# PDB_Mother_v1_1_Sheet.net
KiCad netlist of a schematic drawn in Altium Designer
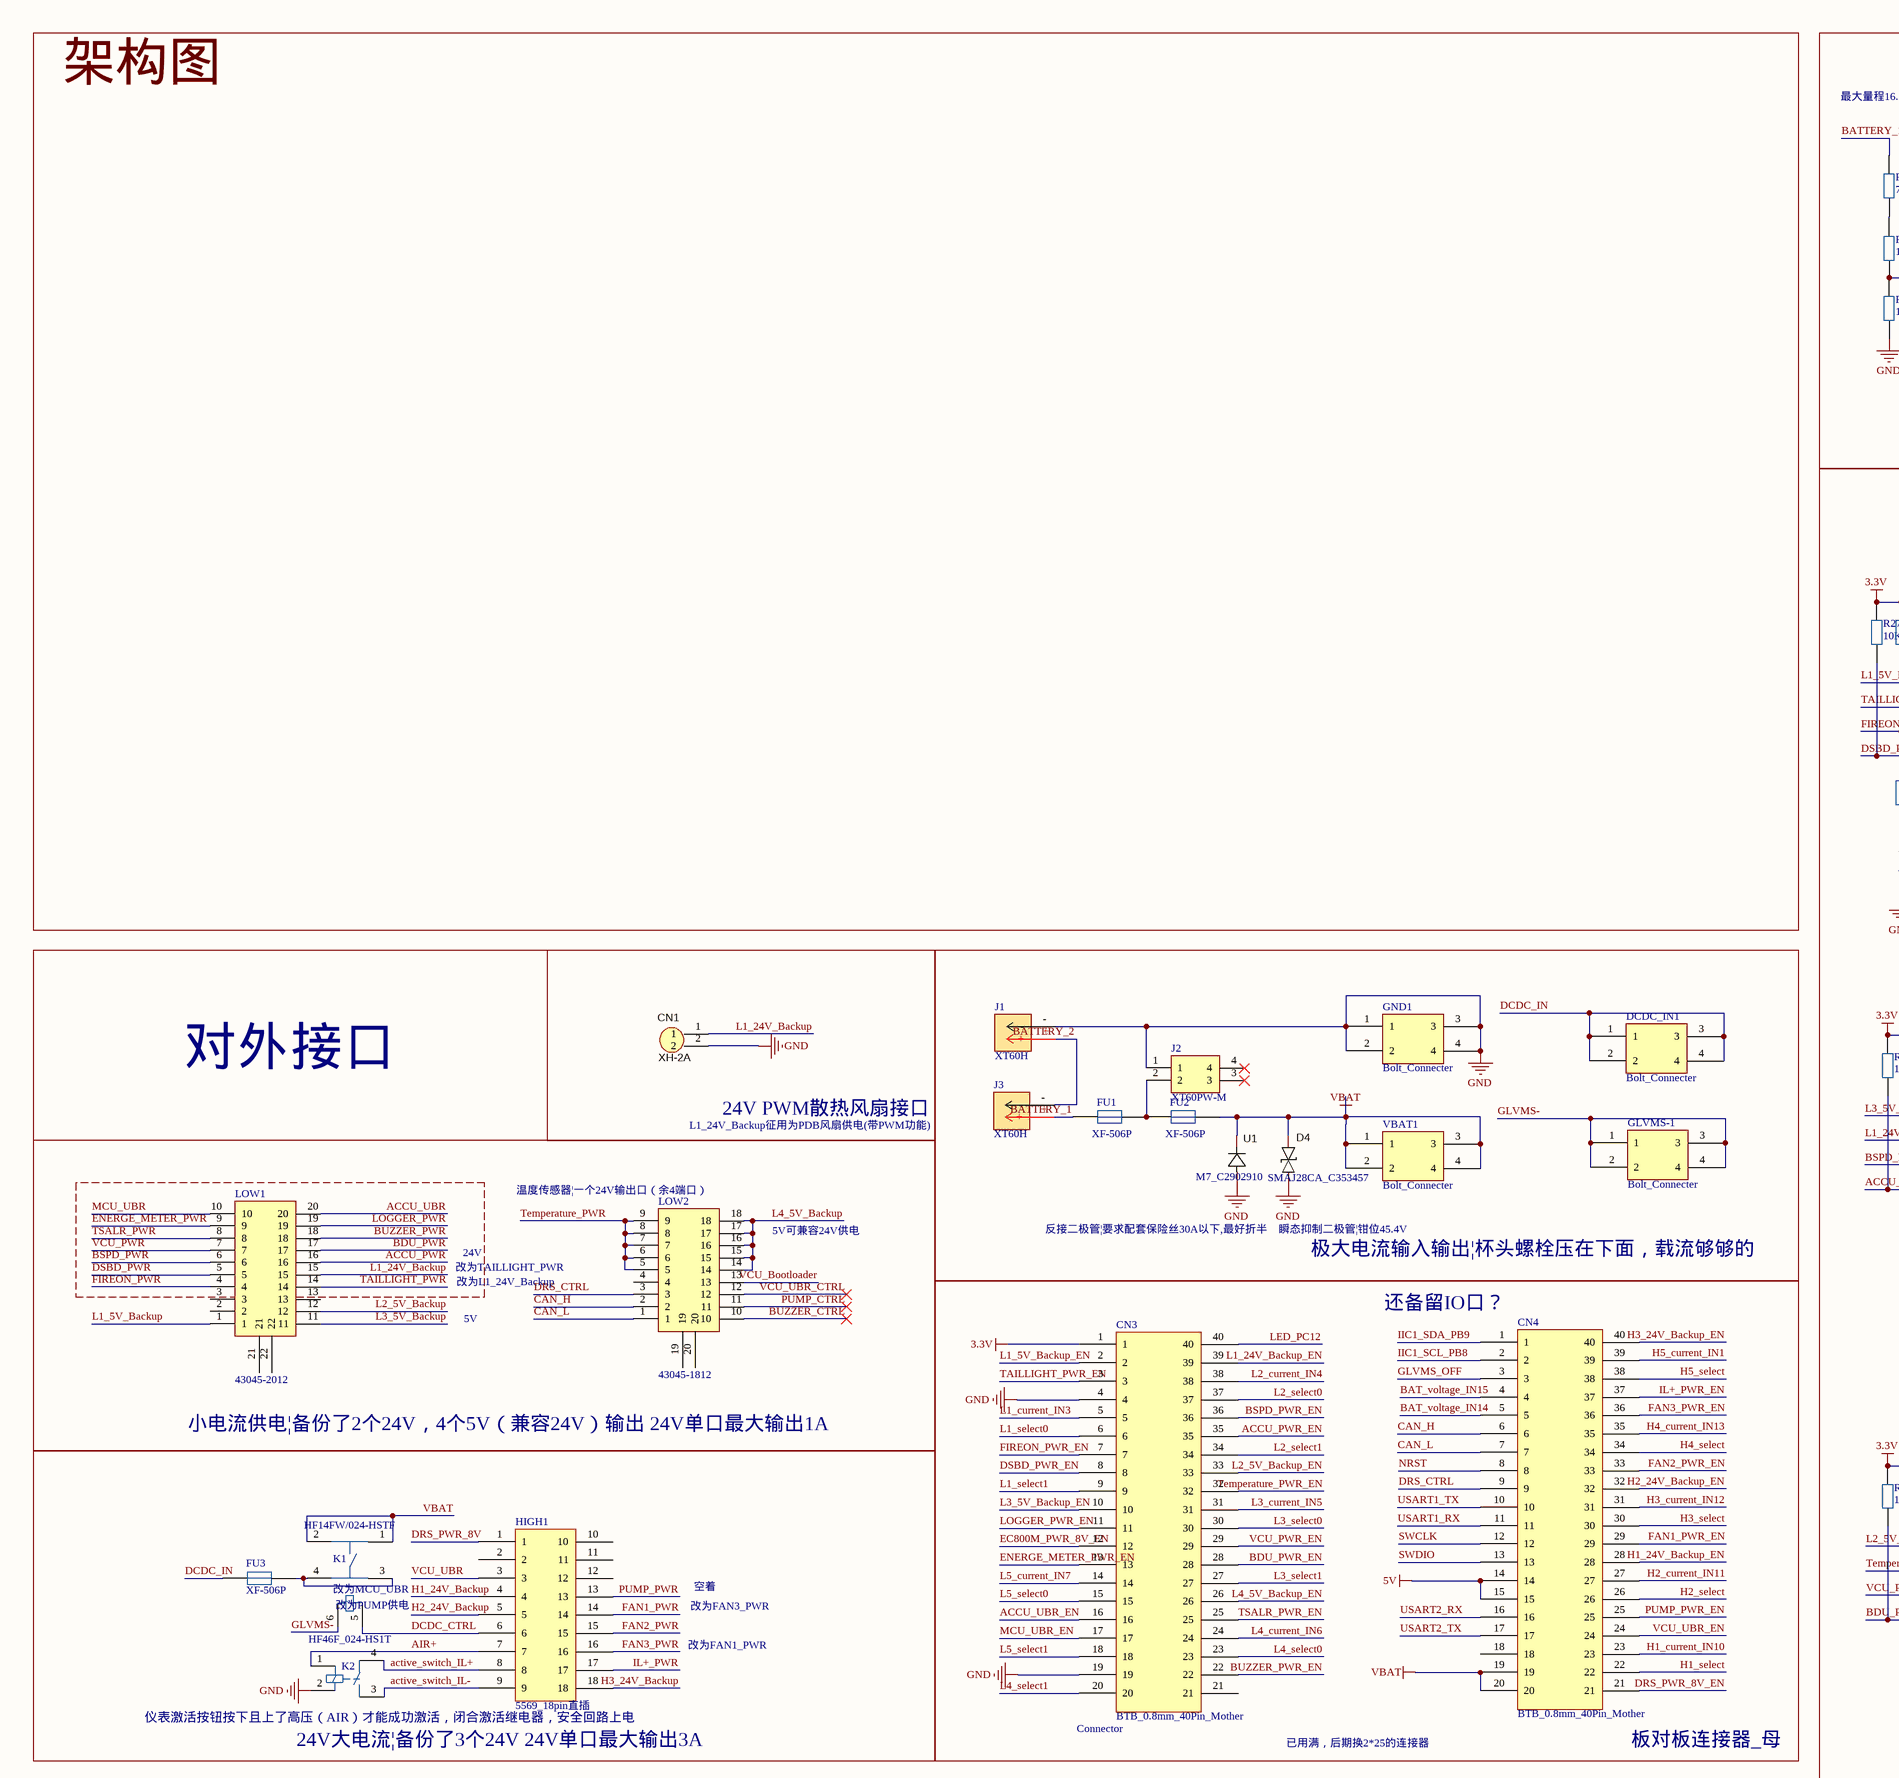
[diagram p0: PDB_Mother_v1.1_Sheet.SchDoc, top left]
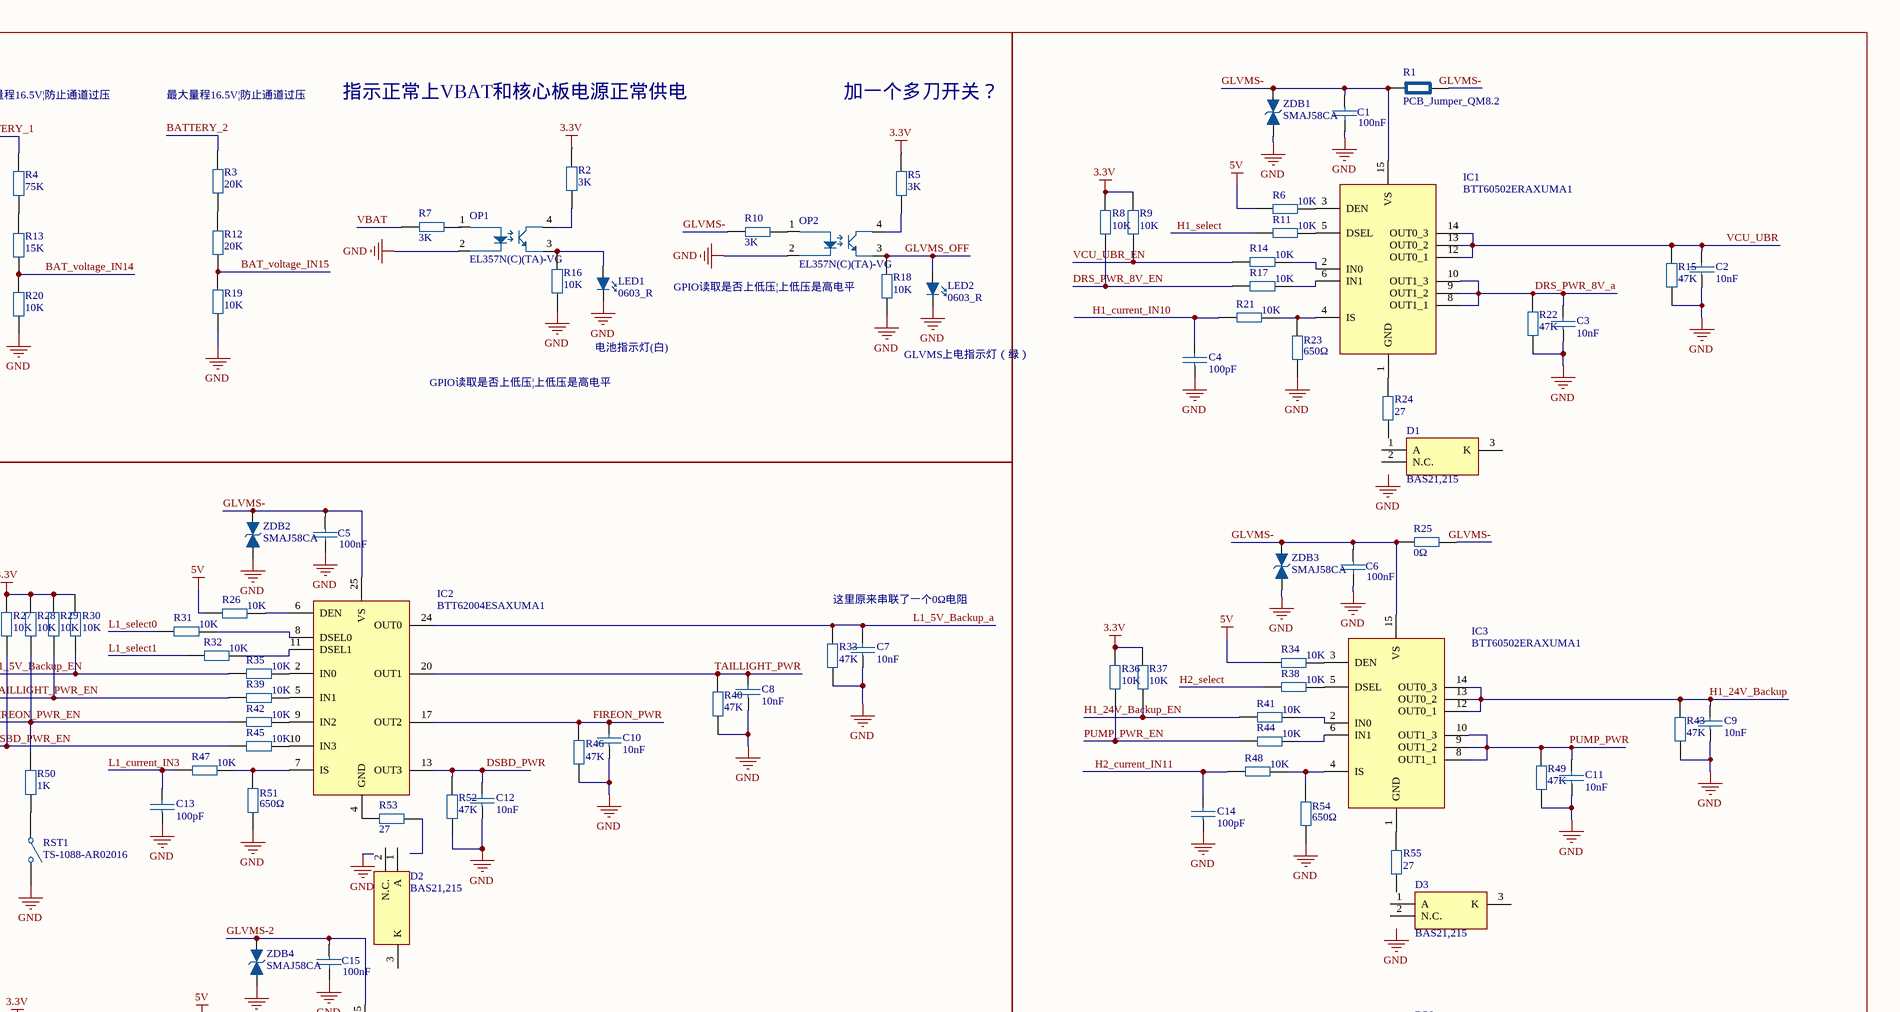
[diagram p1: PDB_Mother_v1.1_Sheet.SchDoc, top right]
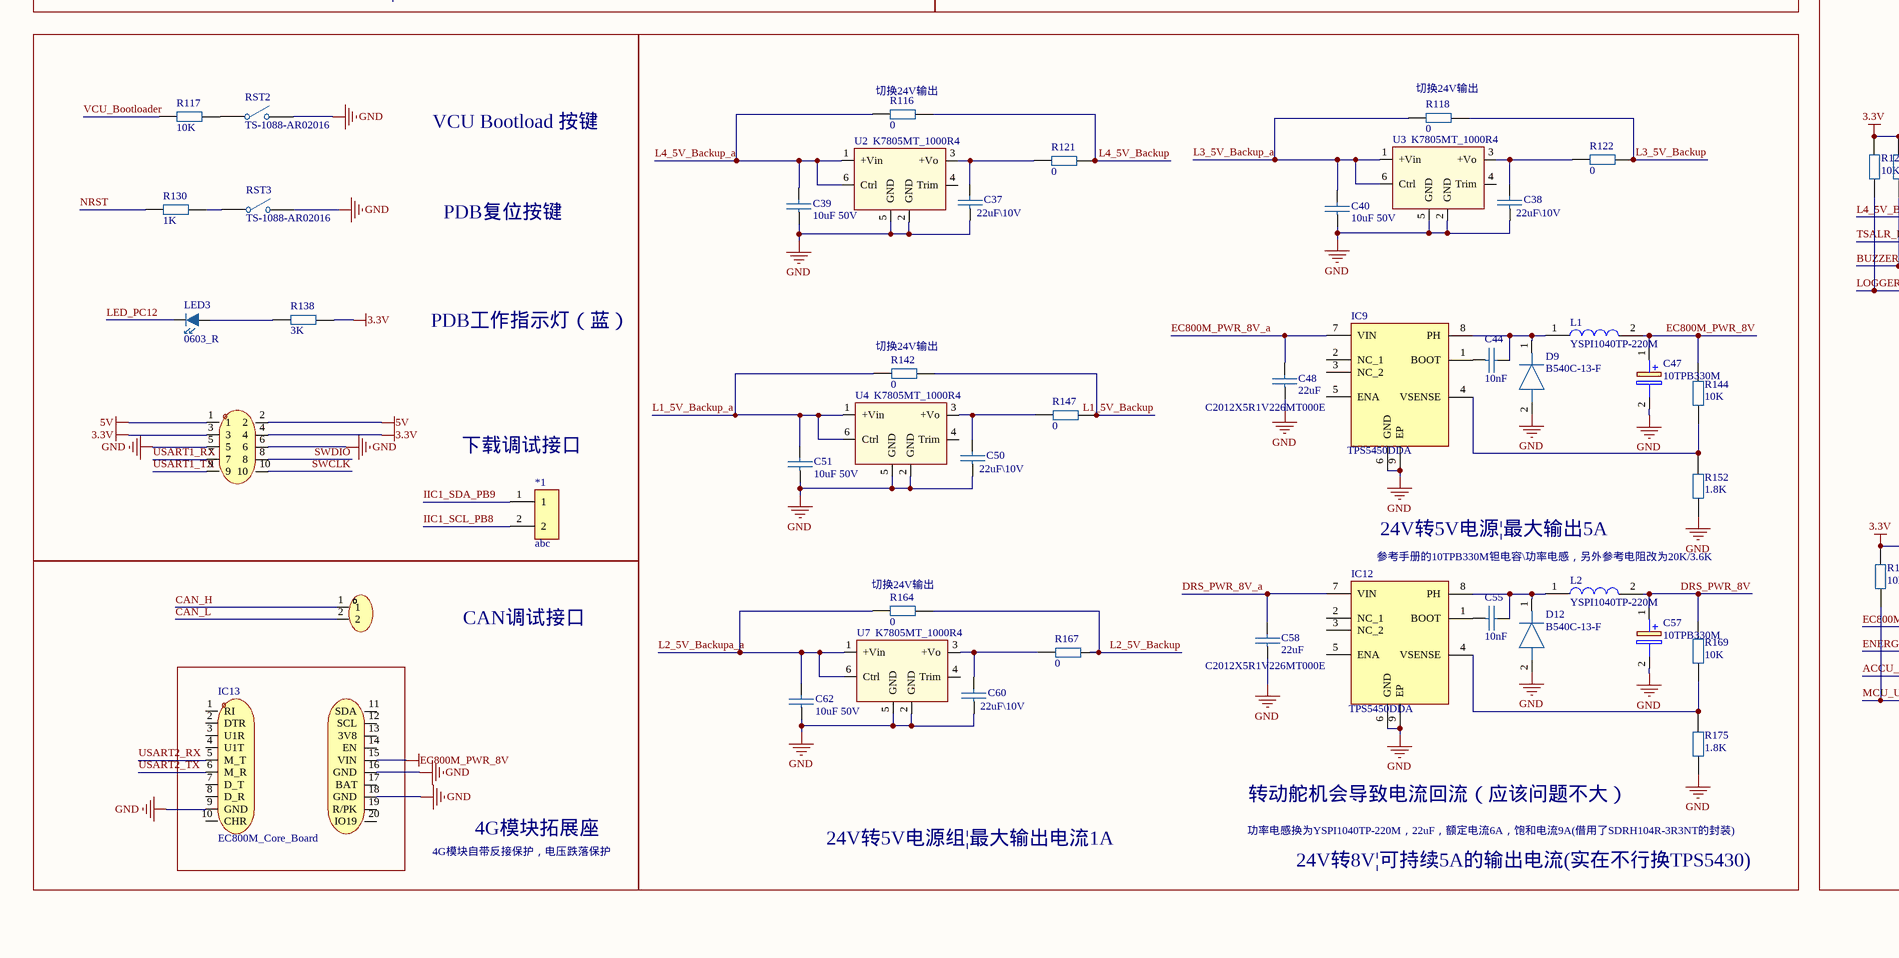
[diagram p2: PDB_Mother_v1.1_Sheet.SchDoc, bottom left]
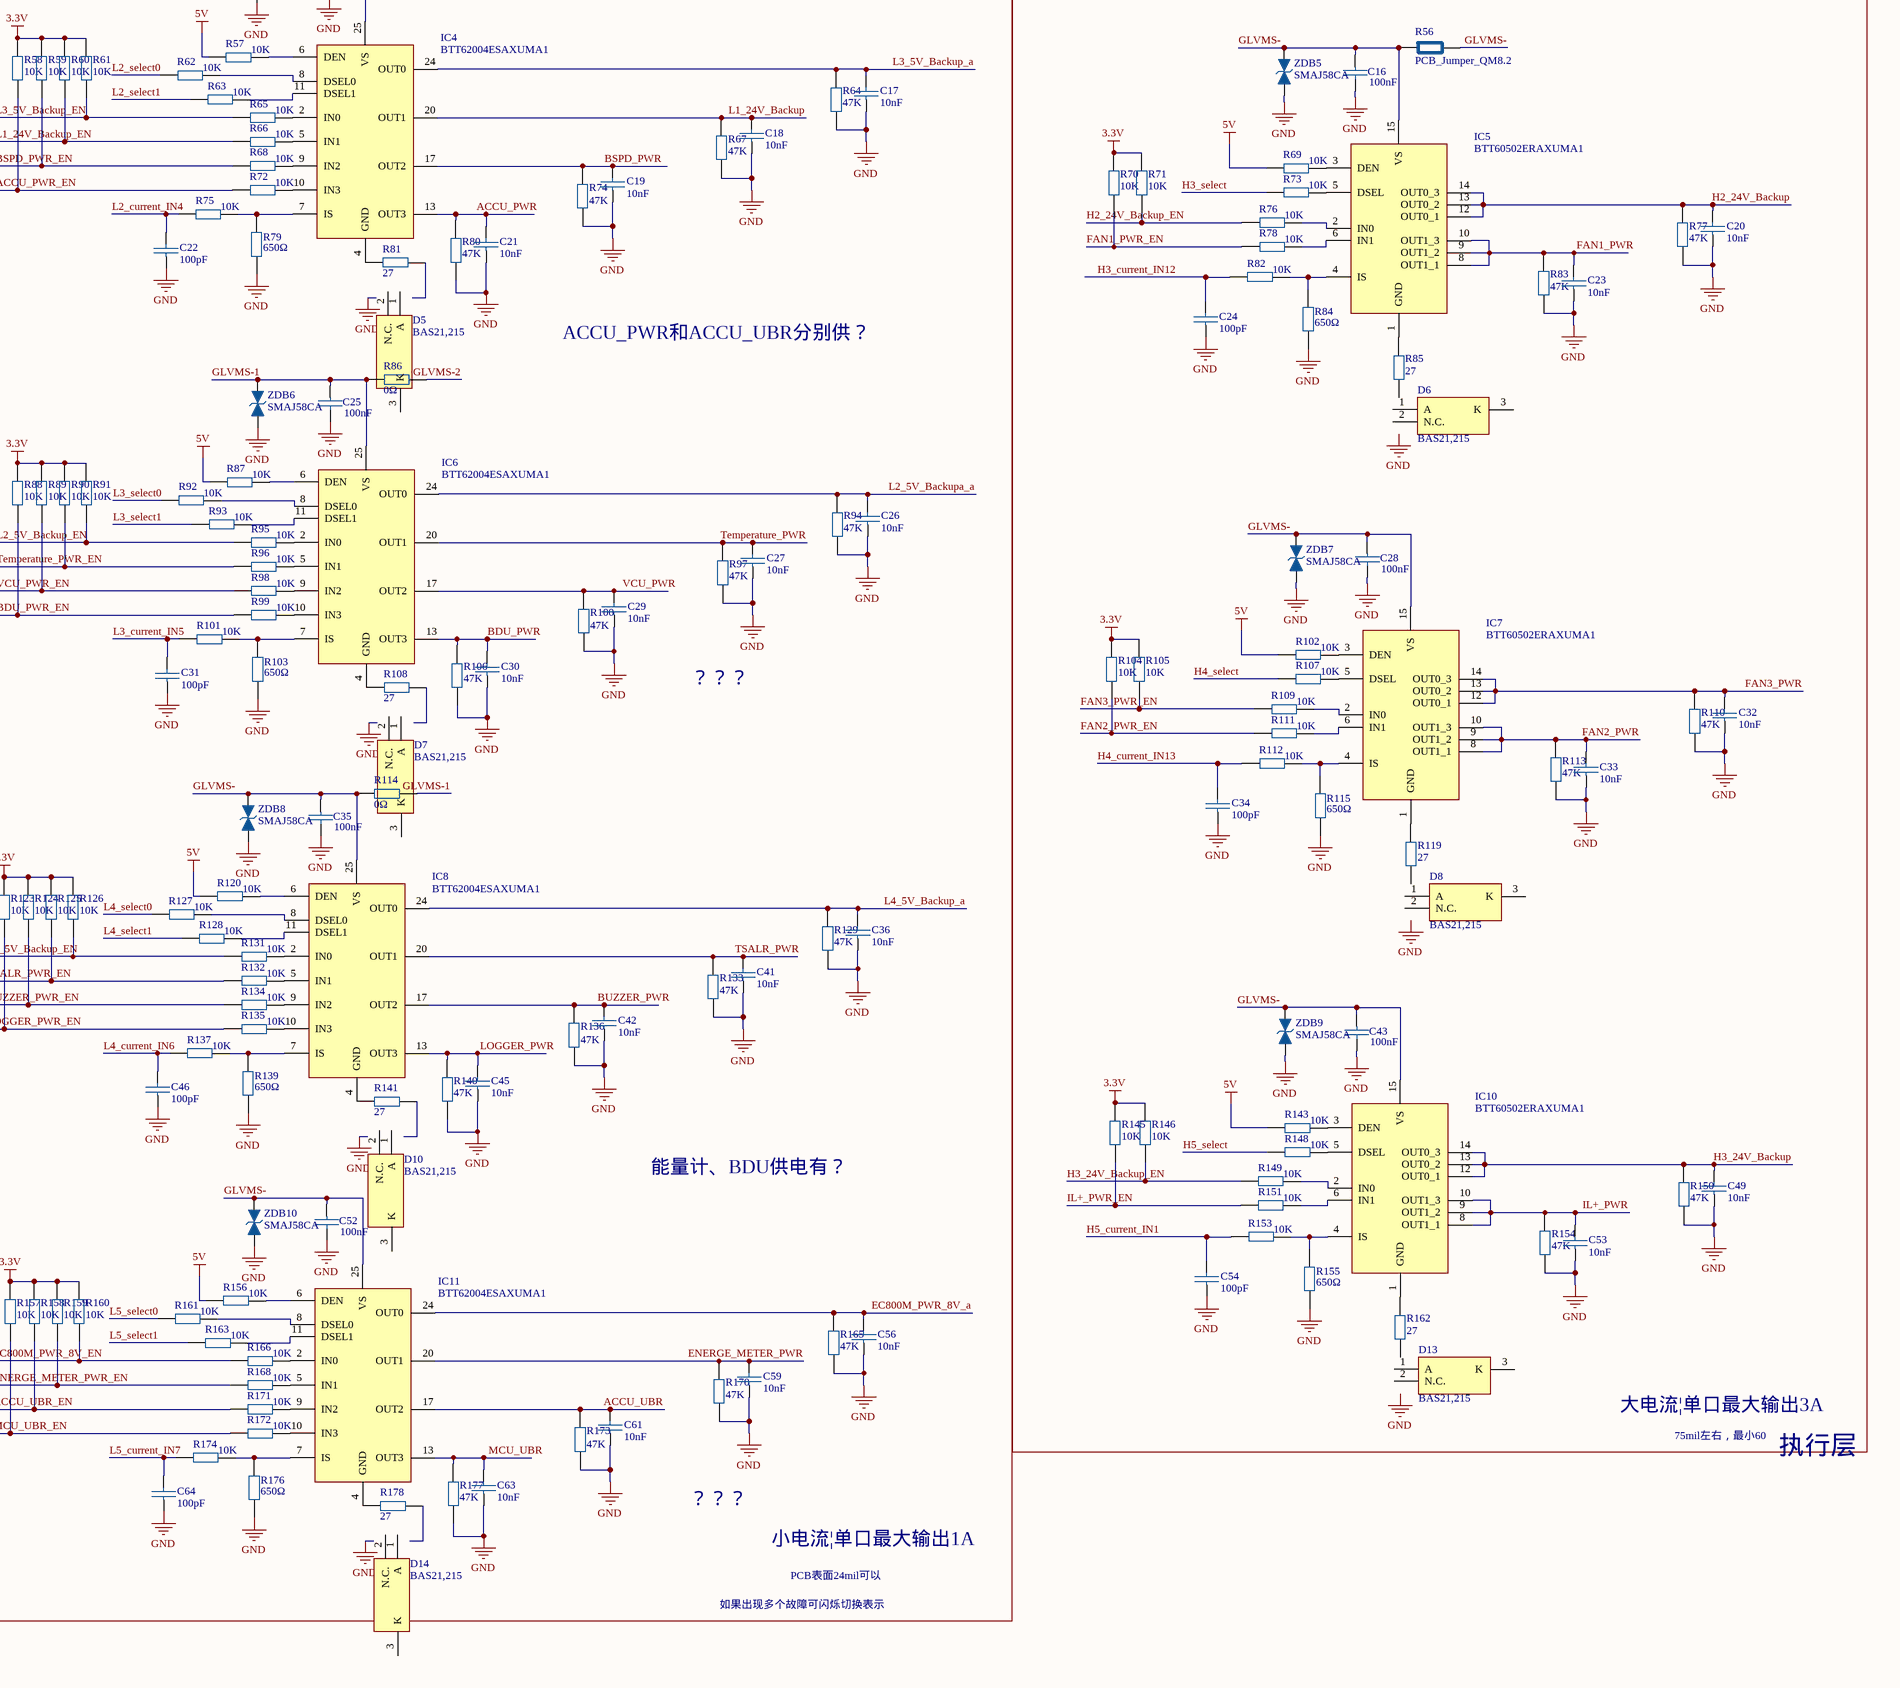
[diagram p3: PDB_Mother_v1.1_Sheet.SchDoc, bottom right]

(export (version "E")
  (design (tool "Eeschema 10.0.6"))
  (components
    (comp (ref "*1") (value "abc") (footprint "abc") (libsource (lib "Connector") (part "abc")))
    (comp (ref "C1")
      (value "100nF")
      (footprint "CAPC1608X08N__0603CAPUNPOLE")
      (description "Std MLCC Cap")
      (libsource (lib "ResistorCapacitorInductor") (part "SMD_MLCC"))
    )
    (comp (ref "C2")
      (value "10nF")
      (footprint "CAPC1608X08N__0603CAPUNPOLE")
      (description "Std MLCC Cap")
      (libsource (lib "ResistorCapacitorInductor") (part "SMD_MLCC"))
    )
    (comp (ref "C3")
      (value "10nF")
      (footprint "CAPC1608X08N__0603CAPUNPOLE")
      (description "Std MLCC Cap")
      (libsource (lib "ResistorCapacitorInductor") (part "SMD_MLCC"))
    )
    (comp (ref "C4")
      (value "100pF")
      (footprint "CAPC1608X08N__0603CAPUNPOLE")
      (description "Std MLCC Cap")
      (libsource (lib "ResistorCapacitorInductor") (part "SMD_MLCC"))
    )
    (comp (ref "C5")
      (value "100nF")
      (footprint "CAPC1608X08N__0603CAPUNPOLE")
      (description "Std MLCC Cap")
      (libsource (lib "ResistorCapacitorInductor") (part "SMD_MLCC"))
    )
    (comp (ref "C6")
      (value "100nF")
      (footprint "CAPC1608X08N__0603CAPUNPOLE")
      (description "Std MLCC Cap")
      (libsource (lib "ResistorCapacitorInductor") (part "SMD_MLCC"))
    )
    (comp (ref "C7")
      (value "10nF")
      (footprint "CAPC1608X08N__0603CAPUNPOLE")
      (description "Std MLCC Cap")
      (libsource (lib "ResistorCapacitorInductor") (part "SMD_MLCC"))
    )
    (comp (ref "C8")
      (value "10nF")
      (footprint "CAPC1608X08N__0603CAPUNPOLE")
      (description "Std MLCC Cap")
      (libsource (lib "ResistorCapacitorInductor") (part "SMD_MLCC"))
    )
    (comp (ref "C9")
      (value "10nF")
      (footprint "CAPC1608X08N__0603CAPUNPOLE")
      (description "Std MLCC Cap")
      (libsource (lib "ResistorCapacitorInductor") (part "SMD_MLCC"))
    )
    (comp (ref "C10")
      (value "10nF")
      (footprint "CAPC1608X08N__0603CAPUNPOLE")
      (description "Std MLCC Cap")
      (libsource (lib "ResistorCapacitorInductor") (part "SMD_MLCC"))
    )
    (comp (ref "C11")
      (value "10nF")
      (footprint "CAPC1608X08N__0603CAPUNPOLE")
      (description "Std MLCC Cap")
      (libsource (lib "ResistorCapacitorInductor") (part "SMD_MLCC"))
    )
    (comp (ref "C12")
      (value "10nF")
      (footprint "CAPC1608X08N__0603CAPUNPOLE")
      (description "Std MLCC Cap")
      (libsource (lib "ResistorCapacitorInductor") (part "SMD_MLCC"))
    )
    (comp (ref "C13")
      (value "100pF")
      (footprint "CAPC1608X08N__0603CAPUNPOLE")
      (description "Std MLCC Cap")
      (libsource (lib "ResistorCapacitorInductor") (part "SMD_MLCC"))
    )
    (comp (ref "C14")
      (value "100pF")
      (footprint "CAPC1608X08N__0603CAPUNPOLE")
      (description "Std MLCC Cap")
      (libsource (lib "ResistorCapacitorInductor") (part "SMD_MLCC"))
    )
    (comp (ref "C15")
      (value "100nF")
      (footprint "CAPC1608X08N__0603CAPUNPOLE")
      (description "Std MLCC Cap")
      (libsource (lib "ResistorCapacitorInductor") (part "SMD_MLCC"))
    )
    (comp (ref "C16")
      (value "100nF")
      (footprint "CAPC1608X08N__0603CAPUNPOLE")
      (description "Std MLCC Cap")
      (libsource (lib "ResistorCapacitorInductor") (part "SMD_MLCC"))
    )
    (comp (ref "C17")
      (value "10nF")
      (footprint "CAPC1608X08N__0603CAPUNPOLE")
      (description "Std MLCC Cap")
      (libsource (lib "ResistorCapacitorInductor") (part "SMD_MLCC"))
    )
    (comp (ref "C18")
      (value "10nF")
      (footprint "CAPC1608X08N__0603CAPUNPOLE")
      (description "Std MLCC Cap")
      (libsource (lib "ResistorCapacitorInductor") (part "SMD_MLCC"))
    )
    (comp (ref "C19")
      (value "10nF")
      (footprint "CAPC1608X08N__0603CAPUNPOLE")
      (description "Std MLCC Cap")
      (libsource (lib "ResistorCapacitorInductor") (part "SMD_MLCC"))
    )
    (comp (ref "C20")
      (value "10nF")
      (footprint "CAPC1608X08N__0603CAPUNPOLE")
      (description "Std MLCC Cap")
      (libsource (lib "ResistorCapacitorInductor") (part "SMD_MLCC"))
    )
    (comp (ref "C21")
      (value "10nF")
      (footprint "CAPC1608X08N__0603CAPUNPOLE")
      (description "Std MLCC Cap")
      (libsource (lib "ResistorCapacitorInductor") (part "SMD_MLCC"))
    )
    (comp (ref "C22")
      (value "100pF")
      (footprint "CAPC1608X08N__0603CAPUNPOLE")
      (description "Std MLCC Cap")
      (libsource (lib "ResistorCapacitorInductor") (part "SMD_MLCC"))
    )
    (comp (ref "C23")
      (value "10nF")
      (footprint "CAPC1608X08N__0603CAPUNPOLE")
      (description "Std MLCC Cap")
      (libsource (lib "ResistorCapacitorInductor") (part "SMD_MLCC"))
    )
    (comp (ref "C24")
      (value "100pF")
      (footprint "CAPC1608X08N__0603CAPUNPOLE")
      (description "Std MLCC Cap")
      (libsource (lib "ResistorCapacitorInductor") (part "SMD_MLCC"))
    )
    (comp (ref "C25")
      (value "100nF")
      (footprint "CAPC1608X08N__0603CAPUNPOLE")
      (description "Std MLCC Cap")
      (libsource (lib "ResistorCapacitorInductor") (part "SMD_MLCC"))
    )
    (comp (ref "C26")
      (value "10nF")
      (footprint "CAPC1608X08N__0603CAPUNPOLE")
      (description "Std MLCC Cap")
      (libsource (lib "ResistorCapacitorInductor") (part "SMD_MLCC"))
    )
    (comp (ref "C27")
      (value "10nF")
      (footprint "CAPC1608X08N__0603CAPUNPOLE")
      (description "Std MLCC Cap")
      (libsource (lib "ResistorCapacitorInductor") (part "SMD_MLCC"))
    )
    (comp (ref "C28")
      (value "100nF")
      (footprint "CAPC1608X08N__0603CAPUNPOLE")
      (description "Std MLCC Cap")
      (libsource (lib "ResistorCapacitorInductor") (part "SMD_MLCC"))
    )
    (comp (ref "C29")
      (value "10nF")
      (footprint "CAPC1608X08N__0603CAPUNPOLE")
      (description "Std MLCC Cap")
      (libsource (lib "ResistorCapacitorInductor") (part "SMD_MLCC"))
    )
    (comp (ref "C30")
      (value "10nF")
      (footprint "CAPC1608X08N__0603CAPUNPOLE")
      (description "Std MLCC Cap")
      (libsource (lib "ResistorCapacitorInductor") (part "SMD_MLCC"))
    )
    (comp (ref "C31")
      (value "100pF")
      (footprint "CAPC1608X08N__0603CAPUNPOLE")
      (description "Std MLCC Cap")
      (libsource (lib "ResistorCapacitorInductor") (part "SMD_MLCC"))
    )
    (comp (ref "C32")
      (value "10nF")
      (footprint "CAPC1608X08N__0603CAPUNPOLE")
      (description "Std MLCC Cap")
      (libsource (lib "ResistorCapacitorInductor") (part "SMD_MLCC"))
    )
    (comp (ref "C33")
      (value "10nF")
      (footprint "CAPC1608X08N__0603CAPUNPOLE")
      (description "Std MLCC Cap")
      (libsource (lib "ResistorCapacitorInductor") (part "SMD_MLCC"))
    )
    (comp (ref "C34")
      (value "100pF")
      (footprint "CAPC1608X08N__0603CAPUNPOLE")
      (description "Std MLCC Cap")
      (libsource (lib "ResistorCapacitorInductor") (part "SMD_MLCC"))
    )
    (comp (ref "C35")
      (value "100nF")
      (footprint "CAPC1608X08N__0603CAPUNPOLE")
      (description "Std MLCC Cap")
      (libsource (lib "ResistorCapacitorInductor") (part "SMD_MLCC"))
    )
    (comp (ref "C36")
      (value "10nF")
      (footprint "CAPC1608X08N__0603CAPUNPOLE")
      (description "Std MLCC Cap")
      (libsource (lib "ResistorCapacitorInductor") (part "SMD_MLCC"))
    )
    (comp (ref "C37")
      (value "22u~{F}10V")
      (footprint "CAPC1608X08N__0603CAPUNPOLE")
      (description "Std MLCC Cap")
      (libsource (lib "ResistorCapacitorInductor") (part "SMD_MLCC"))
    )
    (comp (ref "C38")
      (value "22u~{F}10V")
      (footprint "CAPC1608X08N__0603CAPUNPOLE")
      (description "Std MLCC Cap")
      (libsource (lib "ResistorCapacitorInductor") (part "SMD_MLCC"))
    )
    (comp (ref "C39")
      (value "10uF 50V")
      (footprint "CAPC3216X16N_1206CAPUNPOLE")
      (description "Std MLCC Cap")
      (libsource (lib "ResistorCapacitorInductor") (part "SMD_MLCC"))
    )
    (comp (ref "C40")
      (value "10uF 50V")
      (footprint "CAPC3216X16N_1206CAPUNPOLE")
      (description "Std MLCC Cap")
      (libsource (lib "ResistorCapacitorInductor") (part "SMD_MLCC"))
    )
    (comp (ref "C41")
      (value "10nF")
      (footprint "CAPC1608X08N__0603CAPUNPOLE")
      (description "Std MLCC Cap")
      (libsource (lib "ResistorCapacitorInductor") (part "SMD_MLCC"))
    )
    (comp (ref "C42")
      (value "10nF")
      (footprint "CAPC1608X08N__0603CAPUNPOLE")
      (description "Std MLCC Cap")
      (libsource (lib "ResistorCapacitorInductor") (part "SMD_MLCC"))
    )
    (comp (ref "C43")
      (value "100nF")
      (footprint "CAPC1608X08N__0603CAPUNPOLE")
      (description "Std MLCC Cap")
      (libsource (lib "ResistorCapacitorInductor") (part "SMD_MLCC"))
    )
    (comp (ref "C44")
      (value "10nF")
      (footprint "CAPC1608X08N__0603CAPUNPOLE")
      (description "Std MLCC Cap")
      (libsource (lib "ResistorCapacitorInductor") (part "SMD_MLCC"))
    )
    (comp (ref "C45")
      (value "10nF")
      (footprint "CAPC1608X08N__0603CAPUNPOLE")
      (description "Std MLCC Cap")
      (libsource (lib "ResistorCapacitorInductor") (part "SMD_MLCC"))
    )
    (comp (ref "C46")
      (value "100pF")
      (footprint "CAPC1608X08N__0603CAPUNPOLE")
      (description "Std MLCC Cap")
      (libsource (lib "ResistorCapacitorInductor") (part "SMD_MLCC"))
    )
    (comp (ref "C47")
      (value "10TPB330M")
      (footprint "POSCAP_D12_D15_D15E_D2E_D2_D3L_D4")
      (description "Capacitor Polarised")
      (fields (field (name "MOUSER PART NUMBER") "667-10TPB330M"))
      (libsource (lib "Resistor^Capacitor^Inductor") (part "10TPB330M"))
    )
    (comp (ref "C48")
      (value "22uF")
      (footprint "CAPC2012X06N__0805CAPUNPOLE")
      (description "Std MLCC Cap")
      (libsource (lib "ResistorCapacitorInductor") (part "SMD_MLCC"))
    )
    (comp (ref "C49")
      (value "10nF")
      (footprint "CAPC1608X08N__0603CAPUNPOLE")
      (description "Std MLCC Cap")
      (libsource (lib "ResistorCapacitorInductor") (part "SMD_MLCC"))
    )
    (comp (ref "C50")
      (value "22u~{F}10V")
      (footprint "CAPC1608X08N__0603CAPUNPOLE")
      (description "Std MLCC Cap")
      (libsource (lib "ResistorCapacitorInductor") (part "SMD_MLCC"))
    )
    (comp (ref "C51")
      (value "10uF 50V")
      (footprint "CAPC3216X16N_1206CAPUNPOLE")
      (description "Std MLCC Cap")
      (libsource (lib "ResistorCapacitorInductor") (part "SMD_MLCC"))
    )
    (comp (ref "C52")
      (value "100nF")
      (footprint "CAPC1608X08N__0603CAPUNPOLE")
      (description "Std MLCC Cap")
      (libsource (lib "ResistorCapacitorInductor") (part "SMD_MLCC"))
    )
    (comp (ref "C53")
      (value "10nF")
      (footprint "CAPC1608X08N__0603CAPUNPOLE")
      (description "Std MLCC Cap")
      (libsource (lib "ResistorCapacitorInductor") (part "SMD_MLCC"))
    )
    (comp (ref "C54")
      (value "100pF")
      (footprint "CAPC1608X08N__0603CAPUNPOLE")
      (description "Std MLCC Cap")
      (libsource (lib "ResistorCapacitorInductor") (part "SMD_MLCC"))
    )
    (comp (ref "C55")
      (value "10nF")
      (footprint "CAPC1608X08N__0603CAPUNPOLE")
      (description "Std MLCC Cap")
      (libsource (lib "ResistorCapacitorInductor") (part "SMD_MLCC"))
    )
    (comp (ref "C56")
      (value "10nF")
      (footprint "CAPC1608X08N__0603CAPUNPOLE")
      (description "Std MLCC Cap")
      (libsource (lib "ResistorCapacitorInductor") (part "SMD_MLCC"))
    )
    (comp (ref "C57")
      (value "10TPB330M")
      (footprint "POSCAP_D12_D15_D15E_D2E_D2_D3L_D4")
      (description "Capacitor Polarised")
      (fields (field (name "MOUSER PART NUMBER") "667-10TPB330M"))
      (libsource (lib "Resistor^Capacitor^Inductor") (part "10TPB330M"))
    )
    (comp (ref "C58")
      (value "22uF")
      (footprint "CAPC2012X06N__0805CAPUNPOLE")
      (description "Std MLCC Cap")
      (libsource (lib "ResistorCapacitorInductor") (part "SMD_MLCC"))
    )
    (comp (ref "C59")
      (value "10nF")
      (footprint "CAPC1608X08N__0603CAPUNPOLE")
      (description "Std MLCC Cap")
      (libsource (lib "ResistorCapacitorInductor") (part "SMD_MLCC"))
    )
    (comp (ref "C60")
      (value "22u~{F}10V")
      (footprint "CAPC1608X08N__0603CAPUNPOLE")
      (description "Std MLCC Cap")
      (libsource (lib "ResistorCapacitorInductor") (part "SMD_MLCC"))
    )
    (comp (ref "C61")
      (value "10nF")
      (footprint "CAPC1608X08N__0603CAPUNPOLE")
      (description "Std MLCC Cap")
      (libsource (lib "ResistorCapacitorInductor") (part "SMD_MLCC"))
    )
    (comp (ref "C62")
      (value "10uF 50V")
      (footprint "CAPC3216X16N_1206CAPUNPOLE")
      (description "Std MLCC Cap")
      (libsource (lib "ResistorCapacitorInductor") (part "SMD_MLCC"))
    )
    (comp (ref "C63")
      (value "10nF")
      (footprint "CAPC1608X08N__0603CAPUNPOLE")
      (description "Std MLCC Cap")
      (libsource (lib "ResistorCapacitorInductor") (part "SMD_MLCC"))
    )
    (comp (ref "C64")
      (value "100pF")
      (footprint "CAPC1608X08N__0603CAPUNPOLE")
      (description "Std MLCC Cap")
      (libsource (lib "ResistorCapacitorInductor") (part "SMD_MLCC"))
    )
    (comp (ref "CN1")
      (value "XH-2A")
      (footprint "CONN-TH_XH-2A")
      (fields (field (name "MANUFACTURER") "BOOMELE(博穆精密)"))
      (libsource (lib "Connector") (part "XH-2A_C20079"))
    )
    (comp (ref "CN3")
      (value "BTB_0.8mm_40Pin_Mother")
      (footprint "BTB_0.8mm_40PIN_M")
      (fields (field (name "SYSTEM") "Connector"))
      (libsource (lib "Connector") (part "BTB_0.8mm_40Pin_Mother"))
    )
    (comp (ref "CN4")
      (value "BTB_0.8mm_40Pin_Mother")
      (footprint "BTB_0.8mm_40PIN_M")
      (libsource (lib "Connector") (part "BTB_0.8mm_40Pin_Mother"))
    )
    (comp (ref "D1")
      (value "BAS21,215")
      (footprint "BAS21215")
      (description "Diode")
      (fields (field (name "MOUSER PART NUMBER") "771-BAS21-T/R"))
      (libsource (lib "") (part "BAS21,215_1"))
    )
    (comp (ref "D2")
      (value "BAS21,215")
      (footprint "BAS21215")
      (description "Diode")
      (fields (field (name "MOUSER PART NUMBER") "771-BAS21-T/R"))
      (libsource (lib "Diodes") (part "BAS21,215"))
    )
    (comp (ref "D3")
      (value "BAS21,215")
      (footprint "BAS21215")
      (description "Diode")
      (fields (field (name "MOUSER PART NUMBER") "771-BAS21-T/R"))
      (libsource (lib "") (part "BAS21,215_1"))
    )
    (comp (ref "D4")
      (value "SMAJ28CA_C353457")
      (footprint "SMA_L4.3-W2.5-LS5.0-BI")
      (description "C353457")
      (fields (field (name "MANUFACTURER") "晶导微电子") (field (name "MANUFACTURER PART") "SMAJ28CA"))
      (libsource (lib "Diodes") (part "SMAJ28CA_C353457"))
    )
    (comp (ref "D5")
      (value "BAS21,215")
      (footprint "BAS21215")
      (description "Diode")
      (fields (field (name "MOUSER PART NUMBER") "771-BAS21-T/R"))
      (libsource (lib "Diodes") (part "BAS21,215"))
    )
    (comp (ref "D6")
      (value "BAS21,215")
      (footprint "BAS21215")
      (description "Diode")
      (fields (field (name "MOUSER PART NUMBER") "771-BAS21-T/R"))
      (libsource (lib "") (part "BAS21,215_1"))
    )
    (comp (ref "D7")
      (value "BAS21,215")
      (footprint "BAS21215")
      (description "Diode")
      (fields (field (name "MOUSER PART NUMBER") "771-BAS21-T/R"))
      (libsource (lib "Diodes") (part "BAS21,215"))
    )
    (comp (ref "D8")
      (value "BAS21,215")
      (footprint "BAS21215")
      (description "Diode")
      (fields (field (name "MOUSER PART NUMBER") "771-BAS21-T/R"))
      (libsource (lib "") (part "BAS21,215_1"))
    )
    (comp (ref "D9")
      (value "B540C-13-F")
      (footprint "DIOM7959X250N")
      (description "Diode")
      (fields (field (name "MOUSER PART NUMBER") "621-B540C-F"))
      (libsource (lib "Diodes") (part "B540C-13-F"))
    )
    (comp (ref "D10")
      (value "BAS21,215")
      (footprint "BAS21215")
      (description "Diode")
      (fields (field (name "MOUSER PART NUMBER") "771-BAS21-T/R"))
      (libsource (lib "Diodes") (part "BAS21,215"))
    )
    (comp (ref "D12")
      (value "B540C-13-F")
      (footprint "DIOM7959X250N")
      (description "Diode")
      (fields (field (name "MOUSER PART NUMBER") "621-B540C-F"))
      (libsource (lib "Diodes") (part "B540C-13-F"))
    )
    (comp (ref "D13")
      (value "BAS21,215")
      (footprint "BAS21215")
      (description "Diode")
      (fields (field (name "MOUSER PART NUMBER") "771-BAS21-T/R"))
      (libsource (lib "") (part "BAS21,215_1"))
    )
    (comp (ref "D14")
      (value "BAS21,215")
      (footprint "BAS21215")
      (description "Diode")
      (fields (field (name "MOUSER PART NUMBER") "771-BAS21-T/R"))
      (libsource (lib "Diodes") (part "BAS21,215"))
    )
    (comp (ref "DCDC_IN1")
      (value "Bolt_Connecter")
      (footprint "Bolt_Connecter")
      (libsource (lib "Connector") (part "Bolt_Connecter"))
    )
    (comp (ref "FU1")
      (value "XF-506P")
      (footprint "XF-506P")
      (description "小型汽车插片保险丝座")
      (libsource (lib "ResistorCapacitorInductor") (part "XF-506P"))
    )
    (comp (ref "FU2")
      (value "XF-506P")
      (footprint "XF-506P")
      (description "小型汽车插片保险丝座")
      (libsource (lib "ResistorCapacitorInductor") (part "XF-506P"))
    )
    (comp (ref "FU3")
      (value "XF-506P")
      (footprint "XF-506P")
      (description "小型汽车插片保险丝座")
      (libsource (lib "ResistorCapacitorInductor") (part "XF-506P"))
    )
    (comp (ref "GLVMS-1")
      (value "Bolt_Connecter")
      (footprint "Bolt_Connecter")
      (libsource (lib "Connector") (part "Bolt_Connecter"))
    )
    (comp (ref "GND1")
      (value "Bolt_Connecter")
      (footprint "Bolt_Connecter")
      (libsource (lib "Connector") (part "Bolt_Connecter"))
    )
    (comp (ref "HIGH1")
      (value "5569_18pin直插")
      (footprint "5569_18Pin")
      (libsource (lib "Connector") (part "5569_18pin直插"))
    )
    (comp (ref "IC1")
      (value "BTT60502ERAXUMA1")
      (footprint "PG-TDSO-14")
      (description "Integrated Circuit")
      (fields (field (name "MOUSER PART NUMBER") "726-BTT60502ERAXUMA1"))
      (libsource (lib "GateDrivers") (part "BTT60502ERAXUMA1"))
    )
    (comp (ref "IC2")
      (value "BTT62004ESAXUMA1")
      (footprint "PG-TSDSO-24")
      (description "Integrated Circuit")
      (fields (field (name "MOUSER PART NUMBER") "726-BTT62004ESAXUMA1"))
      (libsource (lib "GateDrivers") (part "BTT62004ESAXUMA1"))
    )
    (comp (ref "IC3")
      (value "BTT60502ERAXUMA1")
      (footprint "PG-TDSO-14")
      (description "Integrated Circuit")
      (fields (field (name "MOUSER PART NUMBER") "726-BTT60502ERAXUMA1"))
      (libsource (lib "GateDrivers") (part "BTT60502ERAXUMA1"))
    )
    (comp (ref "IC4")
      (value "BTT62004ESAXUMA1")
      (footprint "PG-TSDSO-24")
      (description "Integrated Circuit")
      (fields (field (name "MOUSER PART NUMBER") "726-BTT62004ESAXUMA1"))
      (libsource (lib "GateDrivers") (part "BTT62004ESAXUMA1"))
    )
    (comp (ref "IC5")
      (value "BTT60502ERAXUMA1")
      (footprint "PG-TDSO-14")
      (description "Integrated Circuit")
      (fields (field (name "MOUSER PART NUMBER") "726-BTT60502ERAXUMA1"))
      (libsource (lib "GateDrivers") (part "BTT60502ERAXUMA1"))
    )
    (comp (ref "IC6")
      (value "BTT62004ESAXUMA1")
      (footprint "PG-TSDSO-24")
      (description "Integrated Circuit")
      (fields (field (name "MOUSER PART NUMBER") "726-BTT62004ESAXUMA1"))
      (libsource (lib "GateDrivers") (part "BTT62004ESAXUMA1"))
    )
    (comp (ref "IC7")
      (value "BTT60502ERAXUMA1")
      (footprint "PG-TDSO-14")
      (description "Integrated Circuit")
      (fields (field (name "MOUSER PART NUMBER") "726-BTT60502ERAXUMA1"))
      (libsource (lib "GateDrivers") (part "BTT60502ERAXUMA1"))
    )
    (comp (ref "IC8")
      (value "BTT62004ESAXUMA1")
      (footprint "PG-TSDSO-24")
      (description "Integrated Circuit")
      (fields (field (name "MOUSER PART NUMBER") "726-BTT62004ESAXUMA1"))
      (libsource (lib "GateDrivers") (part "BTT62004ESAXUMA1"))
    )
    (comp (ref "IC9")
      (value "TPS5450DDA")
      (footprint "SOIC127P600X170-9N")
      (description "Integrated Circuit")
      (fields (field (name "MOUSER PART NUMBER") "595-TPS5450DDA"))
      (libsource (lib "DCDC_LDO") (part "TPS5450DDA"))
    )
    (comp (ref "IC10")
      (value "BTT60502ERAXUMA1")
      (footprint "PG-TDSO-14")
      (description "Integrated Circuit")
      (fields (field (name "MOUSER PART NUMBER") "726-BTT60502ERAXUMA1"))
      (libsource (lib "GateDrivers") (part "BTT60502ERAXUMA1"))
    )
    (comp (ref "IC11")
      (value "BTT62004ESAXUMA1")
      (footprint "PG-TSDSO-24")
      (description "Integrated Circuit")
      (fields (field (name "MOUSER PART NUMBER") "726-BTT62004ESAXUMA1"))
      (libsource (lib "GateDrivers") (part "BTT62004ESAXUMA1"))
    )
    (comp (ref "IC12")
      (value "TPS5450DDA")
      (footprint "SOIC127P600X170-9N")
      (description "Integrated Circuit")
      (fields (field (name "MOUSER PART NUMBER") "595-TPS5450DDA"))
      (libsource (lib "DCDC_LDO") (part "TPS5450DDA"))
    )
    (comp (ref "IC13")
      (value "EC800M_Core_Board")
      (footprint "EC800M_Core_Board")
      (libsource (lib "MCU") (part "EC800M_Core_Board"))
    )
    (comp (ref "J1")
      (value "XT60H")
      (footprint "AMASS_XT60_NOMAL")
      (libsource (lib "Connector") (part "AmassXTxx_Connector"))
    )
    (comp (ref "J2")
      (value "XT60PW-M")
      (footprint "XT60PWM")
      (description "Connector")
      (libsource (lib "Connector") (part "XT60PW-M"))
    )
    (comp (ref "J3")
      (value "XT60H")
      (footprint "AMASS_XT60_NOMAL")
      (libsource (lib "Connector") (part "AmassXTxx_Connector"))
    )
    (comp (ref "K1")
      (value "HF14FW/024-HSTF")
      (footprint "HF14FW005HPTF")
      (description "Relay or Contactor")
      (libsource (lib "Relay") (part "HF14FW/024-HSTF"))
    )
    (comp (ref "K2")
      (value "HF46F_024-HS1T")
      (footprint "HF46F024HS1T")
      (description "Relay or Contactor")
      (fields (field (name "MANUFACTURER_PART_NUMBER") "HF46F/024-HS1T"))
      (libsource (lib "Relay") (part "HF46F_024-HS1T"))
    )
    (comp (ref "L1")
      (value "YSPI1040TP-220M")
      (footprint "SamacSys:SDRH104R3R3NT")
      (description "Inductor")
      (fields (field (name "MANUFACTURER_PART_NUMBER") "SDRH104R-3R3NT"))
      (libsource (lib "*") (part "SDRH104R-3R3NT"))
    )
    (comp (ref "L2")
      (value "YSPI1040TP-220M")
      (footprint "SamacSys:SDRH104R3R3NT")
      (description "Inductor")
      (fields (field (name "MANUFACTURER_PART_NUMBER") "SDRH104R-3R3NT"))
      (libsource (lib "*") (part "SDRH104R-3R3NT"))
    )
    (comp (ref "LED1")
      (value "0603_R")
      (footprint "LED0603-RD_RED")
      (description "Light Emitting Diode")
      (libsource (lib "Diodes") (part "LED"))
    )
    (comp (ref "LED2")
      (value "0603_R")
      (footprint "LED0603-RD_RED")
      (description "Light Emitting Diode")
      (libsource (lib "Diodes") (part "LED"))
    )
    (comp (ref "LED3")
      (value "0603_R")
      (footprint "LED0603-RD_RED")
      (description "Light Emitting Diode")
      (libsource (lib "Diodes") (part "LED"))
    )
    (comp (ref "LOW1")
      (value "43045-2012")
      (footprint "Connector:43045-20YY_121314")
      (description "Connector")
      (fields (field (name "MOUSER PART NUMBER") "538-43045-2012"))
      (libsource (lib "Connector") (part "43045-2012"))
    )
    (comp (ref "LOW2")
      (value "43045-1812")
      (footprint "43045-18YY_121314")
      (description "Connector")
      (fields (field (name "MOUSER PART NUMBER") "538-43045-1812"))
      (libsource (lib "Connector") (part "43045-1812"))
    )
    (comp (ref "OP1")
      (value "EL357N(C)(TA)-VG")
      (footprint "SOP-4-2.54mm")
      (description "No Description Available\r\n立创编号：C108648")
      (libsource (lib "Relay") (part "EL357N(C)(TA)-VG"))
    )
    (comp (ref "OP2")
      (value "EL357N(C)(TA)-VG")
      (footprint "SOP-4-2.54mm")
      (description "No Description Available\r\n立创编号：C108648")
      (libsource (lib "Relay") (part "EL357N(C)(TA)-VG"))
    )
    (comp (ref "R1")
      (value "PCB_Jumper_QM8.2")
      (footprint "PCB_Jumper")
      (libsource (lib "ResistorCapacitorInductor") (part "PCB_Jumper_QM8.2"))
    )
    (comp (ref "R2")
      (value "3K")
      (footprint "RESC3116X06N__1206RES")
      (description "Std Resistor")
      (libsource (lib "ResistorCapacitorInductor") (part "SMD_Resistor"))
    )
    (comp (ref "R3")
      (value "20K")
      (footprint "RESC1608X04N_0603RES")
      (description "Std Resistor")
      (libsource (lib "ResistorCapacitorInductor") (part "SMD_Resistor"))
    )
    (comp (ref "R4")
      (value "75K")
      (footprint "RESC1608X04N_0603RES")
      (description "Std Resistor")
      (libsource (lib "ResistorCapacitorInductor") (part "SMD_Resistor"))
    )
    (comp (ref "R5")
      (value "3K")
      (footprint "RESC3116X06N__1206RES")
      (description "Std Resistor")
      (libsource (lib "ResistorCapacitorInductor") (part "SMD_Resistor"))
    )
    (comp (ref "R6")
      (value "10K")
      (footprint "RESC1608X04N_0603RES")
      (description "Std Resistor")
      (libsource (lib "ResistorCapacitorInductor") (part "SMD_Resistor"))
    )
    (comp (ref "R7")
      (value "3K")
      (footprint "RESC3116X06N__1206RES")
      (description "Std Resistor")
      (libsource (lib "ResistorCapacitorInductor") (part "SMD_Resistor"))
    )
    (comp (ref "R8")
      (value "10K")
      (footprint "RESC1608X04N_0603RES")
      (description "Std Resistor")
      (libsource (lib "ResistorCapacitorInductor") (part "SMD_Resistor"))
    )
    (comp (ref "R9")
      (value "10K")
      (footprint "RESC1608X04N_0603RES")
      (description "Std Resistor")
      (libsource (lib "ResistorCapacitorInductor") (part "SMD_Resistor"))
    )
    (comp (ref "R10")
      (value "3K")
      (footprint "RESC3116X06N__1206RES")
      (description "Std Resistor")
      (libsource (lib "ResistorCapacitorInductor") (part "SMD_Resistor"))
    )
    (comp (ref "R11")
      (value "10K")
      (footprint "RESC1608X04N_0603RES")
      (description "Std Resistor")
      (libsource (lib "ResistorCapacitorInductor") (part "SMD_Resistor"))
    )
    (comp (ref "R12")
      (value "20K")
      (footprint "RESC1608X04N_0603RES")
      (description "Std Resistor")
      (libsource (lib "ResistorCapacitorInductor") (part "SMD_Resistor"))
    )
    (comp (ref "R13")
      (value "15K")
      (footprint "RESC1608X04N_0603RES")
      (description "Std Resistor")
      (libsource (lib "ResistorCapacitorInductor") (part "SMD_Resistor"))
    )
    (comp (ref "R14")
      (value "10K")
      (footprint "RESC1608X04N_0603RES")
      (description "Std Resistor")
      (libsource (lib "ResistorCapacitorInductor") (part "SMD_Resistor"))
    )
    (comp (ref "R15")
      (value "47K")
      (footprint "RESC1608X04N_0603RES")
      (description "Std Resistor")
      (libsource (lib "ResistorCapacitorInductor") (part "SMD_Resistor"))
    )
    (comp (ref "R16")
      (value "10K")
      (footprint "RESC1608X04N_0603RES")
      (description "Std Resistor")
      (libsource (lib "ResistorCapacitorInductor") (part "SMD_Resistor"))
    )
    (comp (ref "R17")
      (value "10K")
      (footprint "RESC1608X04N_0603RES")
      (description "Std Resistor")
      (libsource (lib "ResistorCapacitorInductor") (part "SMD_Resistor"))
    )
    (comp (ref "R18")
      (value "10K")
      (footprint "RESC1608X04N_0603RES")
      (description "Std Resistor")
      (libsource (lib "ResistorCapacitorInductor") (part "SMD_Resistor"))
    )
    (comp (ref "R19")
      (value "10K")
      (footprint "RESC1608X04N_0603RES")
      (description "Std Resistor")
      (libsource (lib "ResistorCapacitorInductor") (part "SMD_Resistor"))
    )
    (comp (ref "R20")
      (value "10K")
      (footprint "RESC1608X04N_0603RES")
      (description "Std Resistor")
      (libsource (lib "ResistorCapacitorInductor") (part "SMD_Resistor"))
    )
    (comp (ref "R21")
      (value "10K")
      (footprint "RESC1608X04N_0603RES")
      (description "Std Resistor")
      (libsource (lib "ResistorCapacitorInductor") (part "SMD_Resistor"))
    )
    (comp (ref "R22")
      (value "47K")
      (footprint "RESC1608X04N_0603RES")
      (description "Std Resistor")
      (libsource (lib "ResistorCapacitorInductor") (part "SMD_Resistor"))
    )
    (comp (ref "R23")
      (value "650Ω")
      (footprint "RESC1608X04N_0603RES")
      (description "Std Resistor")
      (libsource (lib "ResistorCapacitorInductor") (part "SMD_Resistor"))
    )
    (comp (ref "R24")
      (value "27")
      (footprint "RESC1608X04N_0603RES")
      (description "Std Resistor")
      (libsource (lib "ResistorCapacitorInductor") (part "SMD_Resistor"))
    )
    (comp (ref "R25")
      (value "0Ω")
      (footprint "RESC6432X06N__2512RES")
      (description "Std Resistor")
      (libsource (lib "ResistorCapacitorInductor") (part "SMD_Resistor"))
    )
    (comp (ref "R26")
      (value "10K")
      (footprint "RESC1608X04N_0603RES")
      (description "Std Resistor")
      (libsource (lib "ResistorCapacitorInductor") (part "SMD_Resistor"))
    )
    (comp (ref "R27")
      (value "10K")
      (footprint "RESC1608X04N_0603RES")
      (description "Std Resistor")
      (libsource (lib "ResistorCapacitorInductor") (part "SMD_Resistor"))
    )
    (comp (ref "R28")
      (value "10K")
      (footprint "RESC1608X04N_0603RES")
      (description "Std Resistor")
      (libsource (lib "ResistorCapacitorInductor") (part "SMD_Resistor"))
    )
    (comp (ref "R29")
      (value "10K")
      (footprint "RESC1608X04N_0603RES")
      (description "Std Resistor")
      (libsource (lib "ResistorCapacitorInductor") (part "SMD_Resistor"))
    )
    (comp (ref "R30")
      (value "10K")
      (footprint "RESC1608X04N_0603RES")
      (description "Std Resistor")
      (libsource (lib "ResistorCapacitorInductor") (part "SMD_Resistor"))
    )
    (comp (ref "R31")
      (value "10K")
      (footprint "RESC1608X04N_0603RES")
      (description "Std Resistor")
      (libsource (lib "ResistorCapacitorInductor") (part "SMD_Resistor"))
    )
    (comp (ref "R32")
      (value "10K")
      (footprint "RESC1608X04N_0603RES")
      (description "Std Resistor")
      (libsource (lib "ResistorCapacitorInductor") (part "SMD_Resistor"))
    )
    (comp (ref "R33")
      (value "47K")
      (footprint "RESC1608X04N_0603RES")
      (description "Std Resistor")
      (libsource (lib "ResistorCapacitorInductor") (part "SMD_Resistor"))
    )
    (comp (ref "R34")
      (value "10K")
      (footprint "RESC1608X04N_0603RES")
      (description "Std Resistor")
      (libsource (lib "ResistorCapacitorInductor") (part "SMD_Resistor"))
    )
    (comp (ref "R35")
      (value "10K")
      (footprint "RESC1608X04N_0603RES")
      (description "Std Resistor")
      (libsource (lib "ResistorCapacitorInductor") (part "SMD_Resistor"))
    )
    (comp (ref "R36")
      (value "10K")
      (footprint "RESC1608X04N_0603RES")
      (description "Std Resistor")
      (libsource (lib "ResistorCapacitorInductor") (part "SMD_Resistor"))
    )
    (comp (ref "R37")
      (value "10K")
      (footprint "RESC1608X04N_0603RES")
      (description "Std Resistor")
      (libsource (lib "ResistorCapacitorInductor") (part "SMD_Resistor"))
    )
    (comp (ref "R38")
      (value "10K")
      (footprint "RESC1608X04N_0603RES")
      (description "Std Resistor")
      (libsource (lib "ResistorCapacitorInductor") (part "SMD_Resistor"))
    )
    (comp (ref "R39")
      (value "10K")
      (footprint "RESC1608X04N_0603RES")
      (description "Std Resistor")
      (libsource (lib "ResistorCapacitorInductor") (part "SMD_Resistor"))
    )
    (comp (ref "R40")
      (value "47K")
      (footprint "RESC1608X04N_0603RES")
      (description "Std Resistor")
      (libsource (lib "ResistorCapacitorInductor") (part "SMD_Resistor"))
    )
    (comp (ref "R41")
      (value "10K")
      (footprint "RESC1608X04N_0603RES")
      (description "Std Resistor")
      (libsource (lib "ResistorCapacitorInductor") (part "SMD_Resistor"))
    )
    (comp (ref "R42")
      (value "10K")
      (footprint "RESC1608X04N_0603RES")
      (description "Std Resistor")
      (libsource (lib "ResistorCapacitorInductor") (part "SMD_Resistor"))
    )
    (comp (ref "R43")
      (value "47K")
      (footprint "RESC1608X04N_0603RES")
      (description "Std Resistor")
      (libsource (lib "ResistorCapacitorInductor") (part "SMD_Resistor"))
    )
    (comp (ref "R44")
      (value "10K")
      (footprint "RESC1608X04N_0603RES")
      (description "Std Resistor")
      (libsource (lib "ResistorCapacitorInductor") (part "SMD_Resistor"))
    )
    (comp (ref "R45")
      (value "10K")
      (footprint "RESC1608X04N_0603RES")
      (description "Std Resistor")
      (libsource (lib "ResistorCapacitorInductor") (part "SMD_Resistor"))
    )
    (comp (ref "R46")
      (value "47K")
      (footprint "RESC1608X04N_0603RES")
      (description "Std Resistor")
      (libsource (lib "ResistorCapacitorInductor") (part "SMD_Resistor"))
    )
    (comp (ref "R47")
      (value "10K")
      (footprint "RESC1608X04N_0603RES")
      (description "Std Resistor")
      (libsource (lib "ResistorCapacitorInductor") (part "SMD_Resistor"))
    )
    (comp (ref "R48")
      (value "10K")
      (footprint "RESC1608X04N_0603RES")
      (description "Std Resistor")
      (libsource (lib "ResistorCapacitorInductor") (part "SMD_Resistor"))
    )
    (comp (ref "R49")
      (value "47K")
      (footprint "RESC1608X04N_0603RES")
      (description "Std Resistor")
      (libsource (lib "ResistorCapacitorInductor") (part "SMD_Resistor"))
    )
    (comp (ref "R50")
      (value "1K")
      (footprint "RESC1608X04N_0603RES")
      (description "Std Resistor")
      (libsource (lib "ResistorCapacitorInductor") (part "SMD_Resistor"))
    )
    (comp (ref "R51")
      (value "650Ω")
      (footprint "RESC1608X04N_0603RES")
      (description "Std Resistor")
      (libsource (lib "ResistorCapacitorInductor") (part "SMD_Resistor"))
    )
    (comp (ref "R52")
      (value "47K")
      (footprint "RESC1608X04N_0603RES")
      (description "Std Resistor")
      (libsource (lib "ResistorCapacitorInductor") (part "SMD_Resistor"))
    )
    (comp (ref "R53")
      (value "27")
      (footprint "RESC1608X04N_0603RES")
      (description "Std Resistor")
      (libsource (lib "ResistorCapacitorInductor") (part "SMD_Resistor"))
    )
    (comp (ref "R54")
      (value "650Ω")
      (footprint "RESC1608X04N_0603RES")
      (description "Std Resistor")
      (libsource (lib "ResistorCapacitorInductor") (part "SMD_Resistor"))
    )
    (comp (ref "R55")
      (value "27")
      (footprint "RESC1608X04N_0603RES")
      (description "Std Resistor")
      (libsource (lib "ResistorCapacitorInductor") (part "SMD_Resistor"))
    )
    (comp (ref "R56")
      (value "PCB_Jumper_QM8.2")
      (footprint "PCB_Jumper")
      (libsource (lib "ResistorCapacitorInductor") (part "PCB_Jumper_QM8.2"))
    )
    (comp (ref "R57")
      (value "10K")
      (footprint "RESC1608X04N_0603RES")
      (description "Std Resistor")
      (libsource (lib "ResistorCapacitorInductor") (part "SMD_Resistor"))
    )
    (comp (ref "R58")
      (value "10K")
      (footprint "RESC1608X04N_0603RES")
      (description "Std Resistor")
      (libsource (lib "ResistorCapacitorInductor") (part "SMD_Resistor"))
    )
    (comp (ref "R59")
      (value "10K")
      (footprint "RESC1608X04N_0603RES")
      (description "Std Resistor")
      (libsource (lib "ResistorCapacitorInductor") (part "SMD_Resistor"))
    )
    (comp (ref "R60")
      (value "10K")
      (footprint "RESC1608X04N_0603RES")
      (description "Std Resistor")
      (libsource (lib "ResistorCapacitorInductor") (part "SMD_Resistor"))
    )
    (comp (ref "R61")
      (value "10K")
      (footprint "RESC1608X04N_0603RES")
      (description "Std Resistor")
      (libsource (lib "ResistorCapacitorInductor") (part "SMD_Resistor"))
    )
    (comp (ref "R62")
      (value "10K")
      (footprint "RESC1608X04N_0603RES")
      (description "Std Resistor")
      (libsource (lib "ResistorCapacitorInductor") (part "SMD_Resistor"))
    )
    (comp (ref "R63")
      (value "10K")
      (footprint "RESC1608X04N_0603RES")
      (description "Std Resistor")
      (libsource (lib "ResistorCapacitorInductor") (part "SMD_Resistor"))
    )
    (comp (ref "R64")
      (value "47K")
      (footprint "RESC1608X04N_0603RES")
      (description "Std Resistor")
      (libsource (lib "ResistorCapacitorInductor") (part "SMD_Resistor"))
    )
    (comp (ref "R65")
      (value "10K")
      (footprint "RESC1608X04N_0603RES")
      (description "Std Resistor")
      (libsource (lib "ResistorCapacitorInductor") (part "SMD_Resistor"))
    )
    (comp (ref "R66")
      (value "10K")
      (footprint "RESC1608X04N_0603RES")
      (description "Std Resistor")
      (libsource (lib "ResistorCapacitorInductor") (part "SMD_Resistor"))
    )
    (comp (ref "R67")
      (value "47K")
      (footprint "RESC1608X04N_0603RES")
      (description "Std Resistor")
      (libsource (lib "ResistorCapacitorInductor") (part "SMD_Resistor"))
    )
    (comp (ref "R68")
      (value "10K")
      (footprint "RESC1608X04N_0603RES")
      (description "Std Resistor")
      (libsource (lib "ResistorCapacitorInductor") (part "SMD_Resistor"))
    )
    (comp (ref "R69")
      (value "10K")
      (footprint "RESC1608X04N_0603RES")
      (description "Std Resistor")
      (libsource (lib "ResistorCapacitorInductor") (part "SMD_Resistor"))
    )
    (comp (ref "R70")
      (value "10K")
      (footprint "RESC1608X04N_0603RES")
      (description "Std Resistor")
      (libsource (lib "ResistorCapacitorInductor") (part "SMD_Resistor"))
    )
    (comp (ref "R71")
      (value "10K")
      (footprint "RESC1608X04N_0603RES")
      (description "Std Resistor")
      (libsource (lib "ResistorCapacitorInductor") (part "SMD_Resistor"))
    )
    (comp (ref "R72")
      (value "10K")
      (footprint "RESC1608X04N_0603RES")
      (description "Std Resistor")
      (libsource (lib "ResistorCapacitorInductor") (part "SMD_Resistor"))
    )
    (comp (ref "R73")
      (value "10K")
      (footprint "RESC1608X04N_0603RES")
      (description "Std Resistor")
      (libsource (lib "ResistorCapacitorInductor") (part "SMD_Resistor"))
    )
    (comp (ref "R74")
      (value "47K")
      (footprint "RESC1608X04N_0603RES")
      (description "Std Resistor")
      (libsource (lib "ResistorCapacitorInductor") (part "SMD_Resistor"))
    )
    (comp (ref "R75")
      (value "10K")
      (footprint "RESC1608X04N_0603RES")
      (description "Std Resistor")
      (libsource (lib "ResistorCapacitorInductor") (part "SMD_Resistor"))
    )
    (comp (ref "R76")
      (value "10K")
      (footprint "RESC1608X04N_0603RES")
      (description "Std Resistor")
      (libsource (lib "ResistorCapacitorInductor") (part "SMD_Resistor"))
    )
    (comp (ref "R77")
      (value "47K")
      (footprint "RESC1608X04N_0603RES")
      (description "Std Resistor")
      (libsource (lib "ResistorCapacitorInductor") (part "SMD_Resistor"))
    )
    (comp (ref "R78")
      (value "10K")
      (footprint "RESC1608X04N_0603RES")
      (description "Std Resistor")
      (libsource (lib "ResistorCapacitorInductor") (part "SMD_Resistor"))
    )
    (comp (ref "R79")
      (value "650Ω")
      (footprint "RESC1608X04N_0603RES")
      (description "Std Resistor")
      (libsource (lib "ResistorCapacitorInductor") (part "SMD_Resistor"))
    )
    (comp (ref "R80")
      (value "47K")
      (footprint "RESC1608X04N_0603RES")
      (description "Std Resistor")
      (libsource (lib "ResistorCapacitorInductor") (part "SMD_Resistor"))
    )
    (comp (ref "R81")
      (value "27")
      (footprint "RESC1608X04N_0603RES")
      (description "Std Resistor")
      (libsource (lib "ResistorCapacitorInductor") (part "SMD_Resistor"))
    )
    (comp (ref "R82")
      (value "10K")
      (footprint "RESC1608X04N_0603RES")
      (description "Std Resistor")
      (libsource (lib "ResistorCapacitorInductor") (part "SMD_Resistor"))
    )
    (comp (ref "R83")
      (value "47K")
      (footprint "RESC1608X04N_0603RES")
      (description "Std Resistor")
      (libsource (lib "ResistorCapacitorInductor") (part "SMD_Resistor"))
    )
    (comp (ref "R84")
      (value "650Ω")
      (footprint "RESC1608X04N_0603RES")
      (description "Std Resistor")
      (libsource (lib "ResistorCapacitorInductor") (part "SMD_Resistor"))
    )
    (comp (ref "R85")
      (value "27")
      (footprint "RESC1608X04N_0603RES")
      (description "Std Resistor")
      (libsource (lib "ResistorCapacitorInductor") (part "SMD_Resistor"))
    )
    (comp (ref "R86")
      (value "0Ω")
      (footprint "RESC6432X06N__2512RES")
      (description "Std Resistor")
      (libsource (lib "ResistorCapacitorInductor") (part "SMD_Resistor"))
    )
    (comp (ref "R87")
      (value "10K")
      (footprint "RESC1608X04N_0603RES")
      (description "Std Resistor")
      (libsource (lib "ResistorCapacitorInductor") (part "SMD_Resistor"))
    )
    (comp (ref "R88")
      (value "10K")
      (footprint "RESC1608X04N_0603RES")
      (description "Std Resistor")
      (libsource (lib "ResistorCapacitorInductor") (part "SMD_Resistor"))
    )
    (comp (ref "R89")
      (value "10K")
      (footprint "RESC1608X04N_0603RES")
      (description "Std Resistor")
      (libsource (lib "ResistorCapacitorInductor") (part "SMD_Resistor"))
    )
    (comp (ref "R90")
      (value "10K")
      (footprint "RESC1608X04N_0603RES")
      (description "Std Resistor")
      (libsource (lib "ResistorCapacitorInductor") (part "SMD_Resistor"))
    )
    (comp (ref "R91")
      (value "10K")
      (footprint "RESC1608X04N_0603RES")
      (description "Std Resistor")
      (libsource (lib "ResistorCapacitorInductor") (part "SMD_Resistor"))
    )
    (comp (ref "R92")
      (value "10K")
      (footprint "RESC1608X04N_0603RES")
      (description "Std Resistor")
      (libsource (lib "ResistorCapacitorInductor") (part "SMD_Resistor"))
    )
    (comp (ref "R93")
      (value "10K")
      (footprint "RESC1608X04N_0603RES")
      (description "Std Resistor")
      (libsource (lib "ResistorCapacitorInductor") (part "SMD_Resistor"))
    )
    (comp (ref "R94")
      (value "47K")
      (footprint "RESC1608X04N_0603RES")
      (description "Std Resistor")
      (libsource (lib "ResistorCapacitorInductor") (part "SMD_Resistor"))
    )
    (comp (ref "R95")
      (value "10K")
      (footprint "RESC1608X04N_0603RES")
      (description "Std Resistor")
      (libsource (lib "ResistorCapacitorInductor") (part "SMD_Resistor"))
    )
    (comp (ref "R96")
      (value "10K")
      (footprint "RESC1608X04N_0603RES")
      (description "Std Resistor")
      (libsource (lib "ResistorCapacitorInductor") (part "SMD_Resistor"))
    )
    (comp (ref "R97")
      (value "47K")
      (footprint "RESC1608X04N_0603RES")
      (description "Std Resistor")
      (libsource (lib "ResistorCapacitorInductor") (part "SMD_Resistor"))
    )
    (comp (ref "R98")
      (value "10K")
      (footprint "RESC1608X04N_0603RES")
      (description "Std Resistor")
      (libsource (lib "ResistorCapacitorInductor") (part "SMD_Resistor"))
    )
    (comp (ref "R99")
      (value "10K")
      (footprint "RESC1608X04N_0603RES")
      (description "Std Resistor")
      (libsource (lib "ResistorCapacitorInductor") (part "SMD_Resistor"))
    )
    (comp (ref "R100")
      (value "47K")
      (footprint "RESC1608X04N_0603RES")
      (description "Std Resistor")
      (libsource (lib "ResistorCapacitorInductor") (part "SMD_Resistor"))
    )
    (comp (ref "R101")
      (value "10K")
      (footprint "RESC1608X04N_0603RES")
      (description "Std Resistor")
      (libsource (lib "ResistorCapacitorInductor") (part "SMD_Resistor"))
    )
    (comp (ref "R102")
      (value "10K")
      (footprint "RESC1608X04N_0603RES")
      (description "Std Resistor")
      (libsource (lib "ResistorCapacitorInductor") (part "SMD_Resistor"))
    )
    (comp (ref "R103")
      (value "650Ω")
      (footprint "RESC1608X04N_0603RES")
      (description "Std Resistor")
      (libsource (lib "ResistorCapacitorInductor") (part "SMD_Resistor"))
    )
    (comp (ref "R104")
      (value "10K")
      (footprint "RESC1608X04N_0603RES")
      (description "Std Resistor")
      (libsource (lib "ResistorCapacitorInductor") (part "SMD_Resistor"))
    )
    (comp (ref "R105")
      (value "10K")
      (footprint "RESC1608X04N_0603RES")
      (description "Std Resistor")
      (libsource (lib "ResistorCapacitorInductor") (part "SMD_Resistor"))
    )
    (comp (ref "R106")
      (value "47K")
      (footprint "RESC1608X04N_0603RES")
      (description "Std Resistor")
      (libsource (lib "ResistorCapacitorInductor") (part "SMD_Resistor"))
    )
    (comp (ref "R107")
      (value "10K")
      (footprint "RESC1608X04N_0603RES")
      (description "Std Resistor")
      (libsource (lib "ResistorCapacitorInductor") (part "SMD_Resistor"))
    )
    (comp (ref "R108")
      (value "27")
      (footprint "RESC1608X04N_0603RES")
      (description "Std Resistor")
      (libsource (lib "ResistorCapacitorInductor") (part "SMD_Resistor"))
    )
    (comp (ref "R109")
      (value "10K")
      (footprint "RESC1608X04N_0603RES")
      (description "Std Resistor")
      (libsource (lib "ResistorCapacitorInductor") (part "SMD_Resistor"))
    )
    (comp (ref "R110")
      (value "47K")
      (footprint "RESC1608X04N_0603RES")
      (description "Std Resistor")
      (libsource (lib "ResistorCapacitorInductor") (part "SMD_Resistor"))
    )
    (comp (ref "R111")
      (value "10K")
      (footprint "RESC1608X04N_0603RES")
      (description "Std Resistor")
      (libsource (lib "ResistorCapacitorInductor") (part "SMD_Resistor"))
    )
    (comp (ref "R112")
      (value "10K")
      (footprint "RESC1608X04N_0603RES")
      (description "Std Resistor")
      (libsource (lib "ResistorCapacitorInductor") (part "SMD_Resistor"))
    )
    (comp (ref "R113")
      (value "47K")
      (footprint "RESC1608X04N_0603RES")
      (description "Std Resistor")
      (libsource (lib "ResistorCapacitorInductor") (part "SMD_Resistor"))
    )
    (comp (ref "R114")
      (value "0Ω")
      (footprint "RESC6432X06N__2512RES")
      (description "Std Resistor")
      (libsource (lib "ResistorCapacitorInductor") (part "SMD_Resistor"))
    )
    (comp (ref "R115")
      (value "650Ω")
      (footprint "RESC1608X04N_0603RES")
      (description "Std Resistor")
      (libsource (lib "ResistorCapacitorInductor") (part "SMD_Resistor"))
    )
    (comp (ref "R116")
      (value "0")
      (footprint "RESC6432X06N__2512RES")
      (description "Std Resistor")
      (libsource (lib "ResistorCapacitorInductor") (part "SMD_Resistor"))
    )
    (comp (ref "R117")
      (value "10K")
      (footprint "RESC1608X04N_0603RES")
      (description "Std Resistor")
      (libsource (lib "ResistorCapacitorInductor") (part "SMD_Resistor"))
    )
    (comp (ref "R118")
      (value "0")
      (footprint "RESC6432X06N__2512RES")
      (description "Std Resistor")
      (libsource (lib "ResistorCapacitorInductor") (part "SMD_Resistor"))
    )
    (comp (ref "R119")
      (value "27")
      (footprint "RESC1608X04N_0603RES")
      (description "Std Resistor")
      (libsource (lib "ResistorCapacitorInductor") (part "SMD_Resistor"))
    )
    (comp (ref "R120")
      (value "10K")
      (footprint "RESC1608X04N_0603RES")
      (description "Std Resistor")
      (libsource (lib "ResistorCapacitorInductor") (part "SMD_Resistor"))
    )
    (comp (ref "R121")
      (value "0")
      (footprint "RESC6432X06N__2512RES")
      (description "Std Resistor")
      (libsource (lib "ResistorCapacitorInductor") (part "SMD_Resistor"))
    )
    (comp (ref "R122")
      (value "0")
      (footprint "RESC6432X06N__2512RES")
      (description "Std Resistor")
      (libsource (lib "ResistorCapacitorInductor") (part "SMD_Resistor"))
    )
    (comp (ref "R123")
      (value "10K")
      (footprint "RESC1608X04N_0603RES")
      (description "Std Resistor")
      (libsource (lib "ResistorCapacitorInductor") (part "SMD_Resistor"))
    )
    (comp (ref "R124")
      (value "10K")
      (footprint "RESC1608X04N_0603RES")
      (description "Std Resistor")
      (libsource (lib "ResistorCapacitorInductor") (part "SMD_Resistor"))
    )
    (comp (ref "R125")
      (value "10K")
      (footprint "RESC1608X04N_0603RES")
      (description "Std Resistor")
      (libsource (lib "ResistorCapacitorInductor") (part "SMD_Resistor"))
    )
    (comp (ref "R126")
      (value "10K")
      (footprint "RESC1608X04N_0603RES")
      (description "Std Resistor")
      (libsource (lib "ResistorCapacitorInductor") (part "SMD_Resistor"))
    )
    (comp (ref "R127")
      (value "10K")
      (footprint "RESC1608X04N_0603RES")
      (description "Std Resistor")
      (libsource (lib "ResistorCapacitorInductor") (part "SMD_Resistor"))
    )
    (comp (ref "R128")
      (value "10K")
      (footprint "RESC1608X04N_0603RES")
      (description "Std Resistor")
      (libsource (lib "ResistorCapacitorInductor") (part "SMD_Resistor"))
    )
    (comp (ref "R129")
      (value "47K")
      (footprint "RESC1608X04N_0603RES")
      (description "Std Resistor")
      (libsource (lib "ResistorCapacitorInductor") (part "SMD_Resistor"))
    )
    (comp (ref "R130")
      (value "1K")
      (footprint "RESC1608X04N_0603RES")
      (description "Std Resistor")
      (libsource (lib "ResistorCapacitorInductor") (part "SMD_Resistor"))
    )
    (comp (ref "R131")
      (value "10K")
      (footprint "RESC1608X04N_0603RES")
      (description "Std Resistor")
      (libsource (lib "ResistorCapacitorInductor") (part "SMD_Resistor"))
    )
    (comp (ref "R132")
      (value "10K")
      (footprint "RESC1608X04N_0603RES")
      (description "Std Resistor")
      (libsource (lib "ResistorCapacitorInductor") (part "SMD_Resistor"))
    )
    (comp (ref "R133")
      (value "47K")
      (footprint "RESC1608X04N_0603RES")
      (description "Std Resistor")
      (libsource (lib "ResistorCapacitorInductor") (part "SMD_Resistor"))
    )
    (comp (ref "R134")
      (value "10K")
      (footprint "RESC1608X04N_0603RES")
      (description "Std Resistor")
      (libsource (lib "ResistorCapacitorInductor") (part "SMD_Resistor"))
    )
    (comp (ref "R135")
      (value "10K")
      (footprint "RESC1608X04N_0603RES")
      (description "Std Resistor")
      (libsource (lib "ResistorCapacitorInductor") (part "SMD_Resistor"))
    )
    (comp (ref "R136")
      (value "47K")
      (footprint "RESC1608X04N_0603RES")
      (description "Std Resistor")
      (libsource (lib "ResistorCapacitorInductor") (part "SMD_Resistor"))
    )
    (comp (ref "R137")
      (value "10K")
      (footprint "RESC1608X04N_0603RES")
      (description "Std Resistor")
      (libsource (lib "ResistorCapacitorInductor") (part "SMD_Resistor"))
    )
    (comp (ref "R138")
      (value "3K")
      (footprint "RESC1608X04N_0603RES")
      (description "Std Resistor")
      (libsource (lib "ResistorCapacitorInductor") (part "SMD_Resistor"))
    )
    (comp (ref "R139")
      (value "650Ω")
      (footprint "RESC1608X04N_0603RES")
      (description "Std Resistor")
      (libsource (lib "ResistorCapacitorInductor") (part "SMD_Resistor"))
    )
    (comp (ref "R140")
      (value "47K")
      (footprint "RESC1608X04N_0603RES")
      (description "Std Resistor")
      (libsource (lib "ResistorCapacitorInductor") (part "SMD_Resistor"))
    )
    (comp (ref "R141")
      (value "27")
      (footprint "RESC1608X04N_0603RES")
      (description "Std Resistor")
      (libsource (lib "ResistorCapacitorInductor") (part "SMD_Resistor"))
    )
    (comp (ref "R142")
      (value "0")
      (footprint "RESC6432X06N__2512RES")
      (description "Std Resistor")
      (libsource (lib "ResistorCapacitorInductor") (part "SMD_Resistor"))
    )
    (comp (ref "R143")
      (value "10K")
      (footprint "RESC1608X04N_0603RES")
      (description "Std Resistor")
      (libsource (lib "ResistorCapacitorInductor") (part "SMD_Resistor"))
    )
    (comp (ref "R144")
      (value "10K")
      (footprint "RESC1608X04N_0603RES")
      (description "Std Resistor")
      (libsource (lib "ResistorCapacitorInductor") (part "SMD_Resistor"))
    )
    (comp (ref "R145")
      (value "10K")
      (footprint "RESC1608X04N_0603RES")
      (description "Std Resistor")
      (libsource (lib "ResistorCapacitorInductor") (part "SMD_Resistor"))
    )
    (comp (ref "R146")
      (value "10K")
      (footprint "RESC1608X04N_0603RES")
      (description "Std Resistor")
      (libsource (lib "ResistorCapacitorInductor") (part "SMD_Resistor"))
    )
    (comp (ref "R147")
      (value "0")
      (footprint "RESC6432X06N__2512RES")
      (description "Std Resistor")
      (libsource (lib "ResistorCapacitorInductor") (part "SMD_Resistor"))
    )
    (comp (ref "R148")
      (value "10K")
      (footprint "RESC1608X04N_0603RES")
      (description "Std Resistor")
      (libsource (lib "ResistorCapacitorInductor") (part "SMD_Resistor"))
    )
    (comp (ref "R149")
      (value "10K")
      (footprint "RESC1608X04N_0603RES")
      (description "Std Resistor")
      (libsource (lib "ResistorCapacitorInductor") (part "SMD_Resistor"))
    )
    (comp (ref "R150")
      (value "47K")
      (footprint "RESC1608X04N_0603RES")
      (description "Std Resistor")
      (libsource (lib "ResistorCapacitorInductor") (part "SMD_Resistor"))
    )
    (comp (ref "R151")
      (value "10K")
      (footprint "RESC1608X04N_0603RES")
      (description "Std Resistor")
      (libsource (lib "ResistorCapacitorInductor") (part "SMD_Resistor"))
    )
    (comp (ref "R152")
      (value "1.8K")
      (footprint "RESC1608X04N_0603RES")
      (description "Std Resistor")
      (libsource (lib "ResistorCapacitorInductor") (part "SMD_Resistor"))
    )
    (comp (ref "R153")
      (value "10K")
      (footprint "RESC1608X04N_0603RES")
      (description "Std Resistor")
      (libsource (lib "ResistorCapacitorInductor") (part "SMD_Resistor"))
    )
    (comp (ref "R154")
      (value "47K")
      (footprint "RESC1608X04N_0603RES")
      (description "Std Resistor")
      (libsource (lib "ResistorCapacitorInductor") (part "SMD_Resistor"))
    )
    (comp (ref "R155")
      (value "650Ω")
      (footprint "RESC1608X04N_0603RES")
      (description "Std Resistor")
      (libsource (lib "ResistorCapacitorInductor") (part "SMD_Resistor"))
    )
    (comp (ref "R156")
      (value "10K")
      (footprint "RESC1608X04N_0603RES")
      (description "Std Resistor")
      (libsource (lib "ResistorCapacitorInductor") (part "SMD_Resistor"))
    )
    (comp (ref "R157")
      (value "10K")
      (footprint "RESC1608X04N_0603RES")
      (description "Std Resistor")
      (libsource (lib "ResistorCapacitorInductor") (part "SMD_Resistor"))
    )
    (comp (ref "R158")
      (value "10K")
      (footprint "RESC1608X04N_0603RES")
      (description "Std Resistor")
      (libsource (lib "ResistorCapacitorInductor") (part "SMD_Resistor"))
    )
    (comp (ref "R159")
      (value "10K")
      (footprint "RESC1608X04N_0603RES")
      (description "Std Resistor")
      (libsource (lib "ResistorCapacitorInductor") (part "SMD_Resistor"))
    )
    (comp (ref "R160")
      (value "10K")
      (footprint "RESC1608X04N_0603RES")
      (description "Std Resistor")
      (libsource (lib "ResistorCapacitorInductor") (part "SMD_Resistor"))
    )
    (comp (ref "R161")
      (value "10K")
      (footprint "RESC1608X04N_0603RES")
      (description "Std Resistor")
      (libsource (lib "ResistorCapacitorInductor") (part "SMD_Resistor"))
    )
    (comp (ref "R162")
      (value "27")
      (footprint "RESC1608X04N_0603RES")
      (description "Std Resistor")
      (libsource (lib "ResistorCapacitorInductor") (part "SMD_Resistor"))
    )
    (comp (ref "R163")
      (value "10K")
      (footprint "RESC1608X04N_0603RES")
      (description "Std Resistor")
      (libsource (lib "ResistorCapacitorInductor") (part "SMD_Resistor"))
    )
    (comp (ref "R164")
      (value "0")
      (footprint "RESC6432X06N__2512RES")
      (description "Std Resistor")
      (libsource (lib "ResistorCapacitorInductor") (part "SMD_Resistor"))
    )
    (comp (ref "R165")
      (value "47K")
      (footprint "RESC1608X04N_0603RES")
      (description "Std Resistor")
      (libsource (lib "ResistorCapacitorInductor") (part "SMD_Resistor"))
    )
    (comp (ref "R166")
      (value "10K")
      (footprint "RESC1608X04N_0603RES")
      (description "Std Resistor")
      (libsource (lib "ResistorCapacitorInductor") (part "SMD_Resistor"))
    )
    (comp (ref "R167")
      (value "0")
      (footprint "RESC6432X06N__2512RES")
      (description "Std Resistor")
      (libsource (lib "ResistorCapacitorInductor") (part "SMD_Resistor"))
    )
    (comp (ref "R168")
      (value "10K")
      (footprint "RESC1608X04N_0603RES")
      (description "Std Resistor")
      (libsource (lib "ResistorCapacitorInductor") (part "SMD_Resistor"))
    )
    (comp (ref "R169")
      (value "10K")
      (footprint "RESC1608X04N_0603RES")
      (description "Std Resistor")
      (libsource (lib "ResistorCapacitorInductor") (part "SMD_Resistor"))
    )
    (comp (ref "R170")
      (value "47K")
      (footprint "RESC1608X04N_0603RES")
      (description "Std Resistor")
      (libsource (lib "ResistorCapacitorInductor") (part "SMD_Resistor"))
    )
    (comp (ref "R171")
      (value "10K")
      (footprint "RESC1608X04N_0603RES")
      (description "Std Resistor")
      (libsource (lib "ResistorCapacitorInductor") (part "SMD_Resistor"))
    )
    (comp (ref "R172")
      (value "10K")
      (footprint "RESC1608X04N_0603RES")
      (description "Std Resistor")
      (libsource (lib "ResistorCapacitorInductor") (part "SMD_Resistor"))
    )
    (comp (ref "R173")
      (value "47K")
      (footprint "RESC1608X04N_0603RES")
      (description "Std Resistor")
      (libsource (lib "ResistorCapacitorInductor") (part "SMD_Resistor"))
    )
    (comp (ref "R174")
      (value "10K")
      (footprint "RESC1608X04N_0603RES")
      (description "Std Resistor")
      (libsource (lib "ResistorCapacitorInductor") (part "SMD_Resistor"))
    )
    (comp (ref "R175")
      (value "1.8K")
      (footprint "RESC1608X04N_0603RES")
      (description "Std Resistor")
      (libsource (lib "ResistorCapacitorInductor") (part "SMD_Resistor"))
    )
    (comp (ref "R176")
      (value "650Ω")
      (footprint "RESC1608X04N_0603RES")
      (description "Std Resistor")
      (libsource (lib "ResistorCapacitorInductor") (part "SMD_Resistor"))
    )
    (comp (ref "R177")
      (value "47K")
      (footprint "RESC1608X04N_0603RES")
      (description "Std Resistor")
      (libsource (lib "ResistorCapacitorInductor") (part "SMD_Resistor"))
    )
    (comp (ref "R178")
      (value "27")
      (footprint "RESC1608X04N_0603RES")
      (description "Std Resistor")
      (libsource (lib "ResistorCapacitorInductor") (part "SMD_Resistor"))
    )
    (comp (ref "RST1")
      (value "TS-1088-AR02016")
      (footprint "SW-SMD_L3.9-W3.0-P4.45")
      (description "Switch")
      (libsource (lib "Switches") (part "TS-1088-AR02016"))
    )
    (comp (ref "RST2")
      (value "TS-1088-AR02016")
      (footprint "SW-SMD_L3.9-W3.0-P4.45")
      (description "Switch")
      (libsource (lib "Switches") (part "TS-1088-AR02016"))
    )
    (comp (ref "RST3")
      (value "TS-1088-AR02016")
      (footprint "SW-SMD_L3.9-W3.0-P4.45")
      (description "Switch")
      (libsource (lib "Switches") (part "TS-1088-AR02016"))
    )
    (comp (ref "U1")
      (value "M7_C2902910")
      (footprint "SMA_L4.5-W2.7-LS5.1-RD")
      (fields (field (name "MANUFACTURER") "MSKSEMI(美森科)") (field (name "MANUFACTURER PART") "M7"))
      (libsource (lib "Diodes") (part "M7_C2902910"))
    )
    (comp (ref "U2")
      (value "K7805MT_1000R4")
      (footprint "K7805MT_500R4")
      (libsource (lib "DCDC_Converter") (part "K78052MT_1000R4"))
    )
    (comp (ref "U3")
      (value "K7805MT_1000R4")
      (footprint "K7805MT_500R4")
      (libsource (lib "DCDC_Converter") (part "K78052MT_1000R4"))
    )
    (comp (ref "U4")
      (value "K7805MT_1000R4")
      (footprint "K7805MT_500R4")
      (libsource (lib "DCDC_Converter") (part "K78052MT_1000R4"))
    )
    (comp (ref "U5")
      (value "ZX-PZ2.54-2-5PZZ")
      (footprint "HDR-TH_10P-P2.54-V-M-R2-C5-S2.54")
      (fields (field (name "MANUFACTURER") "Megastar(兆星)"))
      (libsource (lib "Connector") (part "ZX-PZ2.54-2-5PZZ"))
    )
    (comp (ref "U6")
      (value "KF301-5.0-2P")
      (footprint "CONN-TH_P5.00_KF301-5.0-2P")
      (description "螺钉式接线端子 C474881")
      (fields (field (name "MANUFACTURER") "KEFA(科发)"))
      (libsource (lib "Connector") (part "KF301-5.0-2P"))
    )
    (comp (ref "U7")
      (value "K7805MT_1000R4")
      (footprint "K7805MT_500R4")
      (libsource (lib "DCDC_Converter") (part "K78052MT_1000R4"))
    )
    (comp (ref "VBAT1")
      (value "Bolt_Connecter")
      (footprint "Bolt_Connecter")
      (libsource (lib "Connector") (part "Bolt_Connecter"))
    )
    (comp (ref "ZDB1")
      (value "SMAJ58CA")
      (footprint "SMA/DO214AC-BIPOLAR")
      (description "Bipolar Transient Voltage Supressor")
      (libsource (lib "Diodes") (part "TVS_Diode_Bipolar"))
    )
    (comp (ref "ZDB2")
      (value "SMAJ58CA")
      (footprint "SMA/DO214AC-BIPOLAR")
      (description "Bipolar Transient Voltage Supressor")
      (libsource (lib "Diodes") (part "TVS_Diode_Bipolar"))
    )
    (comp (ref "ZDB3")
      (value "SMAJ58CA")
      (footprint "SMA/DO214AC-BIPOLAR")
      (description "Bipolar Transient Voltage Supressor")
      (libsource (lib "Diodes") (part "TVS_Diode_Bipolar"))
    )
    (comp (ref "ZDB4")
      (value "SMAJ58CA")
      (footprint "SMA/DO214AC-BIPOLAR")
      (description "Bipolar Transient Voltage Supressor")
      (libsource (lib "Diodes") (part "TVS_Diode_Bipolar"))
    )
    (comp (ref "ZDB5")
      (value "SMAJ58CA")
      (footprint "SMA/DO214AC-BIPOLAR")
      (description "Bipolar Transient Voltage Supressor")
      (libsource (lib "Diodes") (part "TVS_Diode_Bipolar"))
    )
    (comp (ref "ZDB6")
      (value "SMAJ58CA")
      (footprint "SMA/DO214AC-BIPOLAR")
      (description "Bipolar Transient Voltage Supressor")
      (libsource (lib "Diodes") (part "TVS_Diode_Bipolar"))
    )
    (comp (ref "ZDB7")
      (value "SMAJ58CA")
      (footprint "SMA/DO214AC-BIPOLAR")
      (description "Bipolar Transient Voltage Supressor")
      (libsource (lib "Diodes") (part "TVS_Diode_Bipolar"))
    )
    (comp (ref "ZDB8")
      (value "SMAJ58CA")
      (footprint "SMA/DO214AC-BIPOLAR")
      (description "Bipolar Transient Voltage Supressor")
      (libsource (lib "Diodes") (part "TVS_Diode_Bipolar"))
    )
    (comp (ref "ZDB9")
      (value "SMAJ58CA")
      (footprint "SMA/DO214AC-BIPOLAR")
      (description "Bipolar Transient Voltage Supressor")
      (libsource (lib "Diodes") (part "TVS_Diode_Bipolar"))
    )
    (comp (ref "ZDB10")
      (value "SMAJ58CA")
      (footprint "SMA/DO214AC-BIPOLAR")
      (description "Bipolar Transient Voltage Supressor")
      (libsource (lib "Diodes") (part "TVS_Diode_Bipolar"))
    )
  )
  (nets
    (net (code "1") (name "/ACCU_PWR") (class "Default")
      (node (ref "C21") (pin "2") (pintype "passive"))
      (node (ref "IC4") (pin "13") (pinfunction "OUT3_13") (pintype "passive"))
      (node (ref "LOW1") (pin "16") (pinfunction "16_16") (pintype "passive"))
      (node (ref "R80") (pin "2") (pintype "passive"))
    )
    (net (code "2") (name "/ACCU_PWR_EN") (class "Default")
      (node (ref "CN3") (pin "35") (pinfunction "35_35") (pintype "passive"))
      (node (ref "R58") (pin "2") (pintype "passive"))
      (node (ref "R72") (pin "2") (pintype "passive"))
    )
    (net (code "3") (name "/ACCU_UBR") (class "Default")
      (node (ref "C61") (pin "2") (pintype "passive"))
      (node (ref "IC11") (pin "17") (pinfunction "OUT2_17") (pintype "passive"))
      (node (ref "LOW1") (pin "20") (pinfunction "20_20") (pintype "passive"))
      (node (ref "R173") (pin "2") (pintype "passive"))
    )
    (net (code "4") (name "/ACCU_UBR_EN") (class "Default")
      (node (ref "CN3") (pin "16") (pinfunction "16_16") (pintype "passive"))
      (node (ref "R158") (pin "2") (pintype "passive"))
      (node (ref "R171") (pin "2") (pintype "passive"))
    )
    (net (code "5") (name "/AIR+") (class "Default")
      (node (ref "HIGH1") (pin "7") (pinfunction "7_7") (pintype "passive"))
      (node (ref "K2") (pin "1") (pinfunction "COIL_1_1") (pintype "passive"))
    )
    (net (code "6") (name "/BATTERY_1") (class "Default")
      (node (ref "FU1") (pin "1") (pintype "passive"))
      (node (ref "J3") (pin "+") (pinfunction "+_+") (pintype "passive"))
      (node (ref "R4") (pin "2") (pintype "passive"))
    )
    (net (code "7") (name "/BATTERY_2") (class "Default")
      (node (ref "J1") (pin "+") (pinfunction "+_+") (pintype "passive"))
      (node (ref "J3") (pin "-") (pinfunction "-_-") (pintype "passive"))
      (node (ref "R3") (pin "2") (pintype "passive"))
    )
    (net (code "8") (name "/BAT_voltage_IN14") (class "Default")
      (node (ref "CN4") (pin "5") (pinfunction "5_5") (pintype "passive"))
      (node (ref "R13") (pin "2") (pintype "passive"))
      (node (ref "R20") (pin "1") (pintype "passive"))
    )
    (net (code "9") (name "/BAT_voltage_IN15") (class "Default")
      (node (ref "CN4") (pin "4") (pinfunction "4_4") (pintype "passive"))
      (node (ref "R12") (pin "2") (pintype "passive"))
      (node (ref "R19") (pin "1") (pintype "passive"))
    )
    (net (code "10") (name "/BDU_PWR") (class "Default")
      (node (ref "C30") (pin "2") (pintype "passive"))
      (node (ref "IC6") (pin "13") (pinfunction "OUT3_13") (pintype "passive"))
      (node (ref "LOW1") (pin "17") (pinfunction "17_17") (pintype "passive"))
      (node (ref "R106") (pin "2") (pintype "passive"))
    )
    (net (code "11") (name "/BDU_PWR_EN") (class "Default")
      (node (ref "CN3") (pin "28") (pinfunction "28_28") (pintype "passive"))
      (node (ref "R88") (pin "2") (pintype "passive"))
      (node (ref "R99") (pin "2") (pintype "passive"))
    )
    (net (code "12") (name "/BSPD_PWR") (class "Default")
      (node (ref "C19") (pin "2") (pintype "passive"))
      (node (ref "IC4") (pin "17") (pinfunction "OUT2_17") (pintype "passive"))
      (node (ref "LOW1") (pin "6") (pinfunction "6_6") (pintype "passive"))
      (node (ref "R74") (pin "2") (pintype "passive"))
    )
    (net (code "13") (name "/BSPD_PWR_EN") (class "Default")
      (node (ref "CN3") (pin "36") (pinfunction "36_36") (pintype "passive"))
      (node (ref "R59") (pin "2") (pintype "passive"))
      (node (ref "R68") (pin "2") (pintype "passive"))
    )
    (net (code "14") (name "/BUZZER_CTRL") (class "Default")
      (node (ref "LOW2") (pin "10") (pinfunction "10_10") (pintype "passive+no_connect"))
    )
    (net (code "15") (name "/BUZZER_PWR") (class "Default")
      (node (ref "C42") (pin "2") (pintype "passive"))
      (node (ref "IC8") (pin "17") (pinfunction "OUT2_17") (pintype "passive"))
      (node (ref "LOW1") (pin "18") (pinfunction "18_18") (pintype "passive"))
      (node (ref "R136") (pin "2") (pintype "passive"))
    )
    (net (code "16") (name "/BUZZER_PWR_EN") (class "Default")
      (node (ref "CN3") (pin "22") (pinfunction "22_22") (pintype "passive"))
      (node (ref "R124") (pin "2") (pintype "passive"))
      (node (ref "R134") (pin "2") (pintype "passive"))
    )
    (net (code "17") (name "/CAN_H") (class "Default")
      (node (ref "CN4") (pin "6") (pinfunction "6_6") (pintype "passive"))
      (node (ref "LOW2") (pin "2") (pinfunction "2_2") (pintype "passive"))
      (node (ref "U6") (pin "1") (pinfunction "1_1") (pintype "passive"))
    )
    (net (code "18") (name "/CAN_L") (class "Default")
      (node (ref "CN4") (pin "7") (pinfunction "7_7") (pintype "passive"))
      (node (ref "LOW2") (pin "1") (pinfunction "1_1") (pintype "passive"))
      (node (ref "U6") (pin "2") (pinfunction "2_2") (pintype "passive"))
    )
    (net (code "19") (name "/DCDC_CTRL") (class "Default")
      (node (ref "HIGH1") (pin "6") (pinfunction "6_6") (pintype "passive"))
      (node (ref "K1") (pin "5") (pinfunction "COIL_1_5") (pintype "passive"))
    )
    (net (code "20") (name "/DCDC_IN") (class "Default")
      (node (ref "DCDC_IN1") (pin "1") (pinfunction "1_1") (pintype "passive"))
      (node (ref "DCDC_IN1") (pin "2") (pinfunction "2_2") (pintype "passive"))
      (node (ref "DCDC_IN1") (pin "3") (pinfunction "3_3") (pintype "passive"))
      (node (ref "DCDC_IN1") (pin "4") (pinfunction "4_4") (pintype "passive"))
      (node (ref "FU3") (pin "2") (pintype "passive"))
    )
    (net (code "21") (name "/DRS_CTRL") (class "Default")
      (node (ref "CN4") (pin "9") (pinfunction "9_9") (pintype "passive"))
      (node (ref "LOW2") (pin "3") (pinfunction "3_3") (pintype "passive"))
    )
    (net (code "22") (name "/DRS_PWR_8V") (class "Default")
      (node (ref "C57") (pin "1") (pinfunction "+_1") (pintype "passive"))
      (node (ref "HIGH1") (pin "1") (pinfunction "1_1") (pintype "passive"))
      (node (ref "L2") (pin "2") (pinfunction "2_2") (pintype "passive"))
      (node (ref "R169") (pin "2") (pintype "passive"))
    )
    (net (code "23") (name "/DRS_PWR_8V_EN") (class "Default")
      (node (ref "CN4") (pin "21") (pinfunction "21_21") (pintype "passive"))
      (node (ref "R17") (pin "2") (pintype "passive"))
      (node (ref "R8") (pin "2") (pintype "passive"))
    )
    (net (code "24") (name "/DRS_PWR_8V_a") (class "Default")
      (node (ref "C3") (pin "2") (pintype "passive"))
      (node (ref "C58") (pin "2") (pintype "passive"))
      (node (ref "IC1") (pin "10") (pinfunction "OUT1_3_10") (pintype "passive"))
      (node (ref "IC1") (pin "8") (pinfunction "OUT1_1_8") (pintype "passive"))
      (node (ref "IC1") (pin "9") (pinfunction "OUT1_2_9") (pintype "passive"))
      (node (ref "IC12") (pin "7") (pinfunction "VIN_7") (pintype "passive"))
      (node (ref "R22") (pin "2") (pintype "passive"))
    )
    (net (code "25") (name "/DSBD_PWR") (class "Default")
      (node (ref "C12") (pin "2") (pintype "passive"))
      (node (ref "IC2") (pin "13") (pinfunction "OUT3_13") (pintype "passive"))
      (node (ref "LOW1") (pin "5") (pinfunction "5_5") (pintype "passive"))
      (node (ref "R52") (pin "2") (pintype "passive"))
    )
    (net (code "26") (name "/DSBD_PWR_EN") (class "Default")
      (node (ref "CN3") (pin "8") (pinfunction "8_8") (pintype "passive"))
      (node (ref "R27") (pin "2") (pintype "passive"))
      (node (ref "R45") (pin "2") (pintype "passive"))
    )
    (net (code "27") (name "/EC800M_PWR_8V_EN") (class "Default")
      (node (ref "CN3") (pin "12") (pinfunction "12_12") (pintype "passive"))
      (node (ref "R160") (pin "2") (pintype "passive"))
      (node (ref "R166") (pin "2") (pintype "passive"))
    )
    (net (code "28") (name "/EC800M_PWR_8V_a") (class "Default")
      (node (ref "C48") (pin "2") (pintype "passive"))
      (node (ref "C56") (pin "2") (pintype "passive"))
      (node (ref "IC11") (pin "24") (pinfunction "OUT0_24") (pintype "passive"))
      (node (ref "IC9") (pin "7") (pinfunction "VIN_7") (pintype "passive"))
      (node (ref "R165") (pin "2") (pintype "passive"))
    )
    (net (code "29") (name "/ENERGE_METER_PWR") (class "Default")
      (node (ref "C59") (pin "2") (pintype "passive"))
      (node (ref "IC11") (pin "20") (pinfunction "OUT1_20") (pintype "passive"))
      (node (ref "LOW1") (pin "9") (pinfunction "9_9") (pintype "passive"))
      (node (ref "R170") (pin "2") (pintype "passive"))
    )
    (net (code "30") (name "/ENERGE_METER_PWR_EN") (class "Default")
      (node (ref "CN3") (pin "13") (pinfunction "13_13") (pintype "passive"))
      (node (ref "R159") (pin "2") (pintype "passive"))
      (node (ref "R168") (pin "2") (pintype "passive"))
    )
    (net (code "31") (name "/FAN1_PWR") (class "Default")
      (node (ref "C23") (pin "2") (pintype "passive"))
      (node (ref "HIGH1") (pin "14") (pinfunction "14_14") (pintype "passive"))
      (node (ref "IC5") (pin "10") (pinfunction "OUT1_3_10") (pintype "passive"))
      (node (ref "IC5") (pin "8") (pinfunction "OUT1_1_8") (pintype "passive"))
      (node (ref "IC5") (pin "9") (pinfunction "OUT1_2_9") (pintype "passive"))
      (node (ref "R83") (pin "2") (pintype "passive"))
    )
    (net (code "32") (name "/FAN1_PWR_EN") (class "Default")
      (node (ref "CN4") (pin "29") (pinfunction "29_29") (pintype "passive"))
      (node (ref "R70") (pin "2") (pintype "passive"))
      (node (ref "R78") (pin "2") (pintype "passive"))
    )
    (net (code "33") (name "/FAN2_PWR") (class "Default")
      (node (ref "C33") (pin "2") (pintype "passive"))
      (node (ref "HIGH1") (pin "15") (pinfunction "15_15") (pintype "passive"))
      (node (ref "IC7") (pin "10") (pinfunction "OUT1_3_10") (pintype "passive"))
      (node (ref "IC7") (pin "8") (pinfunction "OUT1_1_8") (pintype "passive"))
      (node (ref "IC7") (pin "9") (pinfunction "OUT1_2_9") (pintype "passive"))
      (node (ref "R113") (pin "2") (pintype "passive"))
    )
    (net (code "34") (name "/FAN2_PWR_EN") (class "Default")
      (node (ref "CN4") (pin "33") (pinfunction "33_33") (pintype "passive"))
      (node (ref "R104") (pin "2") (pintype "passive"))
      (node (ref "R111") (pin "2") (pintype "passive"))
    )
    (net (code "35") (name "/FAN3_PWR") (class "Default")
      (node (ref "C32") (pin "2") (pintype "passive"))
      (node (ref "HIGH1") (pin "16") (pinfunction "16_16") (pintype "passive"))
      (node (ref "IC7") (pin "12") (pinfunction "OUT0_1_12") (pintype "passive"))
      (node (ref "IC7") (pin "13") (pinfunction "OUT0_2_13") (pintype "passive"))
      (node (ref "IC7") (pin "14") (pinfunction "OUT0_3_14") (pintype "passive"))
      (node (ref "R110") (pin "2") (pintype "passive"))
    )
    (net (code "36") (name "/FAN3_PWR_EN") (class "Default")
      (node (ref "CN4") (pin "36") (pinfunction "36_36") (pintype "passive"))
      (node (ref "R105") (pin "2") (pintype "passive"))
      (node (ref "R109") (pin "2") (pintype "passive"))
    )
    (net (code "37") (name "/FIREON_PWR") (class "Default")
      (node (ref "C10") (pin "2") (pintype "passive"))
      (node (ref "IC2") (pin "17") (pinfunction "OUT2_17") (pintype "passive"))
      (node (ref "LOW1") (pin "4") (pinfunction "4_4") (pintype "passive"))
      (node (ref "R46") (pin "2") (pintype "passive"))
    )
    (net (code "38") (name "/FIREON_PWR_EN") (class "Default")
      (node (ref "CN3") (pin "7") (pinfunction "7_7") (pintype "passive"))
      (node (ref "R28") (pin "2") (pintype "passive"))
      (node (ref "R42") (pin "2") (pintype "passive"))
      (node (ref "R50") (pin "1") (pintype "passive"))
    )
    (net (code "39") (name "/GLVMS-") (class "Default")
      (node (ref "C1") (pin "1") (pintype "passive"))
      (node (ref "C16") (pin "1") (pintype "passive"))
      (node (ref "C28") (pin "1") (pintype "passive"))
      (node (ref "C35") (pin "1") (pintype "passive"))
      (node (ref "C43") (pin "1") (pintype "passive"))
      (node (ref "C5") (pin "1") (pintype "passive"))
      (node (ref "C52") (pin "1") (pintype "passive"))
      (node (ref "C6") (pin "1") (pintype "passive"))
      (node (ref "GLVMS-1") (pin "1") (pinfunction "1_1") (pintype "passive"))
      (node (ref "GLVMS-1") (pin "2") (pinfunction "2_2") (pintype "passive"))
      (node (ref "GLVMS-1") (pin "3") (pinfunction "3_3") (pintype "passive"))
      (node (ref "GLVMS-1") (pin "4") (pinfunction "4_4") (pintype "passive"))
      (node (ref "IC1") (pin "15") (pinfunction "VS_15") (pintype "passive"))
      (node (ref "IC10") (pin "15") (pinfunction "VS_15") (pintype "passive"))
      (node (ref "IC11") (pin "25") (pinfunction "VS_25") (pintype "passive"))
      (node (ref "IC2") (pin "25") (pinfunction "VS_25") (pintype "passive"))
      (node (ref "IC3") (pin "15") (pinfunction "VS_15") (pintype "passive"))
      (node (ref "IC5") (pin "15") (pinfunction "VS_15") (pintype "passive"))
      (node (ref "IC7") (pin "15") (pinfunction "VS_15") (pintype "passive"))
      (node (ref "IC8") (pin "25") (pinfunction "VS_25") (pintype "passive"))
      (node (ref "K1") (pin "6") (pinfunction "COIL_2_6") (pintype "passive"))
      (node (ref "R1") (pin "1") (pintype "passive"))
      (node (ref "R1") (pin "2") (pintype "passive"))
      (node (ref "R10") (pin "2") (pintype "passive"))
      (node (ref "R114") (pin "1") (pintype "passive"))
      (node (ref "R25") (pin "1") (pintype "passive"))
      (node (ref "R25") (pin "2") (pintype "passive"))
      (node (ref "R56") (pin "1") (pintype "passive"))
      (node (ref "R56") (pin "2") (pintype "passive"))
      (node (ref "ZDB1") (pin "2") (pintype "passive"))
      (node (ref "ZDB10") (pin "2") (pintype "passive"))
      (node (ref "ZDB2") (pin "2") (pintype "passive"))
      (node (ref "ZDB3") (pin "2") (pintype "passive"))
      (node (ref "ZDB5") (pin "2") (pintype "passive"))
      (node (ref "ZDB7") (pin "2") (pintype "passive"))
      (node (ref "ZDB8") (pin "2") (pintype "passive"))
      (node (ref "ZDB9") (pin "2") (pintype "passive"))
    )
    (net (code "40") (name "/GLVMS-1") (class "Default")
      (node (ref "C25") (pin "1") (pintype "passive"))
      (node (ref "IC6") (pin "25") (pinfunction "VS_25") (pintype "passive"))
      (node (ref "R114") (pin "2") (pintype "passive"))
      (node (ref "R86") (pin "1") (pintype "passive"))
      (node (ref "ZDB6") (pin "2") (pintype "passive"))
    )
    (net (code "41") (name "/GLVMS-2") (class "Default")
      (node (ref "C15") (pin "1") (pintype "passive"))
      (node (ref "IC4") (pin "25") (pinfunction "VS_25") (pintype "passive"))
      (node (ref "R86") (pin "2") (pintype "passive"))
      (node (ref "ZDB4") (pin "2") (pintype "passive"))
    )
    (net (code "42") (name "/GLVMS_OFF") (class "Default")
      (node (ref "CN4") (pin "3") (pinfunction "3_3") (pintype "passive"))
      (node (ref "LED2") (pin "2") (pintype "passive"))
      (node (ref "OP2") (pin "3") (pinfunction "8_3") (pintype "passive"))
      (node (ref "R18") (pin "2") (pintype "passive"))
    )
    (net (code "43") (name "/H1_24V_Backup") (class "Default")
      (node (ref "C9") (pin "2") (pintype "passive"))
      (node (ref "HIGH1") (pin "4") (pinfunction "4_4") (pintype "passive"))
      (node (ref "IC3") (pin "12") (pinfunction "OUT0_1_12") (pintype "passive"))
      (node (ref "IC3") (pin "13") (pinfunction "OUT0_2_13") (pintype "passive"))
      (node (ref "IC3") (pin "14") (pinfunction "OUT0_3_14") (pintype "passive"))
      (node (ref "R43") (pin "2") (pintype "passive"))
    )
    (net (code "44") (name "/H1_24V_Backup_EN") (class "Default")
      (node (ref "CN4") (pin "28") (pinfunction "28_28") (pintype "passive"))
      (node (ref "R37") (pin "2") (pintype "passive"))
      (node (ref "R41") (pin "2") (pintype "passive"))
    )
    (net (code "45") (name "/H1_current_IN10") (class "Default")
      (node (ref "C4") (pin "2") (pintype "passive"))
      (node (ref "CN4") (pin "23") (pinfunction "23_23") (pintype "passive"))
      (node (ref "R21") (pin "2") (pintype "passive"))
    )
    (net (code "46") (name "/H1_select") (class "Default")
      (node (ref "CN4") (pin "22") (pinfunction "22_22") (pintype "passive"))
      (node (ref "R11") (pin "2") (pintype "passive"))
    )
    (net (code "47") (name "/H2_24V_Backup") (class "Default")
      (node (ref "C20") (pin "2") (pintype "passive"))
      (node (ref "HIGH1") (pin "5") (pinfunction "5_5") (pintype "passive"))
      (node (ref "IC5") (pin "12") (pinfunction "OUT0_1_12") (pintype "passive"))
      (node (ref "IC5") (pin "13") (pinfunction "OUT0_2_13") (pintype "passive"))
      (node (ref "IC5") (pin "14") (pinfunction "OUT0_3_14") (pintype "passive"))
      (node (ref "R77") (pin "2") (pintype "passive"))
    )
    (net (code "48") (name "/H2_24V_Backup_EN") (class "Default")
      (node (ref "CN4") (pin "32") (pinfunction "32_32") (pintype "passive"))
      (node (ref "R71") (pin "2") (pintype "passive"))
      (node (ref "R76") (pin "2") (pintype "passive"))
    )
    (net (code "49") (name "/H2_current_IN11") (class "Default")
      (node (ref "C14") (pin "2") (pintype "passive"))
      (node (ref "CN4") (pin "27") (pinfunction "27_27") (pintype "passive"))
      (node (ref "R48") (pin "2") (pintype "passive"))
    )
    (net (code "50") (name "/H2_select") (class "Default")
      (node (ref "CN4") (pin "26") (pinfunction "26_26") (pintype "passive"))
      (node (ref "R38") (pin "2") (pintype "passive"))
    )
    (net (code "51") (name "/H3_24V_Backup") (class "Default")
      (node (ref "C49") (pin "2") (pintype "passive"))
      (node (ref "HIGH1") (pin "18") (pinfunction "18_18") (pintype "passive"))
      (node (ref "IC10") (pin "12") (pinfunction "OUT0_1_12") (pintype "passive"))
      (node (ref "IC10") (pin "13") (pinfunction "OUT0_2_13") (pintype "passive"))
      (node (ref "IC10") (pin "14") (pinfunction "OUT0_3_14") (pintype "passive"))
      (node (ref "R150") (pin "2") (pintype "passive"))
    )
    (net (code "52") (name "/H3_24V_Backup_EN") (class "Default")
      (node (ref "CN4") (pin "40") (pinfunction "40_40") (pintype "passive"))
      (node (ref "R146") (pin "2") (pintype "passive"))
      (node (ref "R149") (pin "2") (pintype "passive"))
    )
    (net (code "53") (name "/H3_current_IN12") (class "Default")
      (node (ref "C24") (pin "2") (pintype "passive"))
      (node (ref "CN4") (pin "31") (pinfunction "31_31") (pintype "passive"))
      (node (ref "R82") (pin "2") (pintype "passive"))
    )
    (net (code "54") (name "/H3_select") (class "Default")
      (node (ref "CN4") (pin "30") (pinfunction "30_30") (pintype "passive"))
      (node (ref "R73") (pin "2") (pintype "passive"))
    )
    (net (code "55") (name "/H4_current_IN13") (class "Default")
      (node (ref "C34") (pin "2") (pintype "passive"))
      (node (ref "CN4") (pin "35") (pinfunction "35_35") (pintype "passive"))
      (node (ref "R112") (pin "2") (pintype "passive"))
    )
    (net (code "56") (name "/H4_select") (class "Default")
      (node (ref "CN4") (pin "34") (pinfunction "34_34") (pintype "passive"))
      (node (ref "R107") (pin "2") (pintype "passive"))
    )
    (net (code "57") (name "/H5_current_IN1") (class "Default")
      (node (ref "C54") (pin "2") (pintype "passive"))
      (node (ref "CN4") (pin "39") (pinfunction "39_39") (pintype "passive"))
      (node (ref "R153") (pin "2") (pintype "passive"))
    )
    (net (code "58") (name "/H5_select") (class "Default")
      (node (ref "CN4") (pin "38") (pinfunction "38_38") (pintype "passive"))
      (node (ref "R148") (pin "2") (pintype "passive"))
    )
    (net (code "59") (name "/IIC1_SCL_PB8") (class "Default")
      (node (ref "*1") (pin "2") (pinfunction "2_2") (pintype "passive"))
      (node (ref "CN4") (pin "2") (pinfunction "2_2") (pintype "passive"))
    )
    (net (code "60") (name "/IIC1_SDA_PB9") (class "Default")
      (node (ref "*1") (pin "1") (pinfunction "1_1") (pintype "passive"))
      (node (ref "CN4") (pin "1") (pinfunction "1_1") (pintype "passive"))
    )
    (net (code "61") (name "/IL+_PWR") (class "Default")
      (node (ref "C53") (pin "2") (pintype "passive"))
      (node (ref "HIGH1") (pin "17") (pinfunction "17_17") (pintype "passive"))
      (node (ref "IC10") (pin "10") (pinfunction "OUT1_3_10") (pintype "passive"))
      (node (ref "IC10") (pin "8") (pinfunction "OUT1_1_8") (pintype "passive"))
      (node (ref "IC10") (pin "9") (pinfunction "OUT1_2_9") (pintype "passive"))
      (node (ref "R154") (pin "2") (pintype "passive"))
    )
    (net (code "62") (name "/IL+_PWR_EN") (class "Default")
      (node (ref "CN4") (pin "37") (pinfunction "37_37") (pintype "passive"))
      (node (ref "R145") (pin "2") (pintype "passive"))
      (node (ref "R151") (pin "2") (pintype "passive"))
    )
    (net (code "63") (name "/L1_5V_Backup") (class "Default")
      (node (ref "LOW1") (pin "1") (pinfunction "1_1") (pintype "passive"))
      (node (ref "R142") (pin "2") (pintype "passive"))
      (node (ref "R147") (pin "2") (pintype "passive"))
    )
    (net (code "64") (name "/L1_5V_Backup_EN") (class "Default")
      (node (ref "CN3") (pin "2") (pinfunction "2_2") (pintype "passive"))
      (node (ref "R30") (pin "2") (pintype "passive"))
      (node (ref "R35") (pin "2") (pintype "passive"))
    )
    (net (code "65") (name "/L1_5V_Backup_a") (class "Default")
      (node (ref "C51") (pin "2") (pintype "passive"))
      (node (ref "C7") (pin "2") (pintype "passive"))
      (node (ref "IC2") (pin "24") (pinfunction "OUT0_24") (pintype "passive"))
      (node (ref "R142") (pin "1") (pintype "passive"))
      (node (ref "R33") (pin "2") (pintype "passive"))
      (node (ref "U4") (pin "1") (pinfunction "+Vin_1") (pintype "passive"))
      (node (ref "U4") (pin "6") (pinfunction "Ctrl_6") (pintype "passive"))
    )
    (net (code "66") (name "/L1_24V_Backup") (class "Default")
      (node (ref "C18") (pin "2") (pintype "passive"))
      (node (ref "CN1") (pin "1") (pinfunction "1_1") (pintype "passive"))
      (node (ref "IC4") (pin "20") (pinfunction "OUT1_20") (pintype "passive"))
      (node (ref "LOW1") (pin "15") (pinfunction "15_15") (pintype "passive"))
      (node (ref "R67") (pin "2") (pintype "passive"))
    )
    (net (code "67") (name "/L1_24V_Backup_EN") (class "Default")
      (node (ref "CN3") (pin "39") (pinfunction "39_39") (pintype "passive"))
      (node (ref "R60") (pin "2") (pintype "passive"))
      (node (ref "R66") (pin "2") (pintype "passive"))
    )
    (net (code "68") (name "/L1_current_IN3") (class "Default")
      (node (ref "C13") (pin "2") (pintype "passive"))
      (node (ref "CN3") (pin "5") (pinfunction "5_5") (pintype "passive"))
      (node (ref "R47") (pin "2") (pintype "passive"))
    )
    (net (code "69") (name "/L1_select0") (class "Default")
      (node (ref "CN3") (pin "6") (pinfunction "6_6") (pintype "passive"))
      (node (ref "R31") (pin "2") (pintype "passive"))
    )
    (net (code "70") (name "/L1_select1") (class "Default")
      (node (ref "CN3") (pin "9") (pinfunction "9_9") (pintype "passive"))
      (node (ref "R32") (pin "2") (pintype "passive"))
    )
    (net (code "71") (name "/L2_5V_Backup") (class "Default")
      (node (ref "LOW1") (pin "12") (pinfunction "12_12") (pintype "passive"))
      (node (ref "R164") (pin "2") (pintype "passive"))
      (node (ref "R167") (pin "2") (pintype "passive"))
    )
    (net (code "72") (name "/L2_5V_Backup_EN") (class "Default")
      (node (ref "CN3") (pin "33") (pinfunction "33_33") (pintype "passive"))
      (node (ref "R91") (pin "2") (pintype "passive"))
      (node (ref "R95") (pin "2") (pintype "passive"))
    )
    (net (code "73") (name "/L2_5V_Backupa_a") (class "Default")
      (node (ref "C26") (pin "2") (pintype "passive"))
      (node (ref "C62") (pin "2") (pintype "passive"))
      (node (ref "IC6") (pin "24") (pinfunction "OUT0_24") (pintype "passive"))
      (node (ref "R164") (pin "1") (pintype "passive"))
      (node (ref "R94") (pin "2") (pintype "passive"))
      (node (ref "U7") (pin "1") (pinfunction "+Vin_1") (pintype "passive"))
      (node (ref "U7") (pin "6") (pinfunction "Ctrl_6") (pintype "passive"))
    )
    (net (code "74") (name "/L2_current_IN4") (class "Default")
      (node (ref "C22") (pin "2") (pintype "passive"))
      (node (ref "CN3") (pin "38") (pinfunction "38_38") (pintype "passive"))
      (node (ref "R75") (pin "2") (pintype "passive"))
    )
    (net (code "75") (name "/L2_select0") (class "Default")
      (node (ref "CN3") (pin "37") (pinfunction "37_37") (pintype "passive"))
      (node (ref "R62") (pin "2") (pintype "passive"))
    )
    (net (code "76") (name "/L2_select1") (class "Default")
      (node (ref "CN3") (pin "34") (pinfunction "34_34") (pintype "passive"))
      (node (ref "R63") (pin "2") (pintype "passive"))
    )
    (net (code "77") (name "/L3_5V_Backup") (class "Default")
      (node (ref "LOW1") (pin "11") (pinfunction "11_11") (pintype "passive"))
      (node (ref "R118") (pin "2") (pintype "passive"))
      (node (ref "R122") (pin "2") (pintype "passive"))
    )
    (net (code "78") (name "/L3_5V_Backup_EN") (class "Default")
      (node (ref "CN3") (pin "10") (pinfunction "10_10") (pintype "passive"))
      (node (ref "R61") (pin "2") (pintype "passive"))
      (node (ref "R65") (pin "2") (pintype "passive"))
    )
    (net (code "79") (name "/L3_5V_Backup_a") (class "Default")
      (node (ref "C17") (pin "2") (pintype "passive"))
      (node (ref "C40") (pin "2") (pintype "passive"))
      (node (ref "IC4") (pin "24") (pinfunction "OUT0_24") (pintype "passive"))
      (node (ref "R118") (pin "1") (pintype "passive"))
      (node (ref "R64") (pin "2") (pintype "passive"))
      (node (ref "U3") (pin "1") (pinfunction "+Vin_1") (pintype "passive"))
      (node (ref "U3") (pin "6") (pinfunction "Ctrl_6") (pintype "passive"))
    )
    (net (code "80") (name "/L3_current_IN5") (class "Default")
      (node (ref "C31") (pin "2") (pintype "passive"))
      (node (ref "CN3") (pin "31") (pinfunction "31_31") (pintype "passive"))
      (node (ref "R101") (pin "2") (pintype "passive"))
    )
    (net (code "81") (name "/L3_select0") (class "Default")
      (node (ref "CN3") (pin "30") (pinfunction "30_30") (pintype "passive"))
      (node (ref "R92") (pin "2") (pintype "passive"))
    )
    (net (code "82") (name "/L3_select1") (class "Default")
      (node (ref "CN3") (pin "27") (pinfunction "27_27") (pintype "passive"))
      (node (ref "R93") (pin "2") (pintype "passive"))
    )
    (net (code "83") (name "/L4_5V_Backup") (class "Default")
      (node (ref "LOW2") (pin "14") (pinfunction "14_14") (pintype "passive"))
      (node (ref "LOW2") (pin "15") (pinfunction "15_15") (pintype "passive"))
      (node (ref "LOW2") (pin "16") (pinfunction "16_16") (pintype "passive"))
      (node (ref "LOW2") (pin "17") (pinfunction "17_17") (pintype "passive"))
      (node (ref "LOW2") (pin "18") (pinfunction "18_18") (pintype "passive"))
      (node (ref "R116") (pin "2") (pintype "passive"))
      (node (ref "R121") (pin "2") (pintype "passive"))
    )
    (net (code "84") (name "/L4_5V_Backup_EN") (class "Default")
      (node (ref "CN3") (pin "26") (pinfunction "26_26") (pintype "passive"))
      (node (ref "R126") (pin "2") (pintype "passive"))
      (node (ref "R131") (pin "2") (pintype "passive"))
    )
    (net (code "85") (name "/L4_5V_Backup_a") (class "Default")
      (node (ref "C36") (pin "2") (pintype "passive"))
      (node (ref "C39") (pin "2") (pintype "passive"))
      (node (ref "IC8") (pin "24") (pinfunction "OUT0_24") (pintype "passive"))
      (node (ref "R116") (pin "1") (pintype "passive"))
      (node (ref "R129") (pin "2") (pintype "passive"))
      (node (ref "U2") (pin "1") (pinfunction "+Vin_1") (pintype "passive"))
      (node (ref "U2") (pin "6") (pinfunction "Ctrl_6") (pintype "passive"))
    )
    (net (code "86") (name "/L4_current_IN6") (class "Default")
      (node (ref "C46") (pin "2") (pintype "passive"))
      (node (ref "CN3") (pin "24") (pinfunction "24_24") (pintype "passive"))
      (node (ref "R137") (pin "2") (pintype "passive"))
    )
    (net (code "87") (name "/L4_select0") (class "Default")
      (node (ref "CN3") (pin "23") (pinfunction "23_23") (pintype "passive"))
      (node (ref "R127") (pin "2") (pintype "passive"))
    )
    (net (code "88") (name "/L4_select1") (class "Default")
      (node (ref "CN3") (pin "20") (pinfunction "20_20") (pintype "passive"))
      (node (ref "R128") (pin "2") (pintype "passive"))
    )
    (net (code "89") (name "/L5_current_IN7") (class "Default")
      (node (ref "C64") (pin "2") (pintype "passive"))
      (node (ref "CN3") (pin "14") (pinfunction "14_14") (pintype "passive"))
      (node (ref "R174") (pin "2") (pintype "passive"))
    )
    (net (code "90") (name "/L5_select0") (class "Default")
      (node (ref "CN3") (pin "15") (pinfunction "15_15") (pintype "passive"))
      (node (ref "R161") (pin "2") (pintype "passive"))
    )
    (net (code "91") (name "/L5_select1") (class "Default")
      (node (ref "CN3") (pin "18") (pinfunction "18_18") (pintype "passive"))
      (node (ref "R163") (pin "2") (pintype "passive"))
    )
    (net (code "92") (name "/LED_PC12") (class "Default")
      (node (ref "CN3") (pin "40") (pinfunction "40_40") (pintype "passive"))
      (node (ref "LED3") (pin "1") (pintype "passive"))
    )
    (net (code "93") (name "/LOGGER_PWR") (class "Default")
      (node (ref "C45") (pin "2") (pintype "passive"))
      (node (ref "IC8") (pin "13") (pinfunction "OUT3_13") (pintype "passive"))
      (node (ref "LOW1") (pin "19") (pinfunction "19_19") (pintype "passive"))
      (node (ref "R140") (pin "2") (pintype "passive"))
    )
    (net (code "94") (name "/LOGGER_PWR_EN") (class "Default")
      (node (ref "CN3") (pin "11") (pinfunction "11_11") (pintype "passive"))
      (node (ref "R123") (pin "2") (pintype "passive"))
      (node (ref "R135") (pin "2") (pintype "passive"))
    )
    (net (code "95") (name "/MCU_UBR") (class "Default")
      (node (ref "C63") (pin "2") (pintype "passive"))
      (node (ref "IC11") (pin "13") (pinfunction "OUT3_13") (pintype "passive"))
      (node (ref "LOW1") (pin "10") (pinfunction "10_10") (pintype "passive"))
      (node (ref "R177") (pin "2") (pintype "passive"))
    )
    (net (code "96") (name "/MCU_UBR_EN") (class "Default")
      (node (ref "CN3") (pin "17") (pinfunction "17_17") (pintype "passive"))
      (node (ref "R157") (pin "2") (pintype "passive"))
      (node (ref "R172") (pin "2") (pintype "passive"))
    )
    (net (code "97") (name "/NRST") (class "Default")
      (node (ref "CN4") (pin "8") (pinfunction "8_8") (pintype "passive"))
      (node (ref "R130") (pin "1") (pintype "passive"))
    )
    (net (code "98") (name "/PUMP_CTRL") (class "Default")
      (node (ref "LOW2") (pin "11") (pinfunction "11_11") (pintype "passive+no_connect"))
    )
    (net (code "99") (name "/PUMP_PWR") (class "Default")
      (node (ref "C11") (pin "2") (pintype "passive"))
      (node (ref "HIGH1") (pin "13") (pinfunction "13_13") (pintype "passive"))
      (node (ref "IC3") (pin "10") (pinfunction "OUT1_3_10") (pintype "passive"))
      (node (ref "IC3") (pin "8") (pinfunction "OUT1_1_8") (pintype "passive"))
      (node (ref "IC3") (pin "9") (pinfunction "OUT1_2_9") (pintype "passive"))
      (node (ref "R49") (pin "2") (pintype "passive"))
    )
    (net (code "100") (name "/PUMP_PWR_EN") (class "Default")
      (node (ref "CN4") (pin "25") (pinfunction "25_25") (pintype "passive"))
      (node (ref "R36") (pin "2") (pintype "passive"))
      (node (ref "R44") (pin "2") (pintype "passive"))
    )
    (net (code "101") (name "/SWCLK") (class "Default")
      (node (ref "CN4") (pin "12") (pinfunction "12_12") (pintype "passive"))
      (node (ref "U5") (pin "10") (pinfunction "10_10") (pintype "passive"))
    )
    (net (code "102") (name "/SWDIO") (class "Default")
      (node (ref "CN4") (pin "13") (pinfunction "13_13") (pintype "passive"))
      (node (ref "U5") (pin "8") (pinfunction "8_8") (pintype "passive"))
    )
    (net (code "103") (name "/TAILLIGHT_PWR") (class "Default")
      (node (ref "C8") (pin "2") (pintype "passive"))
      (node (ref "IC2") (pin "20") (pinfunction "OUT1_20") (pintype "passive"))
      (node (ref "LOW1") (pin "14") (pinfunction "14_14") (pintype "passive"))
      (node (ref "R40") (pin "2") (pintype "passive"))
    )
    (net (code "104") (name "/TAILLIGHT_PWR_EN") (class "Default")
      (node (ref "CN3") (pin "3") (pinfunction "3_3") (pintype "passive"))
      (node (ref "R29") (pin "2") (pintype "passive"))
      (node (ref "R39") (pin "2") (pintype "passive"))
    )
    (net (code "105") (name "/TSALR_PWR") (class "Default")
      (node (ref "C41") (pin "2") (pintype "passive"))
      (node (ref "IC8") (pin "20") (pinfunction "OUT1_20") (pintype "passive"))
      (node (ref "LOW1") (pin "8") (pinfunction "8_8") (pintype "passive"))
      (node (ref "R133") (pin "2") (pintype "passive"))
    )
    (net (code "106") (name "/TSALR_PWR_EN") (class "Default")
      (node (ref "CN3") (pin "25") (pinfunction "25_25") (pintype "passive"))
      (node (ref "R125") (pin "2") (pintype "passive"))
      (node (ref "R132") (pin "2") (pintype "passive"))
    )
    (net (code "107") (name "/Temperature_PWR") (class "Default")
      (node (ref "C27") (pin "2") (pintype "passive"))
      (node (ref "IC6") (pin "20") (pinfunction "OUT1_20") (pintype "passive"))
      (node (ref "LOW2") (pin "5") (pinfunction "5_5") (pintype "passive"))
      (node (ref "LOW2") (pin "6") (pinfunction "6_6") (pintype "passive"))
      (node (ref "LOW2") (pin "7") (pinfunction "7_7") (pintype "passive"))
      (node (ref "LOW2") (pin "8") (pinfunction "8_8") (pintype "passive"))
      (node (ref "LOW2") (pin "9") (pinfunction "9_9") (pintype "passive"))
      (node (ref "R97") (pin "2") (pintype "passive"))
    )
    (net (code "108") (name "/Temperature_PWR_EN") (class "Default")
      (node (ref "CN3") (pin "32") (pinfunction "32_32") (pintype "passive"))
      (node (ref "R90") (pin "2") (pintype "passive"))
      (node (ref "R96") (pin "2") (pintype "passive"))
    )
    (net (code "109") (name "/USART1_RX") (class "Default")
      (node (ref "CN4") (pin "11") (pinfunction "11_11") (pintype "passive"))
      (node (ref "U5") (pin "7") (pinfunction "7_7") (pintype "passive"))
    )
    (net (code "110") (name "/USART1_TX") (class "Default")
      (node (ref "CN4") (pin "10") (pinfunction "10_10") (pintype "passive"))
      (node (ref "U5") (pin "9") (pinfunction "9_9") (pintype "passive"))
    )
    (net (code "111") (name "/USART2_RX") (class "Default")
      (node (ref "CN4") (pin "16") (pinfunction "16_16") (pintype "passive"))
      (node (ref "IC13") (pin "5") (pinfunction "M_T_5") (pintype "passive"))
    )
    (net (code "112") (name "/USART2_TX") (class "Default")
      (node (ref "CN4") (pin "17") (pinfunction "17_17") (pintype "passive"))
      (node (ref "IC13") (pin "6") (pinfunction "M_R_6") (pintype "passive"))
    )
    (net (code "113") (name "/VCU_Bootloader") (class "Default")
      (node (ref "LOW2") (pin "13") (pinfunction "13_13") (pintype "passive"))
      (node (ref "R117") (pin "1") (pintype "passive"))
    )
    (net (code "114") (name "/VCU_PWR") (class "Default")
      (node (ref "C29") (pin "2") (pintype "passive"))
      (node (ref "IC6") (pin "17") (pinfunction "OUT2_17") (pintype "passive"))
      (node (ref "LOW1") (pin "7") (pinfunction "7_7") (pintype "passive"))
      (node (ref "R100") (pin "2") (pintype "passive"))
    )
    (net (code "115") (name "/VCU_PWR_EN") (class "Default")
      (node (ref "CN3") (pin "29") (pinfunction "29_29") (pintype "passive"))
      (node (ref "R89") (pin "2") (pintype "passive"))
      (node (ref "R98") (pin "2") (pintype "passive"))
    )
    (net (code "116") (name "/VCU_UBR") (class "Default")
      (node (ref "C2") (pin "2") (pintype "passive"))
      (node (ref "HIGH1") (pin "3") (pinfunction "3_3") (pintype "passive"))
      (node (ref "IC1") (pin "12") (pinfunction "OUT0_1_12") (pintype "passive"))
      (node (ref "IC1") (pin "13") (pinfunction "OUT0_2_13") (pintype "passive"))
      (node (ref "IC1") (pin "14") (pinfunction "OUT0_3_14") (pintype "passive"))
      (node (ref "R15") (pin "2") (pintype "passive"))
    )
    (net (code "117") (name "/VCU_UBR_CTRL") (class "Default")
      (node (ref "LOW2") (pin "12") (pinfunction "12_12") (pintype "passive+no_connect"))
    )
    (net (code "118") (name "/VCU_UBR_EN") (class "Default")
      (node (ref "CN4") (pin "24") (pinfunction "24_24") (pintype "passive"))
      (node (ref "R14") (pin "2") (pintype "passive"))
      (node (ref "R9") (pin "2") (pintype "passive"))
    )
    (net (code "119") (name "/active_switch_IL+") (class "Default")
      (node (ref "HIGH1") (pin "8") (pinfunction "8_8") (pintype "passive"))
      (node (ref "K2") (pin "4") (pinfunction "COM_4") (pintype "passive"))
    )
    (net (code "120") (name "/active_switch_IL-") (class "Default")
      (node (ref "HIGH1") (pin "9") (pinfunction "9_9") (pintype "passive"))
      (node (ref "K2") (pin "3") (pinfunction "NO_3") (pintype "passive"))
    )
    (net (code "121") (name "3.3V") (class "Default")
      (node (ref "CN3") (pin "1") (pinfunction "1_1") (pintype "passive"))
      (node (ref "R104") (pin "1") (pintype "passive"))
      (node (ref "R105") (pin "1") (pintype "passive"))
      (node (ref "R123") (pin "1") (pintype "passive"))
      (node (ref "R124") (pin "1") (pintype "passive"))
      (node (ref "R125") (pin "1") (pintype "passive"))
      (node (ref "R126") (pin "1") (pintype "passive"))
      (node (ref "R138") (pin "2") (pintype "passive"))
      (node (ref "R145") (pin "1") (pintype "passive"))
      (node (ref "R146") (pin "1") (pintype "passive"))
      (node (ref "R157") (pin "1") (pintype "passive"))
      (node (ref "R158") (pin "1") (pintype "passive"))
      (node (ref "R159") (pin "1") (pintype "passive"))
      (node (ref "R160") (pin "1") (pintype "passive"))
      (node (ref "R2") (pin "1") (pintype "passive"))
      (node (ref "R27") (pin "1") (pintype "passive"))
      (node (ref "R28") (pin "1") (pintype "passive"))
      (node (ref "R29") (pin "1") (pintype "passive"))
      (node (ref "R30") (pin "1") (pintype "passive"))
      (node (ref "R36") (pin "1") (pintype "passive"))
      (node (ref "R37") (pin "1") (pintype "passive"))
      (node (ref "R5") (pin "1") (pintype "passive"))
      (node (ref "R58") (pin "1") (pintype "passive"))
      (node (ref "R59") (pin "1") (pintype "passive"))
      (node (ref "R60") (pin "1") (pintype "passive"))
      (node (ref "R61") (pin "1") (pintype "passive"))
      (node (ref "R70") (pin "1") (pintype "passive"))
      (node (ref "R71") (pin "1") (pintype "passive"))
      (node (ref "R8") (pin "1") (pintype "passive"))
      (node (ref "R88") (pin "1") (pintype "passive"))
      (node (ref "R89") (pin "1") (pintype "passive"))
      (node (ref "R9") (pin "1") (pintype "passive"))
      (node (ref "R90") (pin "1") (pintype "passive"))
      (node (ref "R91") (pin "1") (pintype "passive"))
      (node (ref "U5") (pin "3") (pinfunction "3_3") (pintype "passive"))
      (node (ref "U5") (pin "4") (pinfunction "4_4") (pintype "passive"))
    )
    (net (code "122") (name "5V") (class "Default")
      (node (ref "CN4") (pin "14") (pinfunction "14_14") (pintype "passive"))
      (node (ref "CN4") (pin "15") (pinfunction "15_15") (pintype "passive"))
      (node (ref "R102") (pin "2") (pintype "passive"))
      (node (ref "R120") (pin "2") (pintype "passive"))
      (node (ref "R143") (pin "2") (pintype "passive"))
      (node (ref "R156") (pin "2") (pintype "passive"))
      (node (ref "R26") (pin "2") (pintype "passive"))
      (node (ref "R34") (pin "2") (pintype "passive"))
      (node (ref "R57") (pin "2") (pintype "passive"))
      (node (ref "R6") (pin "2") (pintype "passive"))
      (node (ref "R69") (pin "2") (pintype "passive"))
      (node (ref "R87") (pin "2") (pintype "passive"))
      (node (ref "U5") (pin "1") (pinfunction "1_1") (pintype "passive"))
      (node (ref "U5") (pin "2") (pinfunction "2_2") (pintype "passive"))
    )
    (net (code "123") (name "EC800M_PWR_8V") (class "Default")
      (node (ref "C47") (pin "1") (pinfunction "+_1") (pintype "passive"))
      (node (ref "IC13") (pin "15") (pinfunction "VIN_15") (pintype "passive"))
      (node (ref "L1") (pin "2") (pinfunction "2_2") (pintype "passive"))
      (node (ref "R144") (pin "2") (pintype "passive"))
    )
    (net (code "124") (name "GND") (class "Default")
      (node (ref "C1") (pin "2") (pintype "passive"))
      (node (ref "C10") (pin "1") (pintype "passive"))
      (node (ref "C11") (pin "1") (pintype "passive"))
      (node (ref "C12") (pin "1") (pintype "passive"))
      (node (ref "C13") (pin "1") (pintype "passive"))
      (node (ref "C14") (pin "1") (pintype "passive"))
      (node (ref "C15") (pin "2") (pintype "passive"))
      (node (ref "C16") (pin "2") (pintype "passive"))
      (node (ref "C17") (pin "1") (pintype "passive"))
      (node (ref "C18") (pin "1") (pintype "passive"))
      (node (ref "C19") (pin "1") (pintype "passive"))
      (node (ref "C2") (pin "1") (pintype "passive"))
      (node (ref "C20") (pin "1") (pintype "passive"))
      (node (ref "C21") (pin "1") (pintype "passive"))
      (node (ref "C22") (pin "1") (pintype "passive"))
      (node (ref "C23") (pin "1") (pintype "passive"))
      (node (ref "C24") (pin "1") (pintype "passive"))
      (node (ref "C25") (pin "2") (pintype "passive"))
      (node (ref "C26") (pin "1") (pintype "passive"))
      (node (ref "C27") (pin "1") (pintype "passive"))
      (node (ref "C28") (pin "2") (pintype "passive"))
      (node (ref "C29") (pin "1") (pintype "passive"))
      (node (ref "C3") (pin "1") (pintype "passive"))
      (node (ref "C30") (pin "1") (pintype "passive"))
      (node (ref "C31") (pin "1") (pintype "passive"))
      (node (ref "C32") (pin "1") (pintype "passive"))
      (node (ref "C33") (pin "1") (pintype "passive"))
      (node (ref "C34") (pin "1") (pintype "passive"))
      (node (ref "C35") (pin "2") (pintype "passive"))
      (node (ref "C36") (pin "1") (pintype "passive"))
      (node (ref "C37") (pin "1") (pintype "passive"))
      (node (ref "C38") (pin "1") (pintype "passive"))
      (node (ref "C39") (pin "1") (pintype "passive"))
      (node (ref "C4") (pin "1") (pintype "passive"))
      (node (ref "C40") (pin "1") (pintype "passive"))
      (node (ref "C41") (pin "1") (pintype "passive"))
      (node (ref "C42") (pin "1") (pintype "passive"))
      (node (ref "C43") (pin "2") (pintype "passive"))
      (node (ref "C45") (pin "1") (pintype "passive"))
      (node (ref "C46") (pin "1") (pintype "passive"))
      (node (ref "C47") (pin "2") (pinfunction "-_2") (pintype "passive"))
      (node (ref "C48") (pin "1") (pintype "passive"))
      (node (ref "C49") (pin "1") (pintype "passive"))
      (node (ref "C5") (pin "2") (pintype "passive"))
      (node (ref "C50") (pin "1") (pintype "passive"))
      (node (ref "C51") (pin "1") (pintype "passive"))
      (node (ref "C52") (pin "2") (pintype "passive"))
      (node (ref "C53") (pin "1") (pintype "passive"))
      (node (ref "C54") (pin "1") (pintype "passive"))
      (node (ref "C56") (pin "1") (pintype "passive"))
      (node (ref "C57") (pin "2") (pinfunction "-_2") (pintype "passive"))
      (node (ref "C58") (pin "1") (pintype "passive"))
      (node (ref "C59") (pin "1") (pintype "passive"))
      (node (ref "C6") (pin "2") (pintype "passive"))
      (node (ref "C60") (pin "1") (pintype "passive"))
      (node (ref "C61") (pin "1") (pintype "passive"))
      (node (ref "C62") (pin "1") (pintype "passive"))
      (node (ref "C63") (pin "1") (pintype "passive"))
      (node (ref "C64") (pin "1") (pintype "passive"))
      (node (ref "C7") (pin "1") (pintype "passive"))
      (node (ref "C8") (pin "1") (pintype "passive"))
      (node (ref "C9") (pin "1") (pintype "passive"))
      (node (ref "CN1") (pin "2") (pinfunction "2_2") (pintype "passive"))
      (node (ref "CN3") (pin "19") (pinfunction "19_19") (pintype "passive"))
      (node (ref "CN3") (pin "4") (pinfunction "4_4") (pintype "passive"))
      (node (ref "D12") (pin "2") (pinfunction "A_2") (pintype "passive"))
      (node (ref "D4") (pin "2") (pinfunction "2_2") (pintype "passive"))
      (node (ref "D9") (pin "2") (pinfunction "A_2") (pintype "passive"))
      (node (ref "GND1") (pin "1") (pinfunction "1_1") (pintype "passive"))
      (node (ref "GND1") (pin "2") (pinfunction "2_2") (pintype "passive"))
      (node (ref "GND1") (pin "3") (pinfunction "3_3") (pintype "passive"))
      (node (ref "GND1") (pin "4") (pinfunction "4_4") (pintype "passive"))
      (node (ref "IC12") (pin "6") (pinfunction "GND_6") (pintype "passive"))
      (node (ref "IC12") (pin "9") (pinfunction "EP_9") (pintype "passive"))
      (node (ref "IC13") (pin "16") (pinfunction "GND_16") (pintype "passive"))
      (node (ref "IC13") (pin "18") (pinfunction "GND_18") (pintype "passive"))
      (node (ref "IC13") (pin "9") (pinfunction "GND_9") (pintype "passive"))
      (node (ref "IC9") (pin "6") (pinfunction "GND_6") (pintype "passive"))
      (node (ref "IC9") (pin "9") (pinfunction "EP_9") (pintype "passive"))
      (node (ref "J1") (pin "-") (pinfunction "-_-") (pintype "passive"))
      (node (ref "J2") (pin "1") (pinfunction "1_1") (pintype "passive"))
      (node (ref "K2") (pin "2") (pinfunction "COIL_2_2") (pintype "passive"))
      (node (ref "LED1") (pin "1") (pintype "passive"))
      (node (ref "LED2") (pin "1") (pintype "passive"))
      (node (ref "OP1") (pin "2") (pinfunction "7_2") (pintype "passive"))
      (node (ref "OP2") (pin "2") (pinfunction "7_2") (pintype "passive"))
      (node (ref "R100") (pin "1") (pintype "passive"))
      (node (ref "R103") (pin "1") (pintype "passive"))
      (node (ref "R106") (pin "1") (pintype "passive"))
      (node (ref "R110") (pin "1") (pintype "passive"))
      (node (ref "R113") (pin "1") (pintype "passive"))
      (node (ref "R115") (pin "1") (pintype "passive"))
      (node (ref "R129") (pin "1") (pintype "passive"))
      (node (ref "R133") (pin "1") (pintype "passive"))
      (node (ref "R136") (pin "1") (pintype "passive"))
      (node (ref "R139") (pin "1") (pintype "passive"))
      (node (ref "R140") (pin "1") (pintype "passive"))
      (node (ref "R15") (pin "1") (pintype "passive"))
      (node (ref "R150") (pin "1") (pintype "passive"))
      (node (ref "R152") (pin "1") (pintype "passive"))
      (node (ref "R154") (pin "1") (pintype "passive"))
      (node (ref "R155") (pin "1") (pintype "passive"))
      (node (ref "R16") (pin "1") (pintype "passive"))
      (node (ref "R165") (pin "1") (pintype "passive"))
      (node (ref "R170") (pin "1") (pintype "passive"))
      (node (ref "R173") (pin "1") (pintype "passive"))
      (node (ref "R175") (pin "1") (pintype "passive"))
      (node (ref "R176") (pin "1") (pintype "passive"))
      (node (ref "R177") (pin "1") (pintype "passive"))
      (node (ref "R18") (pin "1") (pintype "passive"))
      (node (ref "R19") (pin "2") (pintype "passive"))
      (node (ref "R20") (pin "2") (pintype "passive"))
      (node (ref "R22") (pin "1") (pintype "passive"))
      (node (ref "R23") (pin "1") (pintype "passive"))
      (node (ref "R33") (pin "1") (pintype "passive"))
      (node (ref "R40") (pin "1") (pintype "passive"))
      (node (ref "R43") (pin "1") (pintype "passive"))
      (node (ref "R46") (pin "1") (pintype "passive"))
      (node (ref "R49") (pin "1") (pintype "passive"))
      (node (ref "R51") (pin "1") (pintype "passive"))
      (node (ref "R52") (pin "1") (pintype "passive"))
      (node (ref "R54") (pin "1") (pintype "passive"))
      (node (ref "R64") (pin "1") (pintype "passive"))
      (node (ref "R67") (pin "1") (pintype "passive"))
      (node (ref "R74") (pin "1") (pintype "passive"))
      (node (ref "R77") (pin "1") (pintype "passive"))
      (node (ref "R79") (pin "1") (pintype "passive"))
      (node (ref "R80") (pin "1") (pintype "passive"))
      (node (ref "R83") (pin "1") (pintype "passive"))
      (node (ref "R84") (pin "1") (pintype "passive"))
      (node (ref "R94") (pin "1") (pintype "passive"))
      (node (ref "R97") (pin "1") (pintype "passive"))
      (node (ref "RST1") (pin "2") (pinfunction "NO_2") (pintype "passive"))
      (node (ref "RST2") (pin "2") (pinfunction "NO_2") (pintype "passive"))
      (node (ref "RST3") (pin "2") (pinfunction "NO_2") (pintype "passive"))
      (node (ref "U1") (pin "2") (pinfunction "Anode_2") (pintype "passive"))
      (node (ref "U2") (pin "2") (pinfunction "GND_2") (pintype "passive"))
      (node (ref "U2") (pin "5") (pinfunction "GND_5") (pintype "passive"))
      (node (ref "U3") (pin "2") (pinfunction "GND_2") (pintype "passive"))
      (node (ref "U3") (pin "5") (pinfunction "GND_5") (pintype "passive"))
      (node (ref "U4") (pin "2") (pinfunction "GND_2") (pintype "passive"))
      (node (ref "U4") (pin "5") (pinfunction "GND_5") (pintype "passive"))
      (node (ref "U5") (pin "5") (pinfunction "5_5") (pintype "passive"))
      (node (ref "U5") (pin "6") (pinfunction "6_6") (pintype "passive"))
      (node (ref "U7") (pin "2") (pinfunction "GND_2") (pintype "passive"))
      (node (ref "U7") (pin "5") (pinfunction "GND_5") (pintype "passive"))
      (node (ref "ZDB1") (pin "1") (pintype "passive"))
      (node (ref "ZDB10") (pin "1") (pintype "passive"))
      (node (ref "ZDB2") (pin "1") (pintype "passive"))
      (node (ref "ZDB3") (pin "1") (pintype "passive"))
      (node (ref "ZDB4") (pin "1") (pintype "passive"))
      (node (ref "ZDB5") (pin "1") (pintype "passive"))
      (node (ref "ZDB6") (pin "1") (pintype "passive"))
      (node (ref "ZDB7") (pin "1") (pintype "passive"))
      (node (ref "ZDB8") (pin "1") (pintype "passive"))
      (node (ref "ZDB9") (pin "1") (pintype "passive"))
    )
    (net (code "125") (name "Net-(D9-K)") (class "Default")
      (node (ref "C44") (pin "2") (pintype "passive"))
      (node (ref "D9") (pin "1") (pinfunction "K_1") (pintype "passive"))
      (node (ref "IC9") (pin "8") (pinfunction "PH_8") (pintype "passive"))
      (node (ref "L1") (pin "1") (pinfunction "1_1") (pintype "passive"))
    )
    (net (code "126") (name "Net-(D12-K)") (class "Default")
      (node (ref "C55") (pin "2") (pintype "passive"))
      (node (ref "D12") (pin "1") (pinfunction "K_1") (pintype "passive"))
      (node (ref "IC12") (pin "8") (pinfunction "PH_8") (pintype "passive"))
      (node (ref "L2") (pin "1") (pinfunction "1_1") (pintype "passive"))
    )
    (net (code "127") (name "Net-(FU1-Pad2)") (class "Default")
      (node (ref "FU1") (pin "2") (pintype "passive"))
      (node (ref "FU2") (pin "1") (pintype "passive"))
      (node (ref "J2") (pin "2") (pinfunction "2_2") (pintype "passive"))
    )
    (net (code "128") (name "Net-(IC1-DEN)") (class "Default")
      (node (ref "IC1") (pin "3") (pinfunction "DEN_3") (pintype "passive"))
      (node (ref "R6") (pin "1") (pintype "passive"))
    )
    (net (code "129") (name "Net-(IC1-DSEL)") (class "Default")
      (node (ref "IC1") (pin "5") (pinfunction "DSEL_5") (pintype "passive"))
      (node (ref "R11") (pin "1") (pintype "passive"))
    )
    (net (code "130") (name "Net-(IC1-GND)") (class "Default")
      (node (ref "IC1") (pin "1") (pinfunction "GND_1") (pintype "passive"))
      (node (ref "R24") (pin "1") (pintype "passive"))
    )
    (net (code "131") (name "Net-(IC1-IN0)") (class "Default")
      (node (ref "IC1") (pin "2") (pinfunction "IN0_2") (pintype "passive"))
      (node (ref "R14") (pin "1") (pintype "passive"))
    )
    (net (code "132") (name "Net-(IC1-IN1)") (class "Default")
      (node (ref "IC1") (pin "6") (pinfunction "IN1_6") (pintype "passive"))
      (node (ref "R17") (pin "1") (pintype "passive"))
    )
    (net (code "133") (name "Net-(IC1-IS)") (class "Default")
      (node (ref "IC1") (pin "4") (pinfunction "IS_4") (pintype "passive"))
      (node (ref "R21") (pin "1") (pintype "passive"))
      (node (ref "R23") (pin "2") (pintype "passive"))
    )
    (net (code "134") (name "Net-(IC2-DEN)") (class "Default")
      (node (ref "IC2") (pin "6") (pinfunction "DEN_6") (pintype "passive"))
      (node (ref "R26") (pin "1") (pintype "passive"))
    )
    (net (code "135") (name "Net-(IC2-DSEL0)") (class "Default")
      (node (ref "IC2") (pin "8") (pinfunction "DSEL0_8") (pintype "passive"))
      (node (ref "R31") (pin "1") (pintype "passive"))
    )
    (net (code "136") (name "Net-(IC2-DSEL1)") (class "Default")
      (node (ref "IC2") (pin "11") (pinfunction "DSEL1_11") (pintype "passive"))
      (node (ref "R32") (pin "1") (pintype "passive"))
    )
    (net (code "137") (name "Net-(IC2-GND)") (class "Default")
      (node (ref "IC2") (pin "4") (pinfunction "GND_4") (pintype "passive"))
      (node (ref "R53") (pin "2") (pintype "passive"))
    )
    (net (code "138") (name "Net-(IC2-IN0)") (class "Default")
      (node (ref "IC2") (pin "2") (pinfunction "IN0_2") (pintype "passive"))
      (node (ref "R35") (pin "1") (pintype "passive"))
    )
    (net (code "139") (name "Net-(IC2-IN1)") (class "Default")
      (node (ref "IC2") (pin "5") (pinfunction "IN1_5") (pintype "passive"))
      (node (ref "R39") (pin "1") (pintype "passive"))
    )
    (net (code "140") (name "Net-(IC2-IN2)") (class "Default")
      (node (ref "IC2") (pin "9") (pinfunction "IN2_9") (pintype "passive"))
      (node (ref "R42") (pin "1") (pintype "passive"))
    )
    (net (code "141") (name "Net-(IC2-IN3)") (class "Default")
      (node (ref "IC2") (pin "10") (pinfunction "IN3_10") (pintype "passive"))
      (node (ref "R45") (pin "1") (pintype "passive"))
    )
    (net (code "142") (name "Net-(IC2-IS)") (class "Default")
      (node (ref "IC2") (pin "7") (pinfunction "IS_7") (pintype "passive"))
      (node (ref "R47") (pin "1") (pintype "passive"))
      (node (ref "R51") (pin "2") (pintype "passive"))
    )
    (net (code "143") (name "Net-(IC3-DEN)") (class "Default")
      (node (ref "IC3") (pin "3") (pinfunction "DEN_3") (pintype "passive"))
      (node (ref "R34") (pin "1") (pintype "passive"))
    )
    (net (code "144") (name "Net-(IC3-DSEL)") (class "Default")
      (node (ref "IC3") (pin "5") (pinfunction "DSEL_5") (pintype "passive"))
      (node (ref "R38") (pin "1") (pintype "passive"))
    )
    (net (code "145") (name "Net-(IC3-GND)") (class "Default")
      (node (ref "IC3") (pin "1") (pinfunction "GND_1") (pintype "passive"))
      (node (ref "R55") (pin "1") (pintype "passive"))
    )
    (net (code "146") (name "Net-(IC3-IN0)") (class "Default")
      (node (ref "IC3") (pin "2") (pinfunction "IN0_2") (pintype "passive"))
      (node (ref "R41") (pin "1") (pintype "passive"))
    )
    (net (code "147") (name "Net-(IC3-IN1)") (class "Default")
      (node (ref "IC3") (pin "6") (pinfunction "IN1_6") (pintype "passive"))
      (node (ref "R44") (pin "1") (pintype "passive"))
    )
    (net (code "148") (name "Net-(IC3-IS)") (class "Default")
      (node (ref "IC3") (pin "4") (pinfunction "IS_4") (pintype "passive"))
      (node (ref "R48") (pin "1") (pintype "passive"))
      (node (ref "R54") (pin "2") (pintype "passive"))
    )
    (net (code "149") (name "Net-(IC4-DEN)") (class "Default")
      (node (ref "IC4") (pin "6") (pinfunction "DEN_6") (pintype "passive"))
      (node (ref "R57") (pin "1") (pintype "passive"))
    )
    (net (code "150") (name "Net-(IC4-DSEL0)") (class "Default")
      (node (ref "IC4") (pin "8") (pinfunction "DSEL0_8") (pintype "passive"))
      (node (ref "R62") (pin "1") (pintype "passive"))
    )
    (net (code "151") (name "Net-(IC4-DSEL1)") (class "Default")
      (node (ref "IC4") (pin "11") (pinfunction "DSEL1_11") (pintype "passive"))
      (node (ref "R63") (pin "1") (pintype "passive"))
    )
    (net (code "152") (name "Net-(IC4-GND)") (class "Default")
      (node (ref "IC4") (pin "4") (pinfunction "GND_4") (pintype "passive"))
      (node (ref "R81") (pin "2") (pintype "passive"))
    )
    (net (code "153") (name "Net-(IC4-IN0)") (class "Default")
      (node (ref "IC4") (pin "2") (pinfunction "IN0_2") (pintype "passive"))
      (node (ref "R65") (pin "1") (pintype "passive"))
    )
    (net (code "154") (name "Net-(IC4-IN1)") (class "Default")
      (node (ref "IC4") (pin "5") (pinfunction "IN1_5") (pintype "passive"))
      (node (ref "R66") (pin "1") (pintype "passive"))
    )
    (net (code "155") (name "Net-(IC4-IN2)") (class "Default")
      (node (ref "IC4") (pin "9") (pinfunction "IN2_9") (pintype "passive"))
      (node (ref "R68") (pin "1") (pintype "passive"))
    )
    (net (code "156") (name "Net-(IC4-IN3)") (class "Default")
      (node (ref "IC4") (pin "10") (pinfunction "IN3_10") (pintype "passive"))
      (node (ref "R72") (pin "1") (pintype "passive"))
    )
    (net (code "157") (name "Net-(IC4-IS)") (class "Default")
      (node (ref "IC4") (pin "7") (pinfunction "IS_7") (pintype "passive"))
      (node (ref "R75") (pin "1") (pintype "passive"))
      (node (ref "R79") (pin "2") (pintype "passive"))
    )
    (net (code "158") (name "Net-(IC5-DEN)") (class "Default")
      (node (ref "IC5") (pin "3") (pinfunction "DEN_3") (pintype "passive"))
      (node (ref "R69") (pin "1") (pintype "passive"))
    )
    (net (code "159") (name "Net-(IC5-DSEL)") (class "Default")
      (node (ref "IC5") (pin "5") (pinfunction "DSEL_5") (pintype "passive"))
      (node (ref "R73") (pin "1") (pintype "passive"))
    )
    (net (code "160") (name "Net-(IC5-GND)") (class "Default")
      (node (ref "IC5") (pin "1") (pinfunction "GND_1") (pintype "passive"))
      (node (ref "R85") (pin "1") (pintype "passive"))
    )
    (net (code "161") (name "Net-(IC5-IN0)") (class "Default")
      (node (ref "IC5") (pin "2") (pinfunction "IN0_2") (pintype "passive"))
      (node (ref "R76") (pin "1") (pintype "passive"))
    )
    (net (code "162") (name "Net-(IC5-IN1)") (class "Default")
      (node (ref "IC5") (pin "6") (pinfunction "IN1_6") (pintype "passive"))
      (node (ref "R78") (pin "1") (pintype "passive"))
    )
    (net (code "163") (name "Net-(IC5-IS)") (class "Default")
      (node (ref "IC5") (pin "4") (pinfunction "IS_4") (pintype "passive"))
      (node (ref "R82") (pin "1") (pintype "passive"))
      (node (ref "R84") (pin "2") (pintype "passive"))
    )
    (net (code "164") (name "Net-(IC6-DEN)") (class "Default")
      (node (ref "IC6") (pin "6") (pinfunction "DEN_6") (pintype "passive"))
      (node (ref "R87") (pin "1") (pintype "passive"))
    )
    (net (code "165") (name "Net-(IC6-DSEL0)") (class "Default")
      (node (ref "IC6") (pin "8") (pinfunction "DSEL0_8") (pintype "passive"))
      (node (ref "R92") (pin "1") (pintype "passive"))
    )
    (net (code "166") (name "Net-(IC6-DSEL1)") (class "Default")
      (node (ref "IC6") (pin "11") (pinfunction "DSEL1_11") (pintype "passive"))
      (node (ref "R93") (pin "1") (pintype "passive"))
    )
    (net (code "167") (name "Net-(IC6-GND)") (class "Default")
      (node (ref "IC6") (pin "4") (pinfunction "GND_4") (pintype "passive"))
      (node (ref "R108") (pin "2") (pintype "passive"))
    )
    (net (code "168") (name "Net-(IC6-IN0)") (class "Default")
      (node (ref "IC6") (pin "2") (pinfunction "IN0_2") (pintype "passive"))
      (node (ref "R95") (pin "1") (pintype "passive"))
    )
    (net (code "169") (name "Net-(IC6-IN1)") (class "Default")
      (node (ref "IC6") (pin "5") (pinfunction "IN1_5") (pintype "passive"))
      (node (ref "R96") (pin "1") (pintype "passive"))
    )
    (net (code "170") (name "Net-(IC6-IN2)") (class "Default")
      (node (ref "IC6") (pin "9") (pinfunction "IN2_9") (pintype "passive"))
      (node (ref "R98") (pin "1") (pintype "passive"))
    )
    (net (code "171") (name "Net-(IC6-IN3)") (class "Default")
      (node (ref "IC6") (pin "10") (pinfunction "IN3_10") (pintype "passive"))
      (node (ref "R99") (pin "1") (pintype "passive"))
    )
    (net (code "172") (name "Net-(IC6-IS)") (class "Default")
      (node (ref "IC6") (pin "7") (pinfunction "IS_7") (pintype "passive"))
      (node (ref "R101") (pin "1") (pintype "passive"))
      (node (ref "R103") (pin "2") (pintype "passive"))
    )
    (net (code "173") (name "Net-(IC7-DEN)") (class "Default")
      (node (ref "IC7") (pin "3") (pinfunction "DEN_3") (pintype "passive"))
      (node (ref "R102") (pin "1") (pintype "passive"))
    )
    (net (code "174") (name "Net-(IC7-DSEL)") (class "Default")
      (node (ref "IC7") (pin "5") (pinfunction "DSEL_5") (pintype "passive"))
      (node (ref "R107") (pin "1") (pintype "passive"))
    )
    (net (code "175") (name "Net-(IC7-GND)") (class "Default")
      (node (ref "IC7") (pin "1") (pinfunction "GND_1") (pintype "passive"))
      (node (ref "R119") (pin "1") (pintype "passive"))
    )
    (net (code "176") (name "Net-(IC7-IN0)") (class "Default")
      (node (ref "IC7") (pin "2") (pinfunction "IN0_2") (pintype "passive"))
      (node (ref "R109") (pin "1") (pintype "passive"))
    )
    (net (code "177") (name "Net-(IC7-IN1)") (class "Default")
      (node (ref "IC7") (pin "6") (pinfunction "IN1_6") (pintype "passive"))
      (node (ref "R111") (pin "1") (pintype "passive"))
    )
    (net (code "178") (name "Net-(IC7-IS)") (class "Default")
      (node (ref "IC7") (pin "4") (pinfunction "IS_4") (pintype "passive"))
      (node (ref "R112") (pin "1") (pintype "passive"))
      (node (ref "R115") (pin "2") (pintype "passive"))
    )
    (net (code "179") (name "Net-(IC8-DEN)") (class "Default")
      (node (ref "IC8") (pin "6") (pinfunction "DEN_6") (pintype "passive"))
      (node (ref "R120") (pin "1") (pintype "passive"))
    )
    (net (code "180") (name "Net-(IC8-DSEL0)") (class "Default")
      (node (ref "IC8") (pin "8") (pinfunction "DSEL0_8") (pintype "passive"))
      (node (ref "R127") (pin "1") (pintype "passive"))
    )
    (net (code "181") (name "Net-(IC8-DSEL1)") (class "Default")
      (node (ref "IC8") (pin "11") (pinfunction "DSEL1_11") (pintype "passive"))
      (node (ref "R128") (pin "1") (pintype "passive"))
    )
    (net (code "182") (name "Net-(IC8-GND)") (class "Default")
      (node (ref "IC8") (pin "4") (pinfunction "GND_4") (pintype "passive"))
      (node (ref "R141") (pin "2") (pintype "passive"))
    )
    (net (code "183") (name "Net-(IC8-IN0)") (class "Default")
      (node (ref "IC8") (pin "2") (pinfunction "IN0_2") (pintype "passive"))
      (node (ref "R131") (pin "1") (pintype "passive"))
    )
    (net (code "184") (name "Net-(IC8-IN1)") (class "Default")
      (node (ref "IC8") (pin "5") (pinfunction "IN1_5") (pintype "passive"))
      (node (ref "R132") (pin "1") (pintype "passive"))
    )
    (net (code "185") (name "Net-(IC8-IN2)") (class "Default")
      (node (ref "IC8") (pin "9") (pinfunction "IN2_9") (pintype "passive"))
      (node (ref "R134") (pin "1") (pintype "passive"))
    )
    (net (code "186") (name "Net-(IC8-IN3)") (class "Default")
      (node (ref "IC8") (pin "10") (pinfunction "IN3_10") (pintype "passive"))
      (node (ref "R135") (pin "1") (pintype "passive"))
    )
    (net (code "187") (name "Net-(IC8-IS)") (class "Default")
      (node (ref "IC8") (pin "7") (pinfunction "IS_7") (pintype "passive"))
      (node (ref "R137") (pin "1") (pintype "passive"))
      (node (ref "R139") (pin "2") (pintype "passive"))
    )
    (net (code "188") (name "Net-(IC9-BOOT)") (class "Default")
      (node (ref "C44") (pin "1") (pintype "passive"))
      (node (ref "IC9") (pin "1") (pinfunction "BOOT_1") (pintype "passive"))
    )
    (net (code "189") (name "Net-(IC9-VSENSE)") (class "Default")
      (node (ref "IC9") (pin "4") (pinfunction "VSENSE_4") (pintype "passive"))
      (node (ref "R144") (pin "1") (pintype "passive"))
      (node (ref "R152") (pin "2") (pintype "passive"))
    )
    (net (code "190") (name "Net-(IC10-DEN)") (class "Default")
      (node (ref "IC10") (pin "3") (pinfunction "DEN_3") (pintype "passive"))
      (node (ref "R143") (pin "1") (pintype "passive"))
    )
    (net (code "191") (name "Net-(IC10-DSEL)") (class "Default")
      (node (ref "IC10") (pin "5") (pinfunction "DSEL_5") (pintype "passive"))
      (node (ref "R148") (pin "1") (pintype "passive"))
    )
    (net (code "192") (name "Net-(IC10-GND)") (class "Default")
      (node (ref "IC10") (pin "1") (pinfunction "GND_1") (pintype "passive"))
      (node (ref "R162") (pin "1") (pintype "passive"))
    )
    (net (code "193") (name "Net-(IC10-IN0)") (class "Default")
      (node (ref "IC10") (pin "2") (pinfunction "IN0_2") (pintype "passive"))
      (node (ref "R149") (pin "1") (pintype "passive"))
    )
    (net (code "194") (name "Net-(IC10-IN1)") (class "Default")
      (node (ref "IC10") (pin "6") (pinfunction "IN1_6") (pintype "passive"))
      (node (ref "R151") (pin "1") (pintype "passive"))
    )
    (net (code "195") (name "Net-(IC10-IS)") (class "Default")
      (node (ref "IC10") (pin "4") (pinfunction "IS_4") (pintype "passive"))
      (node (ref "R153") (pin "1") (pintype "passive"))
      (node (ref "R155") (pin "2") (pintype "passive"))
    )
    (net (code "196") (name "Net-(IC11-DEN)") (class "Default")
      (node (ref "IC11") (pin "6") (pinfunction "DEN_6") (pintype "passive"))
      (node (ref "R156") (pin "1") (pintype "passive"))
    )
    (net (code "197") (name "Net-(IC11-DSEL0)") (class "Default")
      (node (ref "IC11") (pin "8") (pinfunction "DSEL0_8") (pintype "passive"))
      (node (ref "R161") (pin "1") (pintype "passive"))
    )
    (net (code "198") (name "Net-(IC11-DSEL1)") (class "Default")
      (node (ref "IC11") (pin "11") (pinfunction "DSEL1_11") (pintype "passive"))
      (node (ref "R163") (pin "1") (pintype "passive"))
    )
    (net (code "199") (name "Net-(IC11-GND)") (class "Default")
      (node (ref "IC11") (pin "4") (pinfunction "GND_4") (pintype "passive"))
      (node (ref "R178") (pin "2") (pintype "passive"))
    )
    (net (code "200") (name "Net-(IC11-IN0)") (class "Default")
      (node (ref "IC11") (pin "2") (pinfunction "IN0_2") (pintype "passive"))
      (node (ref "R166") (pin "1") (pintype "passive"))
    )
    (net (code "201") (name "Net-(IC11-IN1)") (class "Default")
      (node (ref "IC11") (pin "5") (pinfunction "IN1_5") (pintype "passive"))
      (node (ref "R168") (pin "1") (pintype "passive"))
    )
    (net (code "202") (name "Net-(IC11-IN2)") (class "Default")
      (node (ref "IC11") (pin "9") (pinfunction "IN2_9") (pintype "passive"))
      (node (ref "R171") (pin "1") (pintype "passive"))
    )
    (net (code "203") (name "Net-(IC11-IN3)") (class "Default")
      (node (ref "IC11") (pin "10") (pinfunction "IN3_10") (pintype "passive"))
      (node (ref "R172") (pin "1") (pintype "passive"))
    )
    (net (code "204") (name "Net-(IC11-IS)") (class "Default")
      (node (ref "IC11") (pin "7") (pinfunction "IS_7") (pintype "passive"))
      (node (ref "R174") (pin "1") (pintype "passive"))
      (node (ref "R176") (pin "2") (pintype "passive"))
    )
    (net (code "205") (name "Net-(IC12-BOOT)") (class "Default")
      (node (ref "C55") (pin "1") (pintype "passive"))
      (node (ref "IC12") (pin "1") (pinfunction "BOOT_1") (pintype "passive"))
    )
    (net (code "206") (name "Net-(IC12-VSENSE)") (class "Default")
      (node (ref "IC12") (pin "4") (pinfunction "VSENSE_4") (pintype "passive"))
      (node (ref "R169") (pin "1") (pintype "passive"))
      (node (ref "R175") (pin "2") (pintype "passive"))
    )
    (net (code "207") (name "Net-(K1-COM_1)") (class "Default")
      (node (ref "FU3") (pin "1") (pintype "passive"))
      (node (ref "K1") (pin "3") (pinfunction "COM_1_3") (pintype "passive"))
      (node (ref "K1") (pin "4") (pinfunction "COM_2_4") (pintype "passive"))
    )
    (net (code "208") (name "Net-(LED3-Pad2)") (class "Default")
      (node (ref "LED3") (pin "2") (pintype "passive"))
      (node (ref "R138") (pin "1") (pintype "passive"))
    )
    (net (code "209") (name "Net-(OP1-6)") (class "Default")
      (node (ref "OP1") (pin "1") (pinfunction "6_1") (pintype "passive"))
      (node (ref "R7") (pin "1") (pintype "passive"))
    )
    (net (code "210") (name "Net-(OP1-8)") (class "Default")
      (node (ref "LED1") (pin "2") (pintype "passive"))
      (node (ref "OP1") (pin "3") (pinfunction "8_3") (pintype "passive"))
      (node (ref "R16") (pin "2") (pintype "passive"))
    )
    (net (code "211") (name "Net-(OP1-9)") (class "Default")
      (node (ref "OP1") (pin "4") (pinfunction "9_4") (pintype "passive"))
      (node (ref "R2") (pin "2") (pintype "passive"))
    )
    (net (code "212") (name "Net-(OP2-6)") (class "Default")
      (node (ref "OP2") (pin "1") (pinfunction "6_1") (pintype "passive"))
      (node (ref "R10") (pin "1") (pintype "passive"))
    )
    (net (code "213") (name "Net-(OP2-9)") (class "Default")
      (node (ref "OP2") (pin "4") (pinfunction "9_4") (pintype "passive"))
      (node (ref "R5") (pin "2") (pintype "passive"))
    )
    (net (code "214") (name "Net-(R12-Pad1)") (class "Default")
      (node (ref "R12") (pin "1") (pintype "passive"))
      (node (ref "R3") (pin "1") (pintype "passive"))
    )
    (net (code "215") (name "Net-(R13-Pad1)") (class "Default")
      (node (ref "R13") (pin "1") (pintype "passive"))
      (node (ref "R4") (pin "1") (pintype "passive"))
    )
    (net (code "216") (name "Net-(RST1-COMMON)") (class "Default")
      (node (ref "R50") (pin "2") (pintype "passive"))
      (node (ref "RST1") (pin "1") (pinfunction "COMMON_1") (pintype "passive"))
    )
    (net (code "217") (name "Net-(RST2-COMMON)") (class "Default")
      (node (ref "R117") (pin "2") (pintype "passive"))
      (node (ref "RST2") (pin "1") (pinfunction "COMMON_1") (pintype "passive"))
    )
    (net (code "218") (name "Net-(RST3-COMMON)") (class "Default")
      (node (ref "R130") (pin "2") (pintype "passive"))
      (node (ref "RST3") (pin "1") (pinfunction "COMMON_1") (pintype "passive"))
    )
    (net (code "219") (name "Net-(U2-+Vo)") (class "Default")
      (node (ref "C37") (pin "2") (pintype "passive"))
      (node (ref "R121") (pin "1") (pintype "passive"))
      (node (ref "U2") (pin "3") (pinfunction "+Vo_3") (pintype "passive"))
    )
    (net (code "220") (name "Net-(U3-+Vo)") (class "Default")
      (node (ref "C38") (pin "2") (pintype "passive"))
      (node (ref "R122") (pin "1") (pintype "passive"))
      (node (ref "U3") (pin "3") (pinfunction "+Vo_3") (pintype "passive"))
    )
    (net (code "221") (name "Net-(U4-+Vo)") (class "Default")
      (node (ref "C50") (pin "2") (pintype "passive"))
      (node (ref "R147") (pin "1") (pintype "passive"))
      (node (ref "U4") (pin "3") (pinfunction "+Vo_3") (pintype "passive"))
    )
    (net (code "222") (name "Net-(U7-+Vo)") (class "Default")
      (node (ref "C60") (pin "2") (pintype "passive"))
      (node (ref "R167") (pin "1") (pintype "passive"))
      (node (ref "U7") (pin "3") (pinfunction "+Vo_3") (pintype "passive"))
    )
    (net (code "223") (name "VBAT") (class "Default")
      (node (ref "CN4") (pin "19") (pinfunction "19_19") (pintype "passive"))
      (node (ref "CN4") (pin "20") (pinfunction "20_20") (pintype "passive"))
      (node (ref "D4") (pin "1") (pinfunction "1_1") (pintype "passive"))
      (node (ref "FU2") (pin "2") (pintype "passive"))
      (node (ref "K1") (pin "1") (pinfunction "NO_1_1") (pintype "passive"))
      (node (ref "K1") (pin "2") (pinfunction "NO_2_2") (pintype "passive"))
      (node (ref "R7") (pin "2") (pintype "passive"))
      (node (ref "U1") (pin "1") (pinfunction "Cathode_1") (pintype "passive"))
      (node (ref "VBAT1") (pin "1") (pinfunction "1_1") (pintype "passive"))
      (node (ref "VBAT1") (pin "2") (pinfunction "2_2") (pintype "passive"))
      (node (ref "VBAT1") (pin "3") (pinfunction "3_3") (pintype "passive"))
      (node (ref "VBAT1") (pin "4") (pinfunction "4_4") (pintype "passive"))
    )
    (net (code "224") (name "unconnected-(CN3-Pad21)") (class "Default")
      (node (ref "CN3") (pin "21") (pinfunction "21_21") (pintype "passive"))
    )
    (net (code "225") (name "unconnected-(CN4-Pad18)") (class "Default")
      (node (ref "CN4") (pin "18") (pinfunction "18_18") (pintype "passive"))
    )
    (net (code "226") (name "unconnected-(D1-A-Pad1)") (class "Default")
      (node (ref "D1") (pin "1") (pinfunction "A_1") (pintype "passive"))
    )
    (net (code "227") (name "unconnected-(D1-K-Pad3)") (class "Default")
      (node (ref "D1") (pin "3") (pinfunction "K_3") (pintype "passive"))
    )
    (net (code "228") (name "unconnected-(D1-N.C.-Pad2)") (class "Default")
      (node (ref "D1") (pin "2") (pinfunction "N.C._2") (pintype "passive"))
    )
    (net (code "229") (name "unconnected-(D2-A-Pad1)") (class "Default")
      (node (ref "D2") (pin "1") (pinfunction "A_1") (pintype "passive"))
    )
    (net (code "230") (name "unconnected-(D2-K-Pad3)") (class "Default")
      (node (ref "D2") (pin "3") (pinfunction "K_3") (pintype "passive"))
    )
    (net (code "231") (name "unconnected-(D2-N.C.-Pad2)") (class "Default")
      (node (ref "D2") (pin "2") (pinfunction "N.C._2") (pintype "passive"))
    )
    (net (code "232") (name "unconnected-(D3-A-Pad1)") (class "Default")
      (node (ref "D3") (pin "1") (pinfunction "A_1") (pintype "passive"))
    )
    (net (code "233") (name "unconnected-(D3-K-Pad3)") (class "Default")
      (node (ref "D3") (pin "3") (pinfunction "K_3") (pintype "passive"))
    )
    (net (code "234") (name "unconnected-(D3-N.C.-Pad2)") (class "Default")
      (node (ref "D3") (pin "2") (pinfunction "N.C._2") (pintype "passive"))
    )
    (net (code "235") (name "unconnected-(D5-A-Pad1)") (class "Default")
      (node (ref "D5") (pin "1") (pinfunction "A_1") (pintype "passive"))
    )
    (net (code "236") (name "unconnected-(D5-K-Pad3)") (class "Default")
      (node (ref "D5") (pin "3") (pinfunction "K_3") (pintype "passive"))
    )
    (net (code "237") (name "unconnected-(D5-N.C.-Pad2)") (class "Default")
      (node (ref "D5") (pin "2") (pinfunction "N.C._2") (pintype "passive"))
    )
    (net (code "238") (name "unconnected-(D6-A-Pad1)") (class "Default")
      (node (ref "D6") (pin "1") (pinfunction "A_1") (pintype "passive"))
    )
    (net (code "239") (name "unconnected-(D6-K-Pad3)") (class "Default")
      (node (ref "D6") (pin "3") (pinfunction "K_3") (pintype "passive"))
    )
    (net (code "240") (name "unconnected-(D6-N.C.-Pad2)") (class "Default")
      (node (ref "D6") (pin "2") (pinfunction "N.C._2") (pintype "passive"))
    )
    (net (code "241") (name "unconnected-(D7-A-Pad1)") (class "Default")
      (node (ref "D7") (pin "1") (pinfunction "A_1") (pintype "passive"))
    )
    (net (code "242") (name "unconnected-(D7-K-Pad3)") (class "Default")
      (node (ref "D7") (pin "3") (pinfunction "K_3") (pintype "passive"))
    )
    (net (code "243") (name "unconnected-(D7-N.C.-Pad2)") (class "Default")
      (node (ref "D7") (pin "2") (pinfunction "N.C._2") (pintype "passive"))
    )
    (net (code "244") (name "unconnected-(D8-A-Pad1)") (class "Default")
      (node (ref "D8") (pin "1") (pinfunction "A_1") (pintype "passive"))
    )
    (net (code "245") (name "unconnected-(D8-K-Pad3)") (class "Default")
      (node (ref "D8") (pin "3") (pinfunction "K_3") (pintype "passive"))
    )
    (net (code "246") (name "unconnected-(D8-N.C.-Pad2)") (class "Default")
      (node (ref "D8") (pin "2") (pinfunction "N.C._2") (pintype "passive"))
    )
    (net (code "247") (name "unconnected-(D10-A-Pad1)") (class "Default")
      (node (ref "D10") (pin "1") (pinfunction "A_1") (pintype "passive"))
    )
    (net (code "248") (name "unconnected-(D10-K-Pad3)") (class "Default")
      (node (ref "D10") (pin "3") (pinfunction "K_3") (pintype "passive"))
    )
    (net (code "249") (name "unconnected-(D10-N.C.-Pad2)") (class "Default")
      (node (ref "D10") (pin "2") (pinfunction "N.C._2") (pintype "passive"))
    )
    (net (code "250") (name "unconnected-(D13-A-Pad1)") (class "Default")
      (node (ref "D13") (pin "1") (pinfunction "A_1") (pintype "passive"))
    )
    (net (code "251") (name "unconnected-(D13-K-Pad3)") (class "Default")
      (node (ref "D13") (pin "3") (pinfunction "K_3") (pintype "passive"))
    )
    (net (code "252") (name "unconnected-(D13-N.C.-Pad2)") (class "Default")
      (node (ref "D13") (pin "2") (pinfunction "N.C._2") (pintype "passive"))
    )
    (net (code "253") (name "unconnected-(D14-A-Pad1)") (class "Default")
      (node (ref "D14") (pin "1") (pinfunction "A_1") (pintype "passive"))
    )
    (net (code "254") (name "unconnected-(D14-K-Pad3)") (class "Default")
      (node (ref "D14") (pin "3") (pinfunction "K_3") (pintype "passive"))
    )
    (net (code "255") (name "unconnected-(D14-N.C.-Pad2)") (class "Default")
      (node (ref "D14") (pin "2") (pinfunction "N.C._2") (pintype "passive"))
    )
    (net (code "256") (name "unconnected-(HIGH1-Pad2)") (class "Default")
      (node (ref "HIGH1") (pin "2") (pinfunction "2_2") (pintype "passive"))
    )
    (net (code "257") (name "unconnected-(HIGH1-Pad10)") (class "Default")
      (node (ref "HIGH1") (pin "10") (pinfunction "10_10") (pintype "passive"))
    )
    (net (code "258") (name "unconnected-(HIGH1-Pad11)") (class "Default")
      (node (ref "HIGH1") (pin "11") (pinfunction "11_11") (pintype "passive"))
    )
    (net (code "259") (name "unconnected-(HIGH1-Pad12)") (class "Default")
      (node (ref "HIGH1") (pin "12") (pinfunction "12_12") (pintype "passive"))
    )
    (net (code "260") (name "unconnected-(IC9-ENA-Pad5)") (class "Default")
      (node (ref "IC9") (pin "5") (pinfunction "ENA_5") (pintype "passive"))
    )
    (net (code "261") (name "unconnected-(IC9-NC_1-Pad2)") (class "Default")
      (node (ref "IC9") (pin "2") (pinfunction "NC_1_2") (pintype "passive"))
    )
    (net (code "262") (name "unconnected-(IC9-NC_2-Pad3)") (class "Default")
      (node (ref "IC9") (pin "3") (pinfunction "NC_2_3") (pintype "passive"))
    )
    (net (code "263") (name "unconnected-(IC12-ENA-Pad5)") (class "Default")
      (node (ref "IC12") (pin "5") (pinfunction "ENA_5") (pintype "passive"))
    )
    (net (code "264") (name "unconnected-(IC12-NC_1-Pad2)") (class "Default")
      (node (ref "IC12") (pin "2") (pinfunction "NC_1_2") (pintype "passive"))
    )
    (net (code "265") (name "unconnected-(IC12-NC_2-Pad3)") (class "Default")
      (node (ref "IC12") (pin "3") (pinfunction "NC_2_3") (pintype "passive"))
    )
    (net (code "266") (name "unconnected-(IC13-3V8-Pad13)") (class "Default")
      (node (ref "IC13") (pin "13") (pinfunction "3V8_13") (pintype "passive"))
    )
    (net (code "267") (name "unconnected-(IC13-BAT-Pad17)") (class "Default")
      (node (ref "IC13") (pin "17") (pinfunction "BAT_17") (pintype "passive"))
    )
    (net (code "268") (name "unconnected-(IC13-CHR-Pad10)") (class "Default")
      (node (ref "IC13") (pin "10") (pinfunction "CHR_10") (pintype "passive"))
    )
    (net (code "269") (name "unconnected-(IC13-DTR-Pad2)") (class "Default")
      (node (ref "IC13") (pin "2") (pinfunction "DTR_2") (pintype "passive"))
    )
    (net (code "270") (name "unconnected-(IC13-D_R-Pad8)") (class "Default")
      (node (ref "IC13") (pin "8") (pinfunction "D_R_8") (pintype "passive"))
    )
    (net (code "271") (name "unconnected-(IC13-D_T-Pad7)") (class "Default")
      (node (ref "IC13") (pin "7") (pinfunction "D_T_7") (pintype "passive"))
    )
    (net (code "272") (name "unconnected-(IC13-EN-Pad14)") (class "Default")
      (node (ref "IC13") (pin "14") (pinfunction "EN_14") (pintype "passive"))
    )
    (net (code "273") (name "unconnected-(IC13-IO19-Pad20)") (class "Default")
      (node (ref "IC13") (pin "20") (pinfunction "IO19_20") (pintype "passive"))
    )
    (net (code "274") (name "unconnected-(IC13-RI-Pad1)") (class "Default")
      (node (ref "IC13") (pin "1") (pinfunction "RI_1") (pintype "passive"))
    )
    (net (code "275") (name "unconnected-(IC13-R{slash}PK-Pad19)") (class "Default")
      (node (ref "IC13") (pin "19") (pinfunction "R/PK_19") (pintype "passive"))
    )
    (net (code "276") (name "unconnected-(IC13-SCL-Pad12)") (class "Default")
      (node (ref "IC13") (pin "12") (pinfunction "SCL_12") (pintype "passive"))
    )
    (net (code "277") (name "unconnected-(IC13-SDA-Pad11)") (class "Default")
      (node (ref "IC13") (pin "11") (pinfunction "SDA_11") (pintype "passive"))
    )
    (net (code "278") (name "unconnected-(IC13-U1R-Pad3)") (class "Default")
      (node (ref "IC13") (pin "3") (pinfunction "U1R_3") (pintype "passive"))
    )
    (net (code "279") (name "unconnected-(IC13-U1T-Pad4)") (class "Default")
      (node (ref "IC13") (pin "4") (pinfunction "U1T_4") (pintype "passive"))
    )
    (net (code "280") (name "unconnected-(J2-Pad3)") (class "Default")
      (node (ref "J2") (pin "3") (pinfunction "3_3") (pintype "passive+no_connect"))
    )
    (net (code "281") (name "unconnected-(J2-Pad4)") (class "Default")
      (node (ref "J2") (pin "4") (pinfunction "4_4") (pintype "passive+no_connect"))
    )
    (net (code "282") (name "unconnected-(LOW1-Pad2)") (class "Default")
      (node (ref "LOW1") (pin "2") (pinfunction "2_2") (pintype "passive"))
    )
    (net (code "283") (name "unconnected-(LOW1-Pad3)") (class "Default")
      (node (ref "LOW1") (pin "3") (pinfunction "3_3") (pintype "passive"))
    )
    (net (code "284") (name "unconnected-(LOW1-Pad13)") (class "Default")
      (node (ref "LOW1") (pin "13") (pinfunction "13_13") (pintype "passive"))
    )
    (net (code "285") (name "unconnected-(LOW1-Pad21)") (class "Default")
      (node (ref "LOW1") (pin "21") (pinfunction "21_21") (pintype "passive"))
    )
    (net (code "286") (name "unconnected-(LOW1-Pad22)") (class "Default")
      (node (ref "LOW1") (pin "22") (pinfunction "22_22") (pintype "passive"))
    )
    (net (code "287") (name "unconnected-(LOW2-Pad4)") (class "Default")
      (node (ref "LOW2") (pin "4") (pinfunction "4_4") (pintype "passive"))
    )
    (net (code "288") (name "unconnected-(LOW2-Pad19)") (class "Default")
      (node (ref "LOW2") (pin "19") (pinfunction "19_19") (pintype "passive"))
    )
    (net (code "289") (name "unconnected-(LOW2-Pad20)") (class "Default")
      (node (ref "LOW2") (pin "20") (pinfunction "20_20") (pintype "passive"))
    )
    (net (code "290") (name "unconnected-(R24-Pad2)") (class "Default")
      (node (ref "R24") (pin "2") (pintype "passive"))
    )
    (net (code "291") (name "unconnected-(R53-Pad1)") (class "Default")
      (node (ref "R53") (pin "1") (pintype "passive"))
    )
    (net (code "292") (name "unconnected-(R55-Pad2)") (class "Default")
      (node (ref "R55") (pin "2") (pintype "passive"))
    )
    (net (code "293") (name "unconnected-(R81-Pad1)") (class "Default")
      (node (ref "R81") (pin "1") (pintype "passive"))
    )
    (net (code "294") (name "unconnected-(R85-Pad2)") (class "Default")
      (node (ref "R85") (pin "2") (pintype "passive"))
    )
    (net (code "295") (name "unconnected-(R108-Pad1)") (class "Default")
      (node (ref "R108") (pin "1") (pintype "passive"))
    )
    (net (code "296") (name "unconnected-(R119-Pad2)") (class "Default")
      (node (ref "R119") (pin "2") (pintype "passive"))
    )
    (net (code "297") (name "unconnected-(R141-Pad1)") (class "Default")
      (node (ref "R141") (pin "1") (pintype "passive"))
    )
    (net (code "298") (name "unconnected-(R162-Pad2)") (class "Default")
      (node (ref "R162") (pin "2") (pintype "passive"))
    )
    (net (code "299") (name "unconnected-(R178-Pad1)") (class "Default")
      (node (ref "R178") (pin "1") (pintype "passive"))
    )
    (net (code "300") (name "unconnected-(U2-Trim-Pad4)") (class "Default")
      (node (ref "U2") (pin "4") (pinfunction "Trim_4") (pintype "passive"))
    )
    (net (code "301") (name "unconnected-(U3-Trim-Pad4)") (class "Default")
      (node (ref "U3") (pin "4") (pinfunction "Trim_4") (pintype "passive"))
    )
    (net (code "302") (name "unconnected-(U4-Trim-Pad4)") (class "Default")
      (node (ref "U4") (pin "4") (pinfunction "Trim_4") (pintype "passive"))
    )
    (net (code "303") (name "unconnected-(U7-Trim-Pad4)") (class "Default")
      (node (ref "U7") (pin "4") (pinfunction "Trim_4") (pintype "passive"))
    )
  )
)
